# tc08ttl.net
KiCad netlist of a schematic drawn in EAGLE
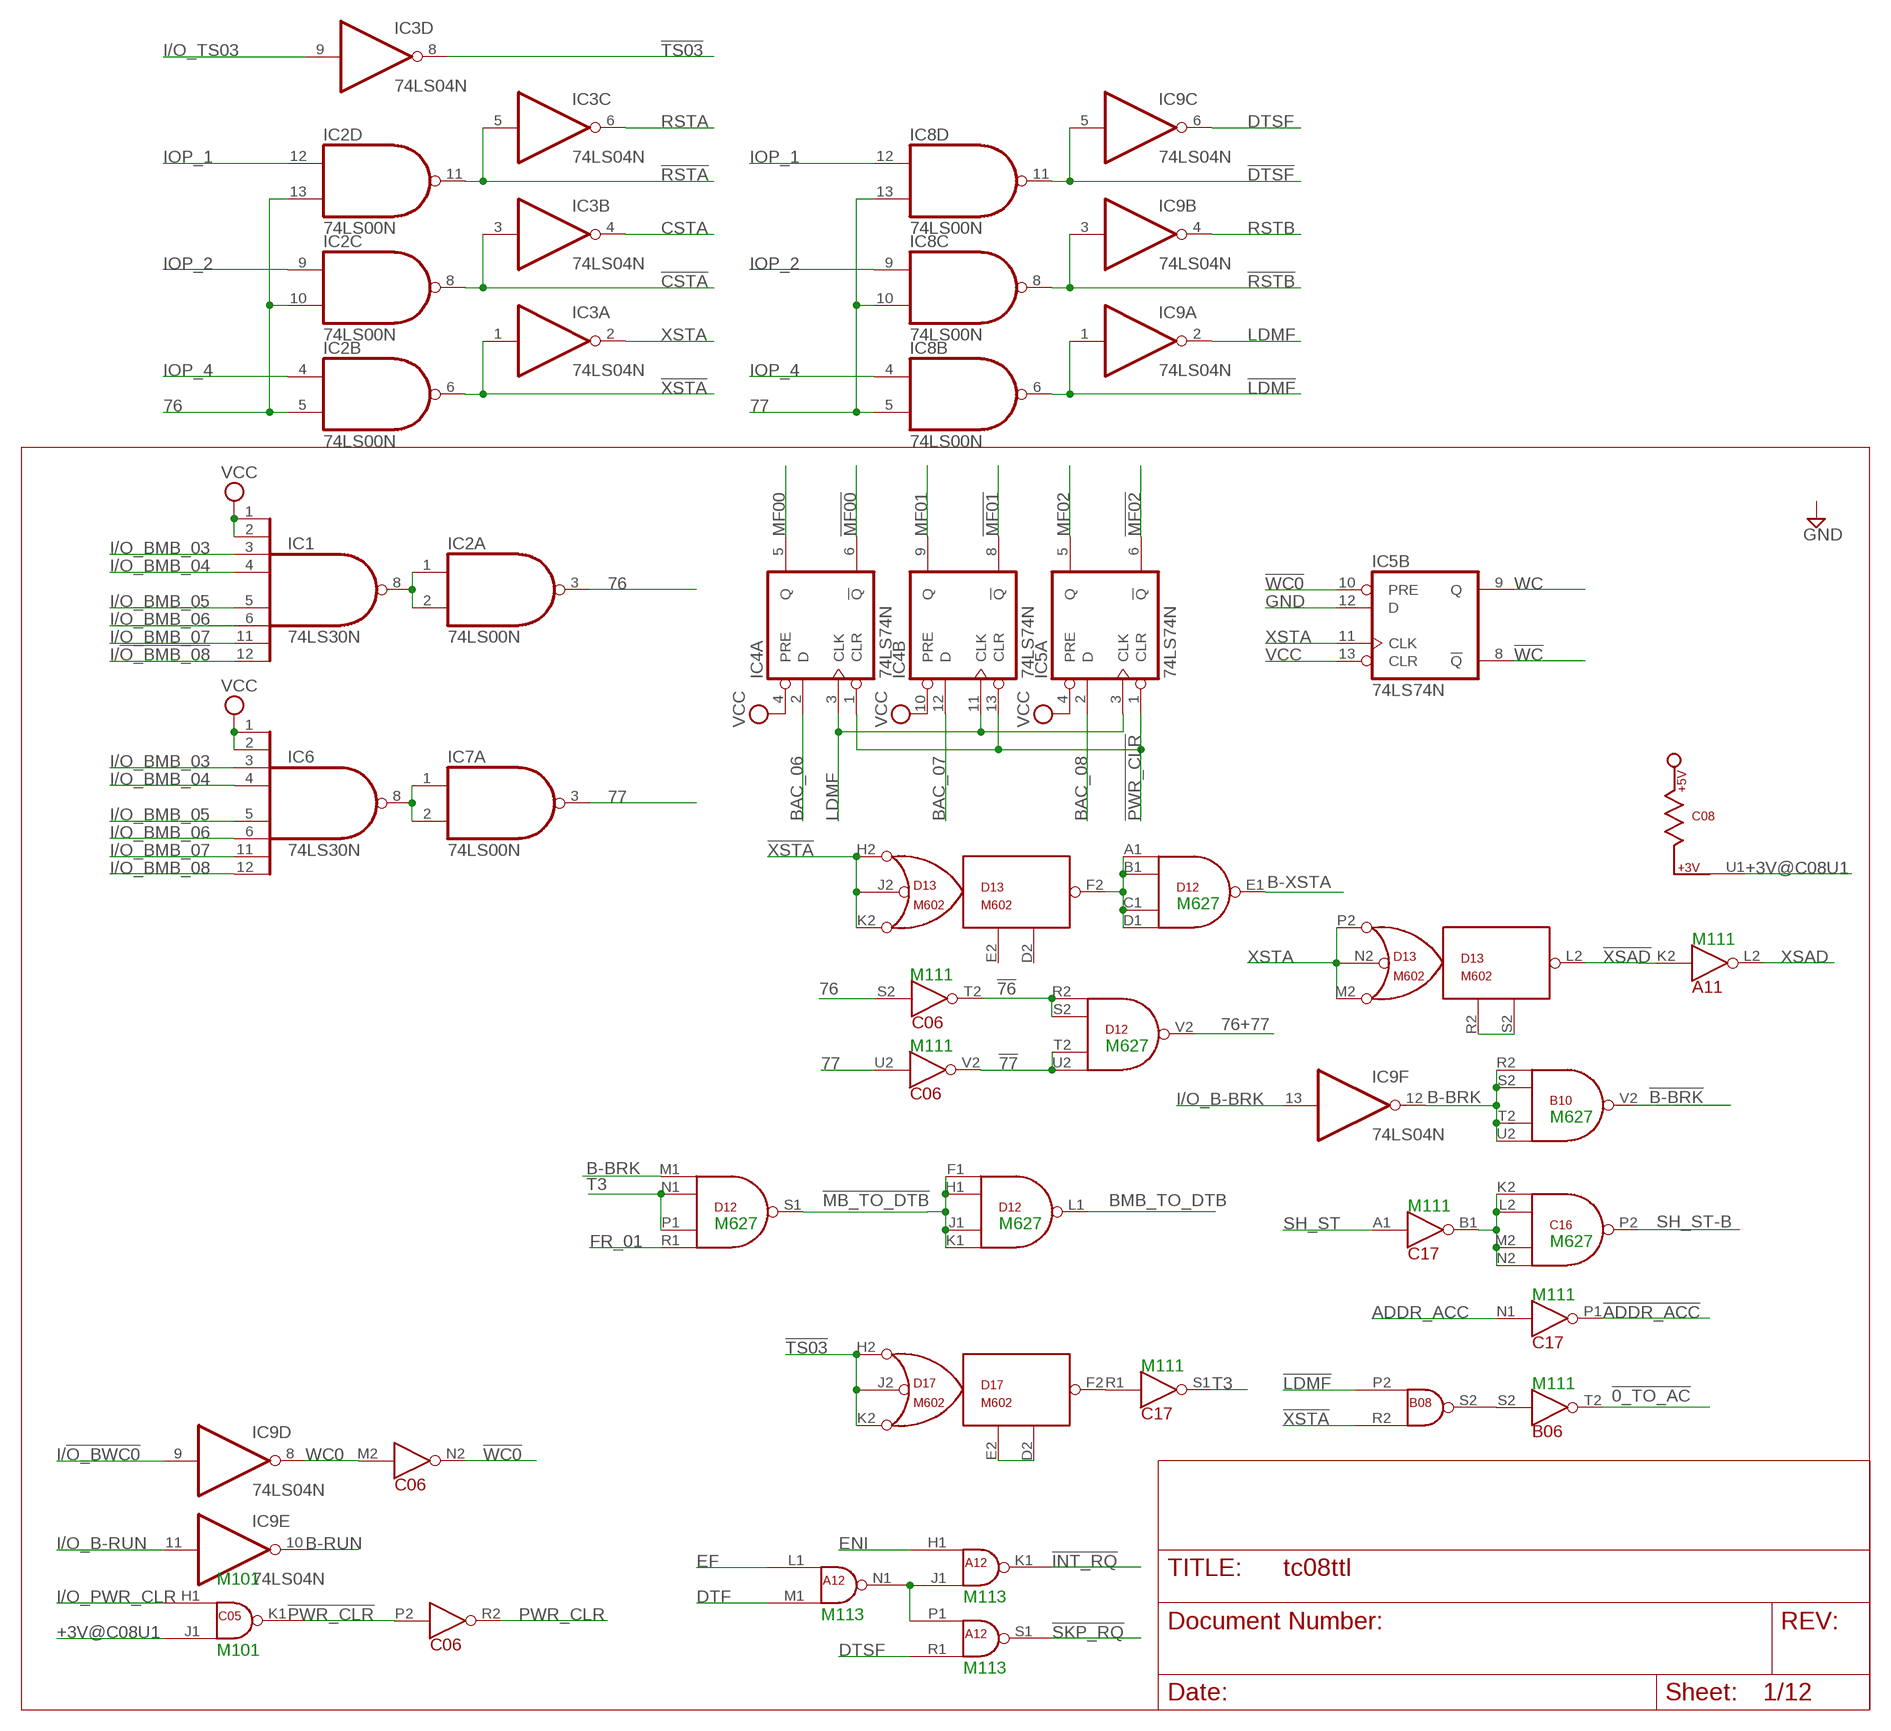
[diagram p0: schematic, sheet 1]
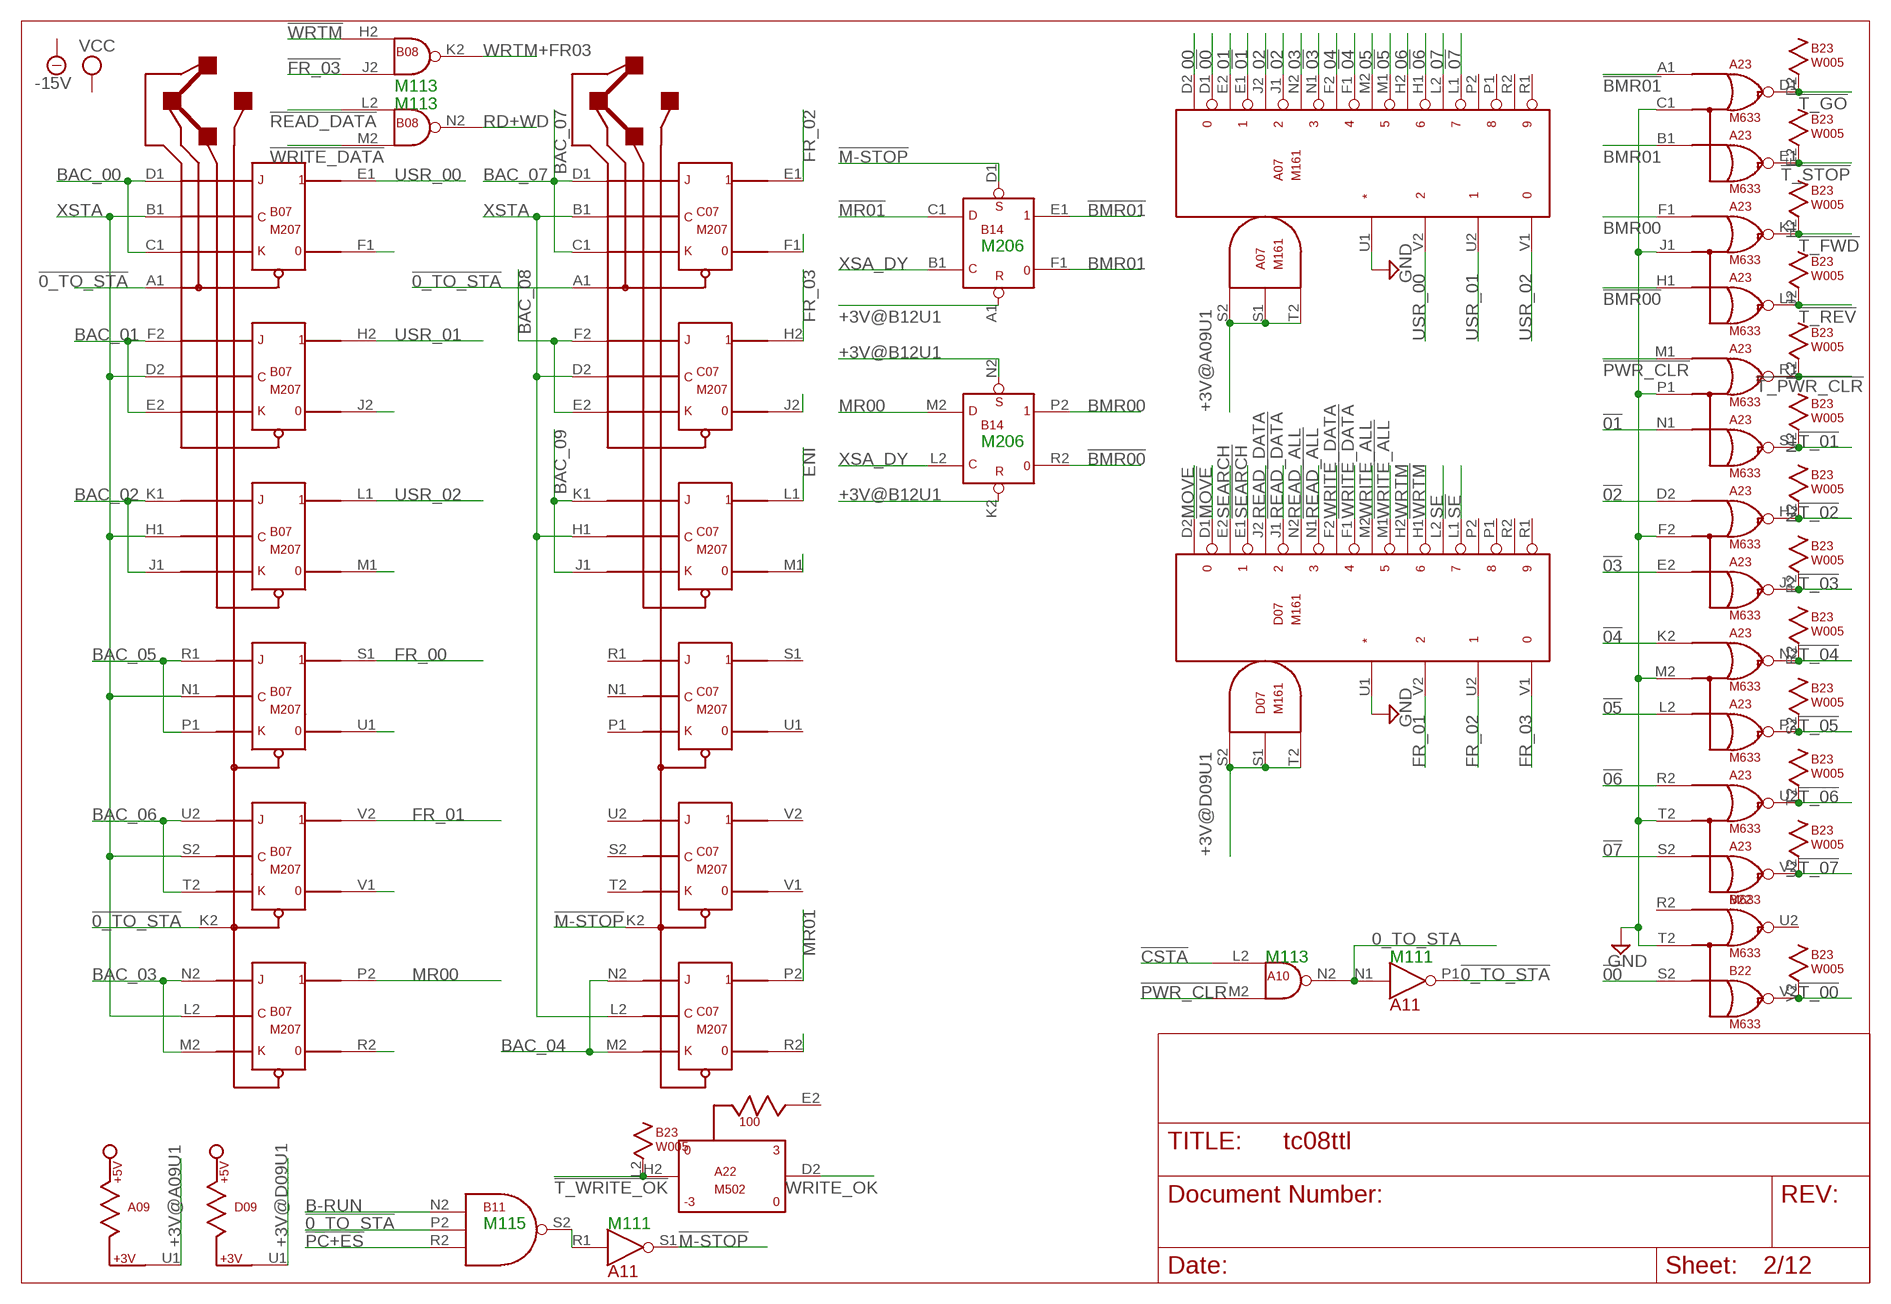
[diagram p1: schematic, sheet 2]
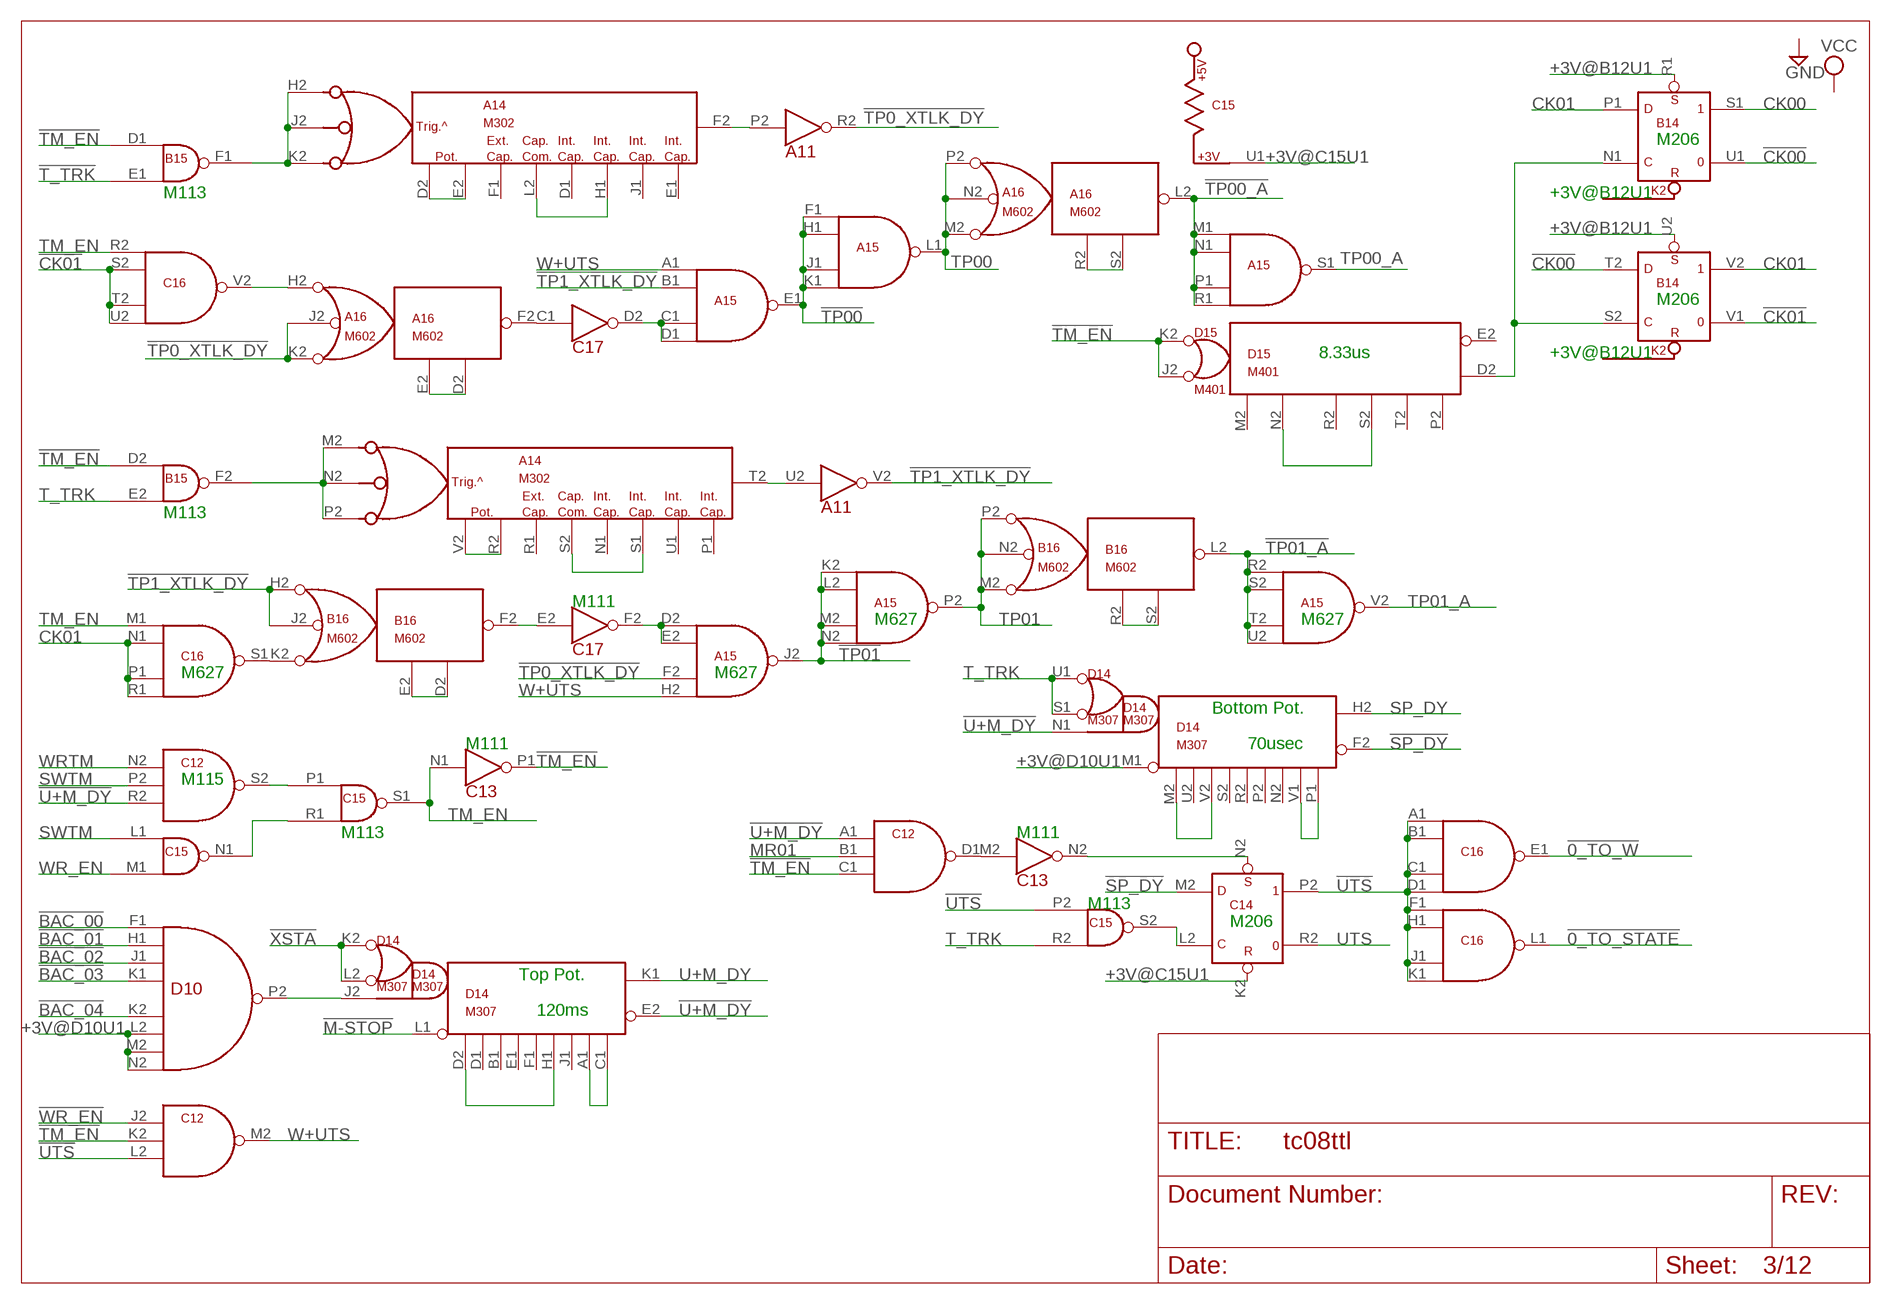
[diagram p2: schematic, sheet 3]
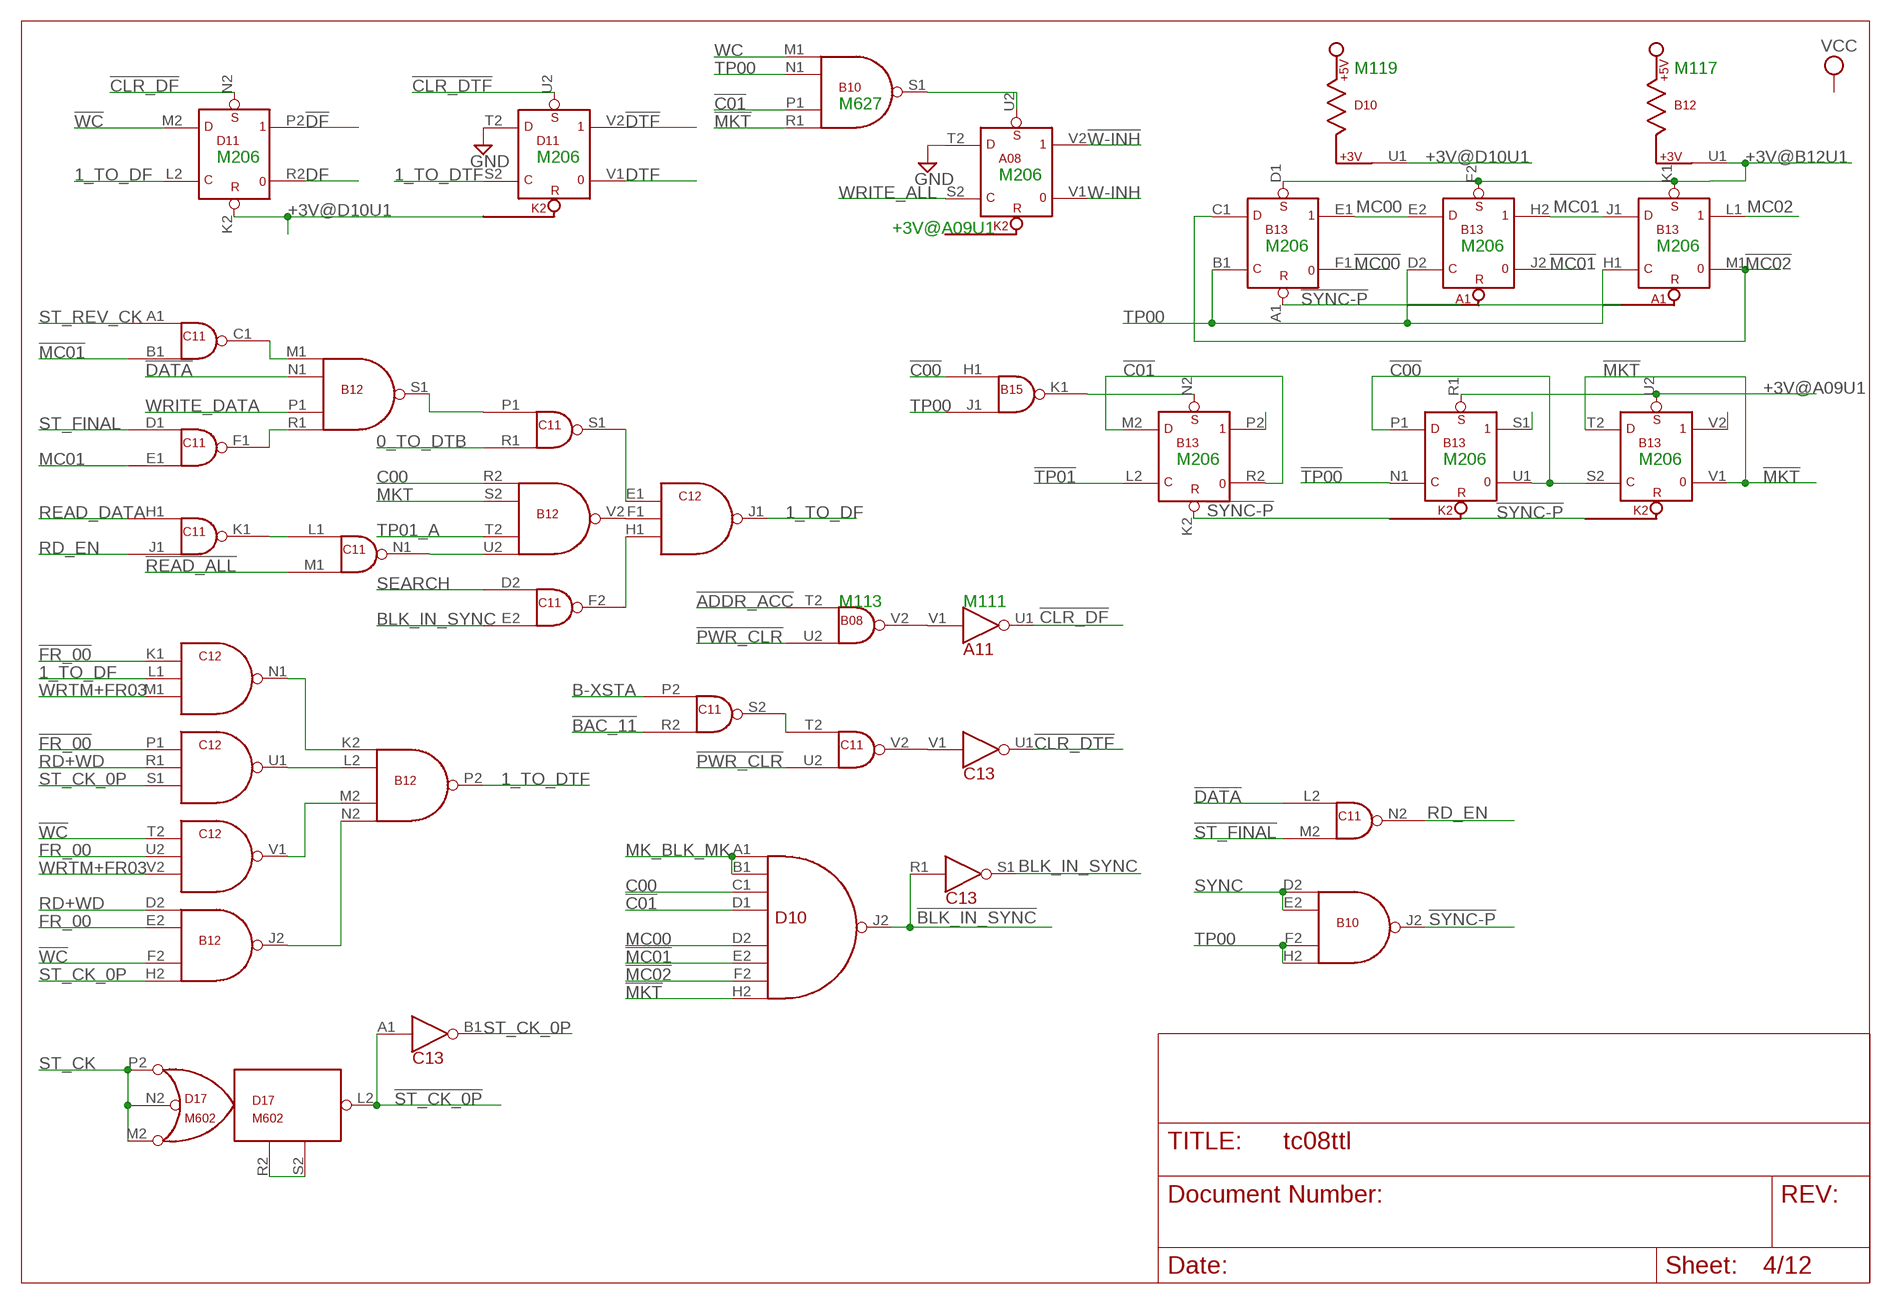
[diagram p3: schematic, sheet 4]
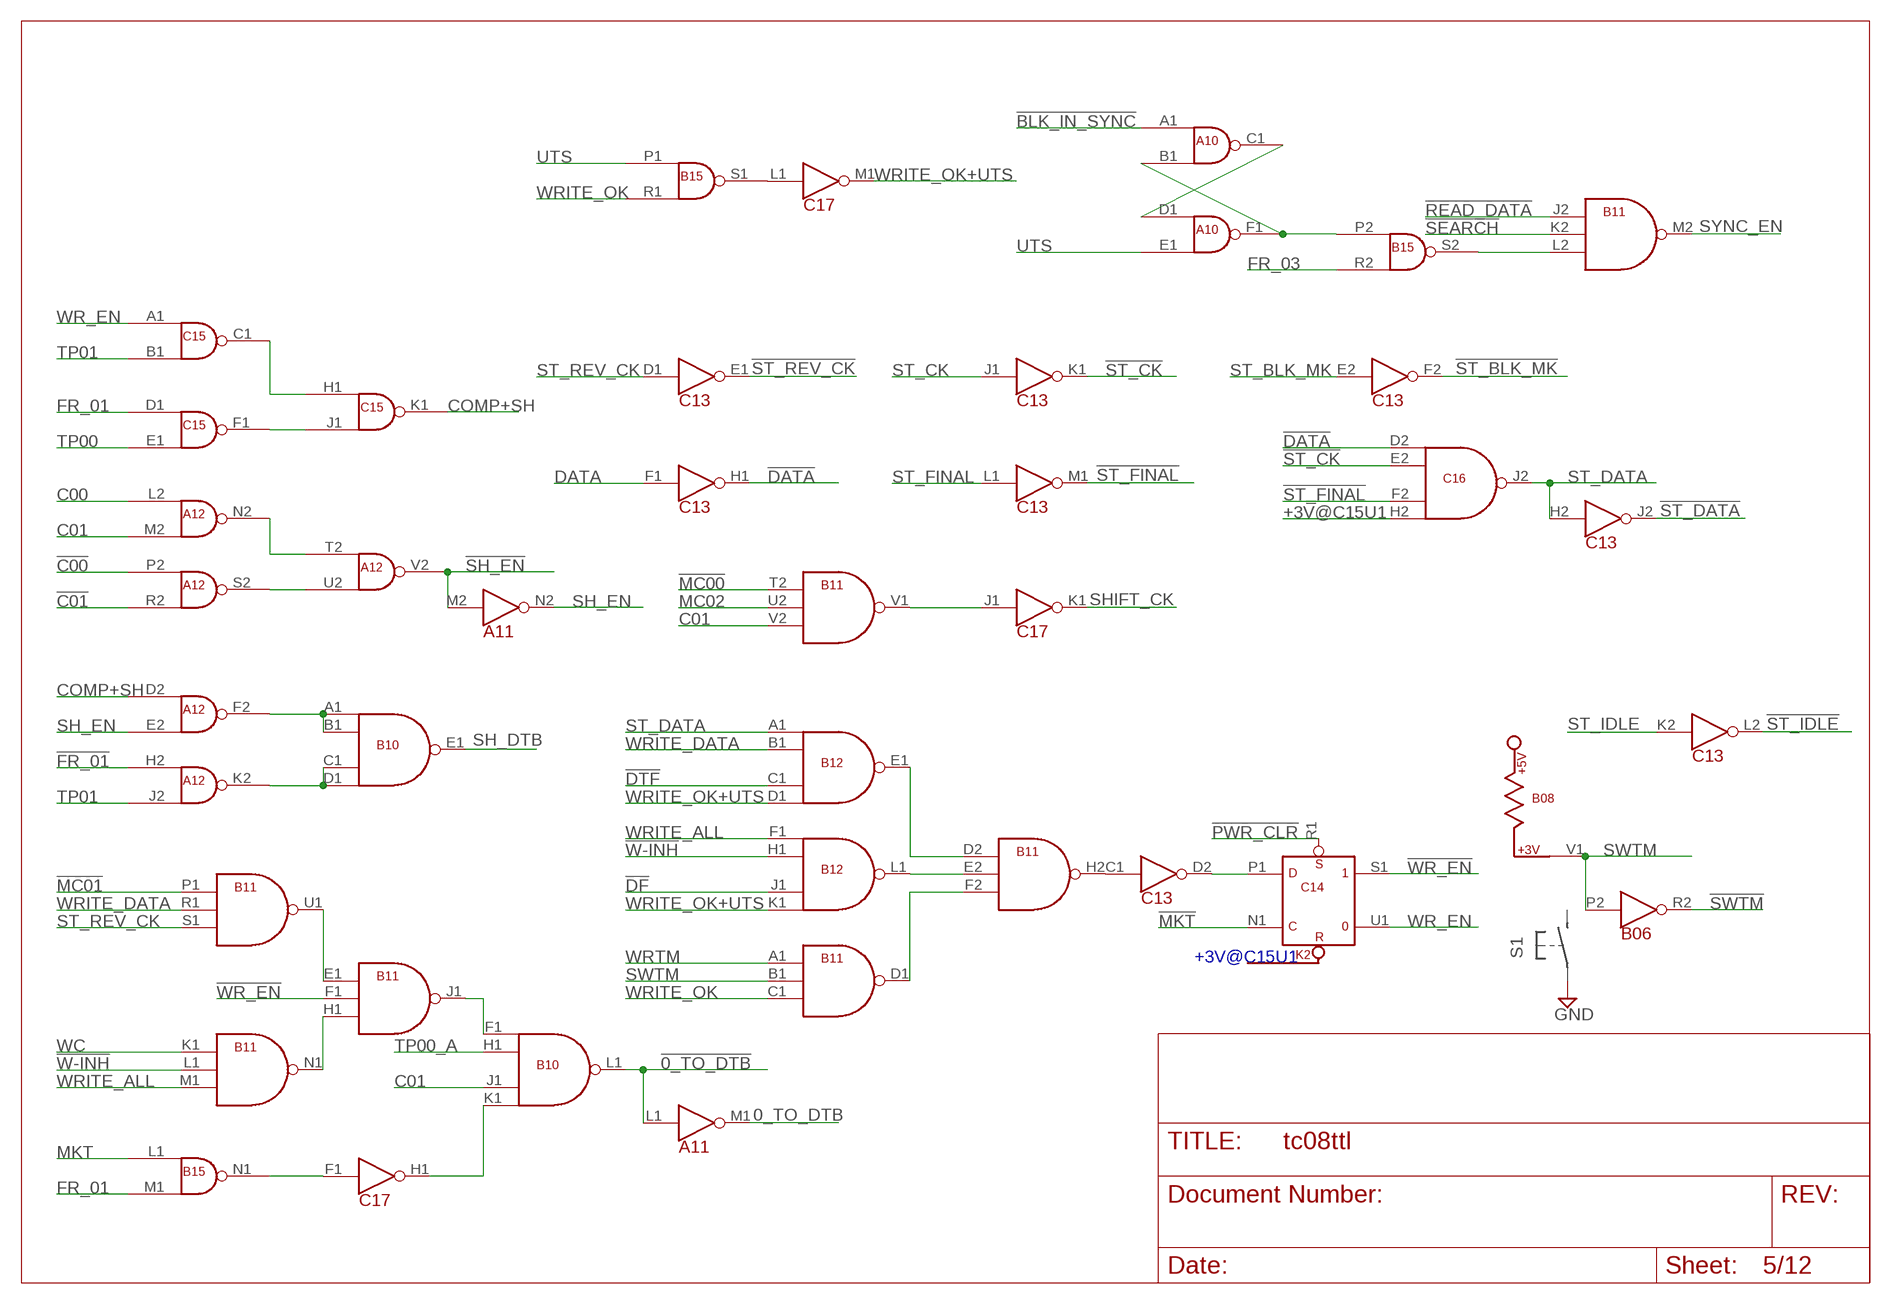
[diagram p4: schematic, sheet 5]
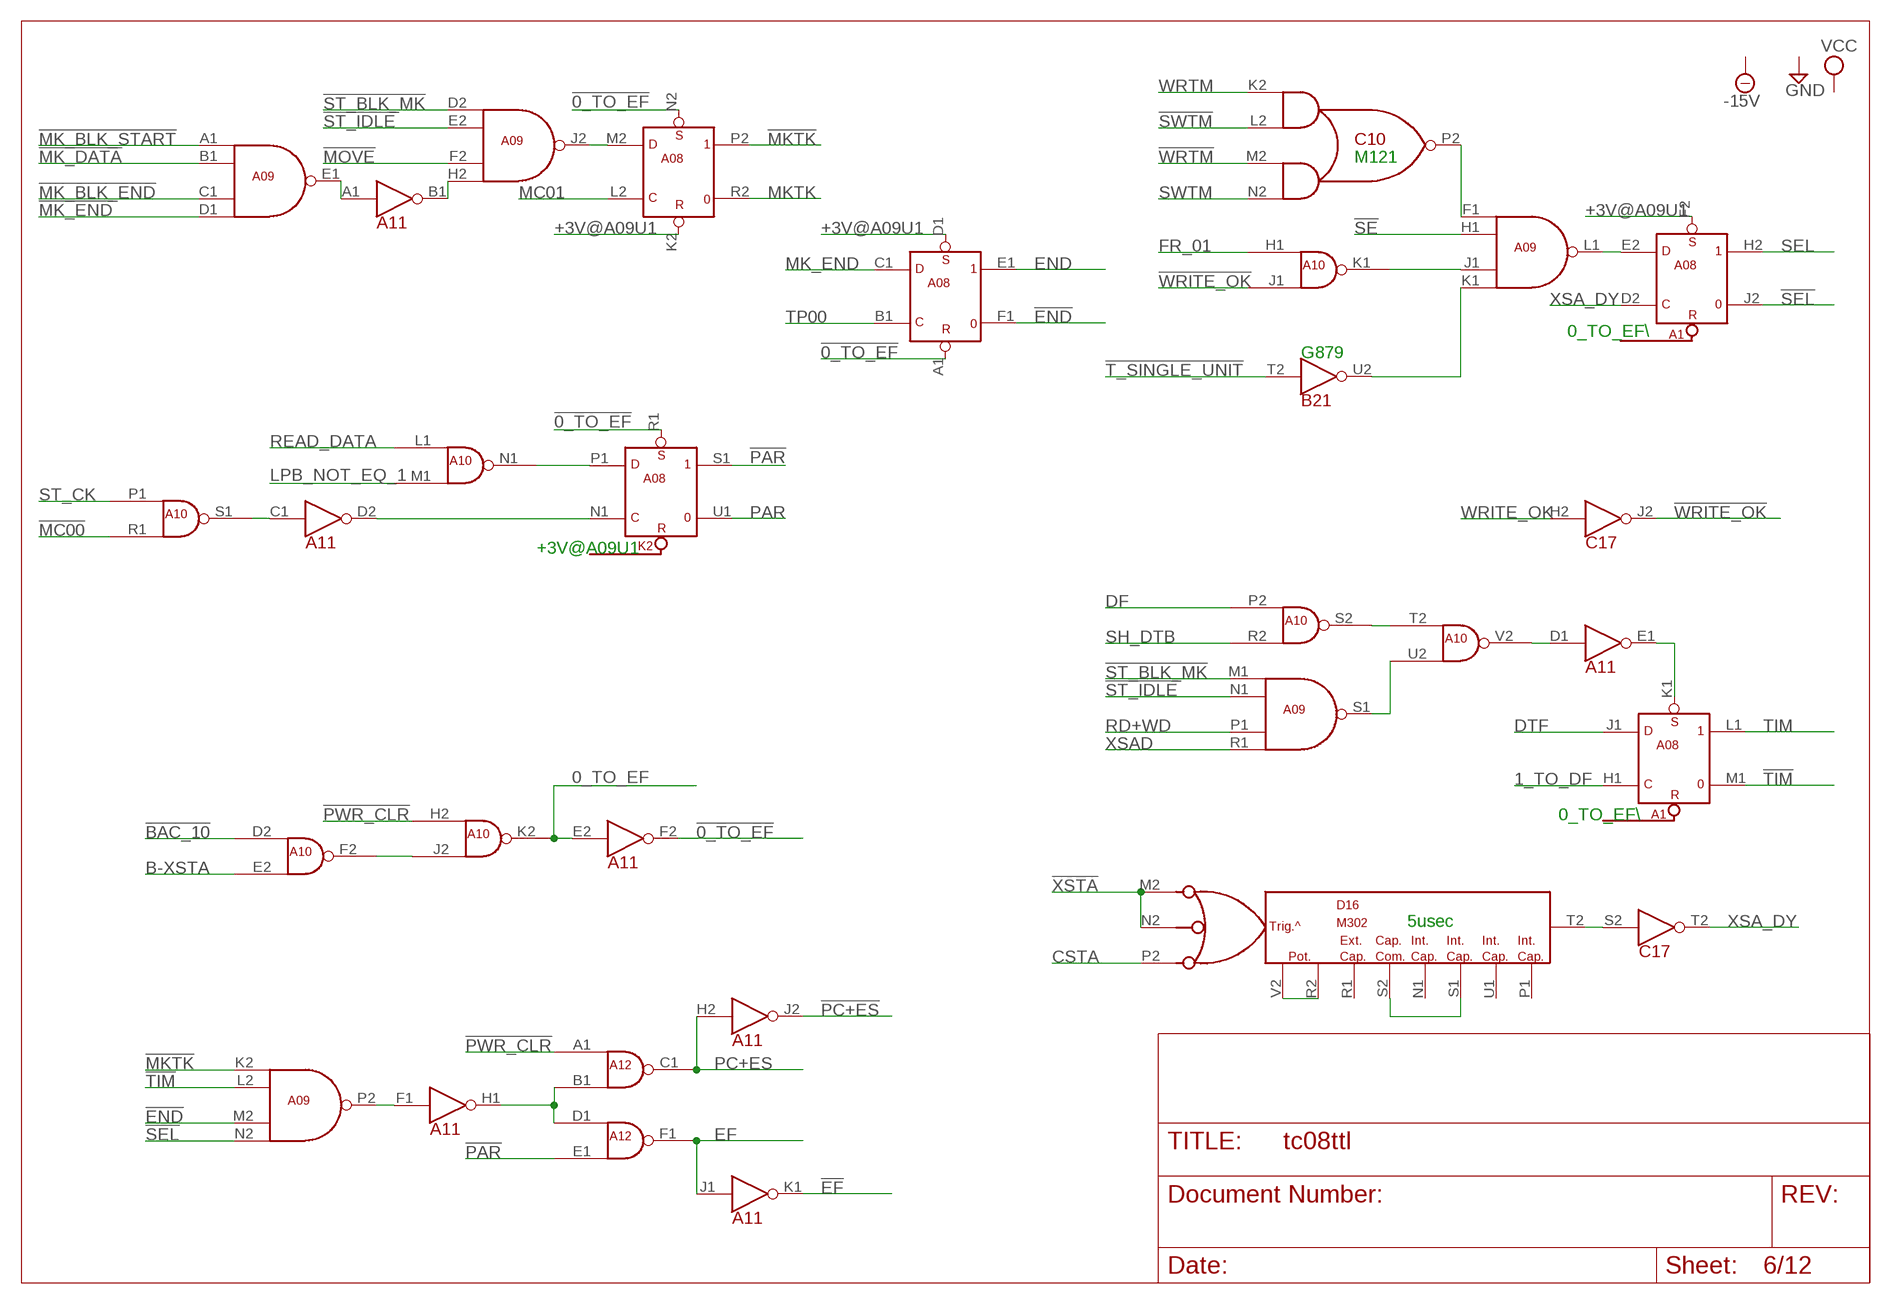
[diagram p5: schematic, sheet 6]
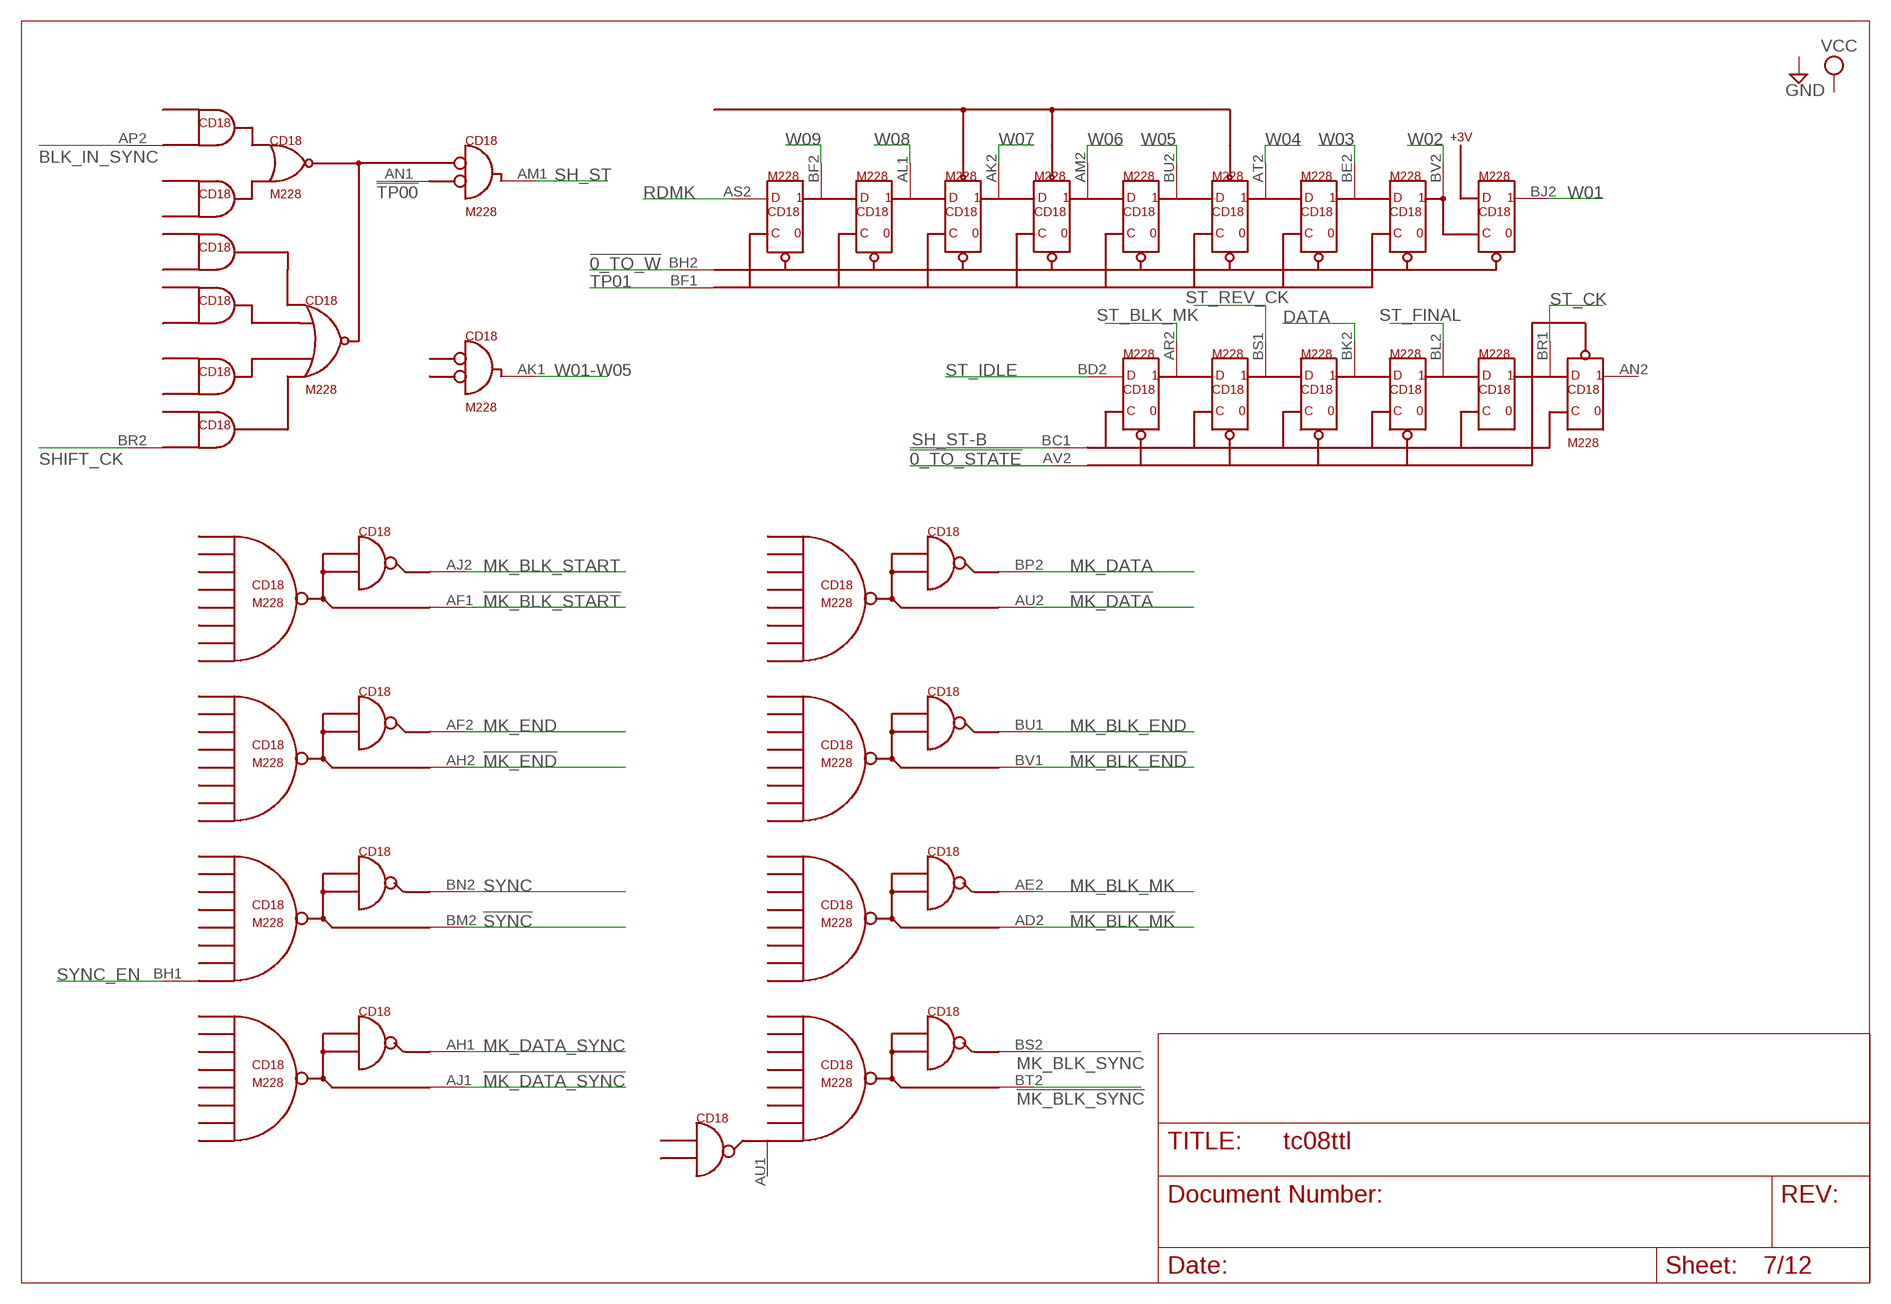
[diagram p6: schematic, sheet 7]
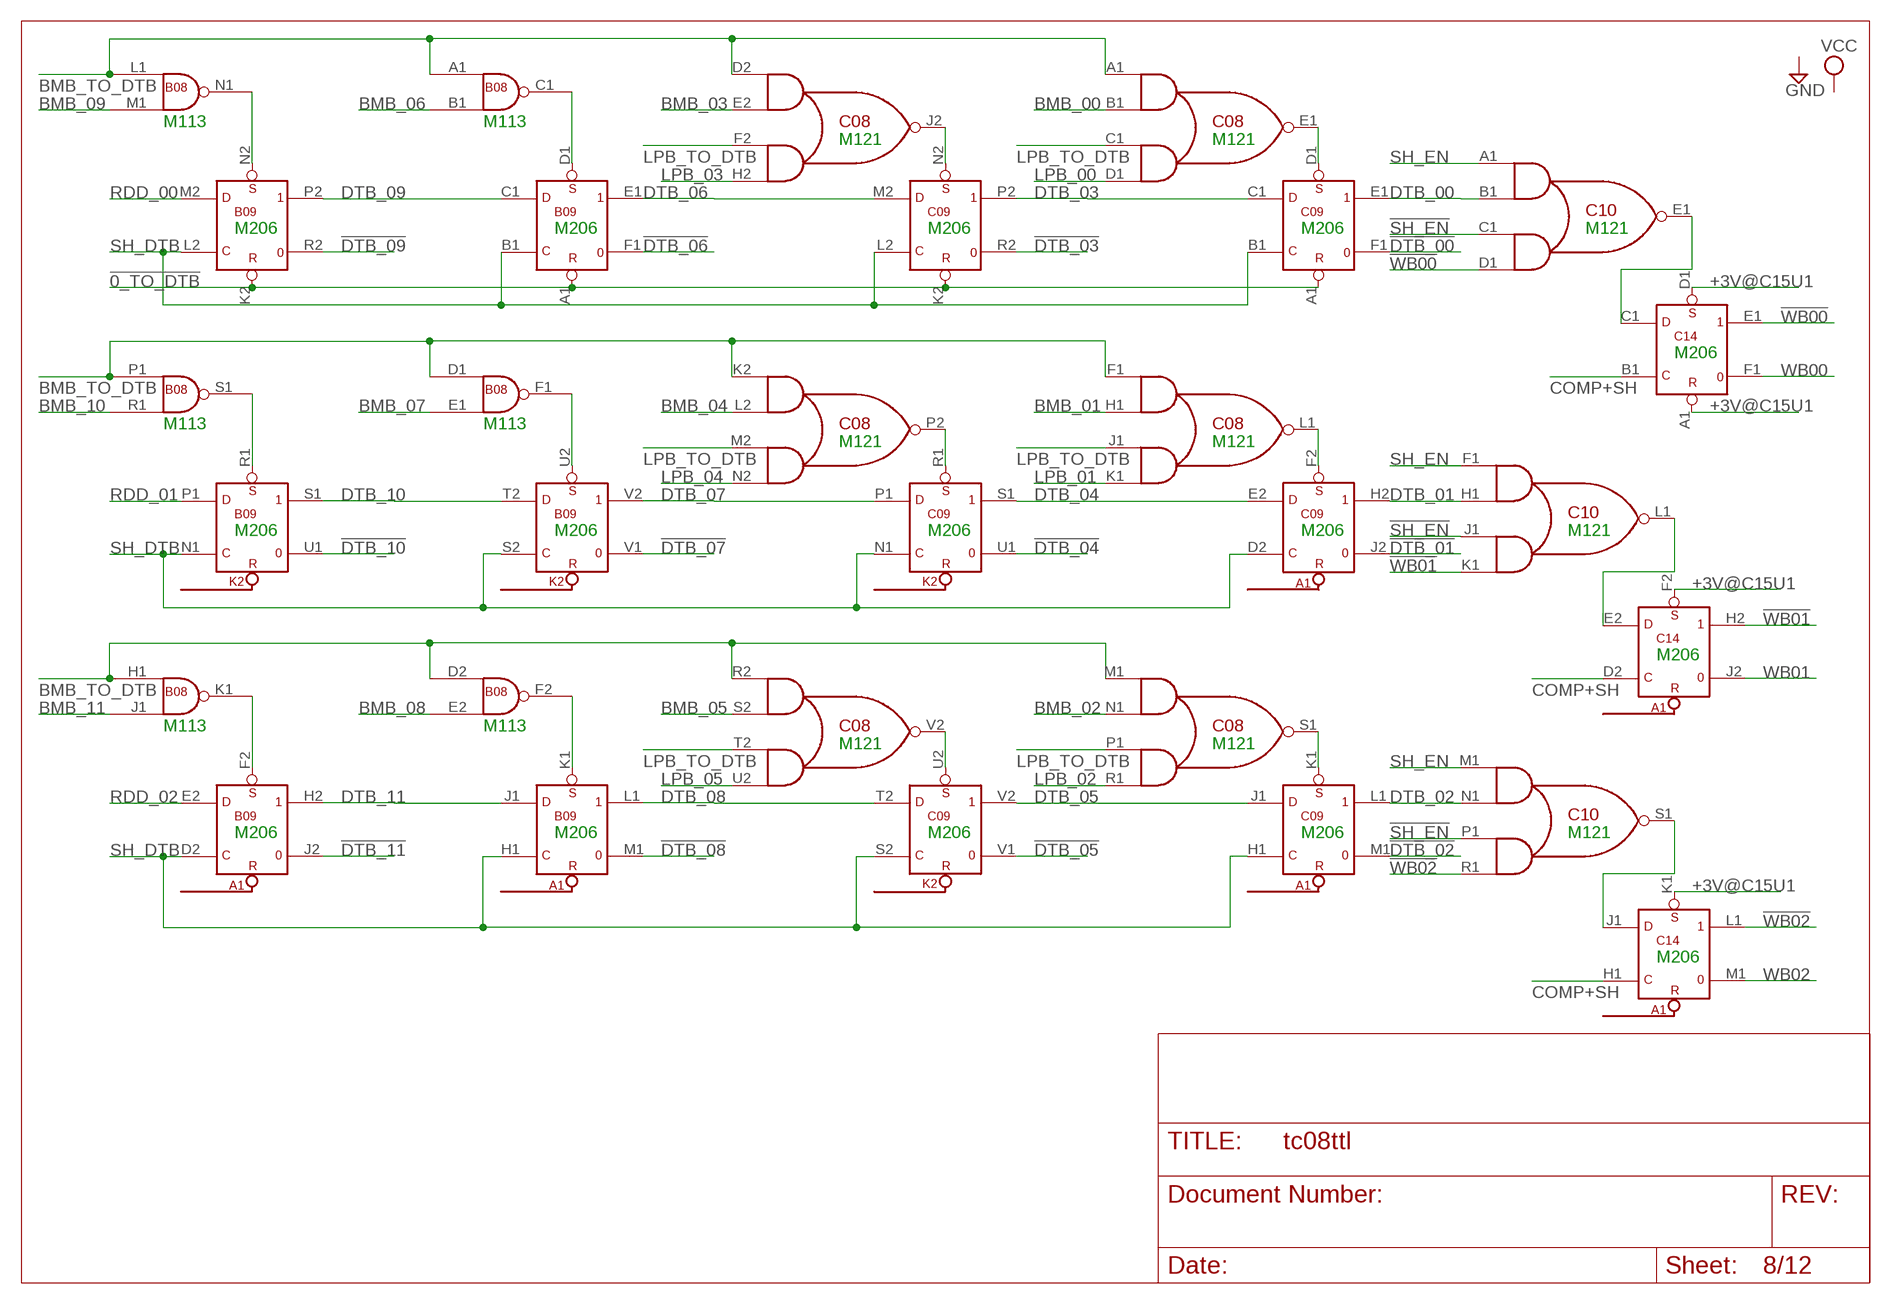
[diagram p7: schematic, sheet 8]
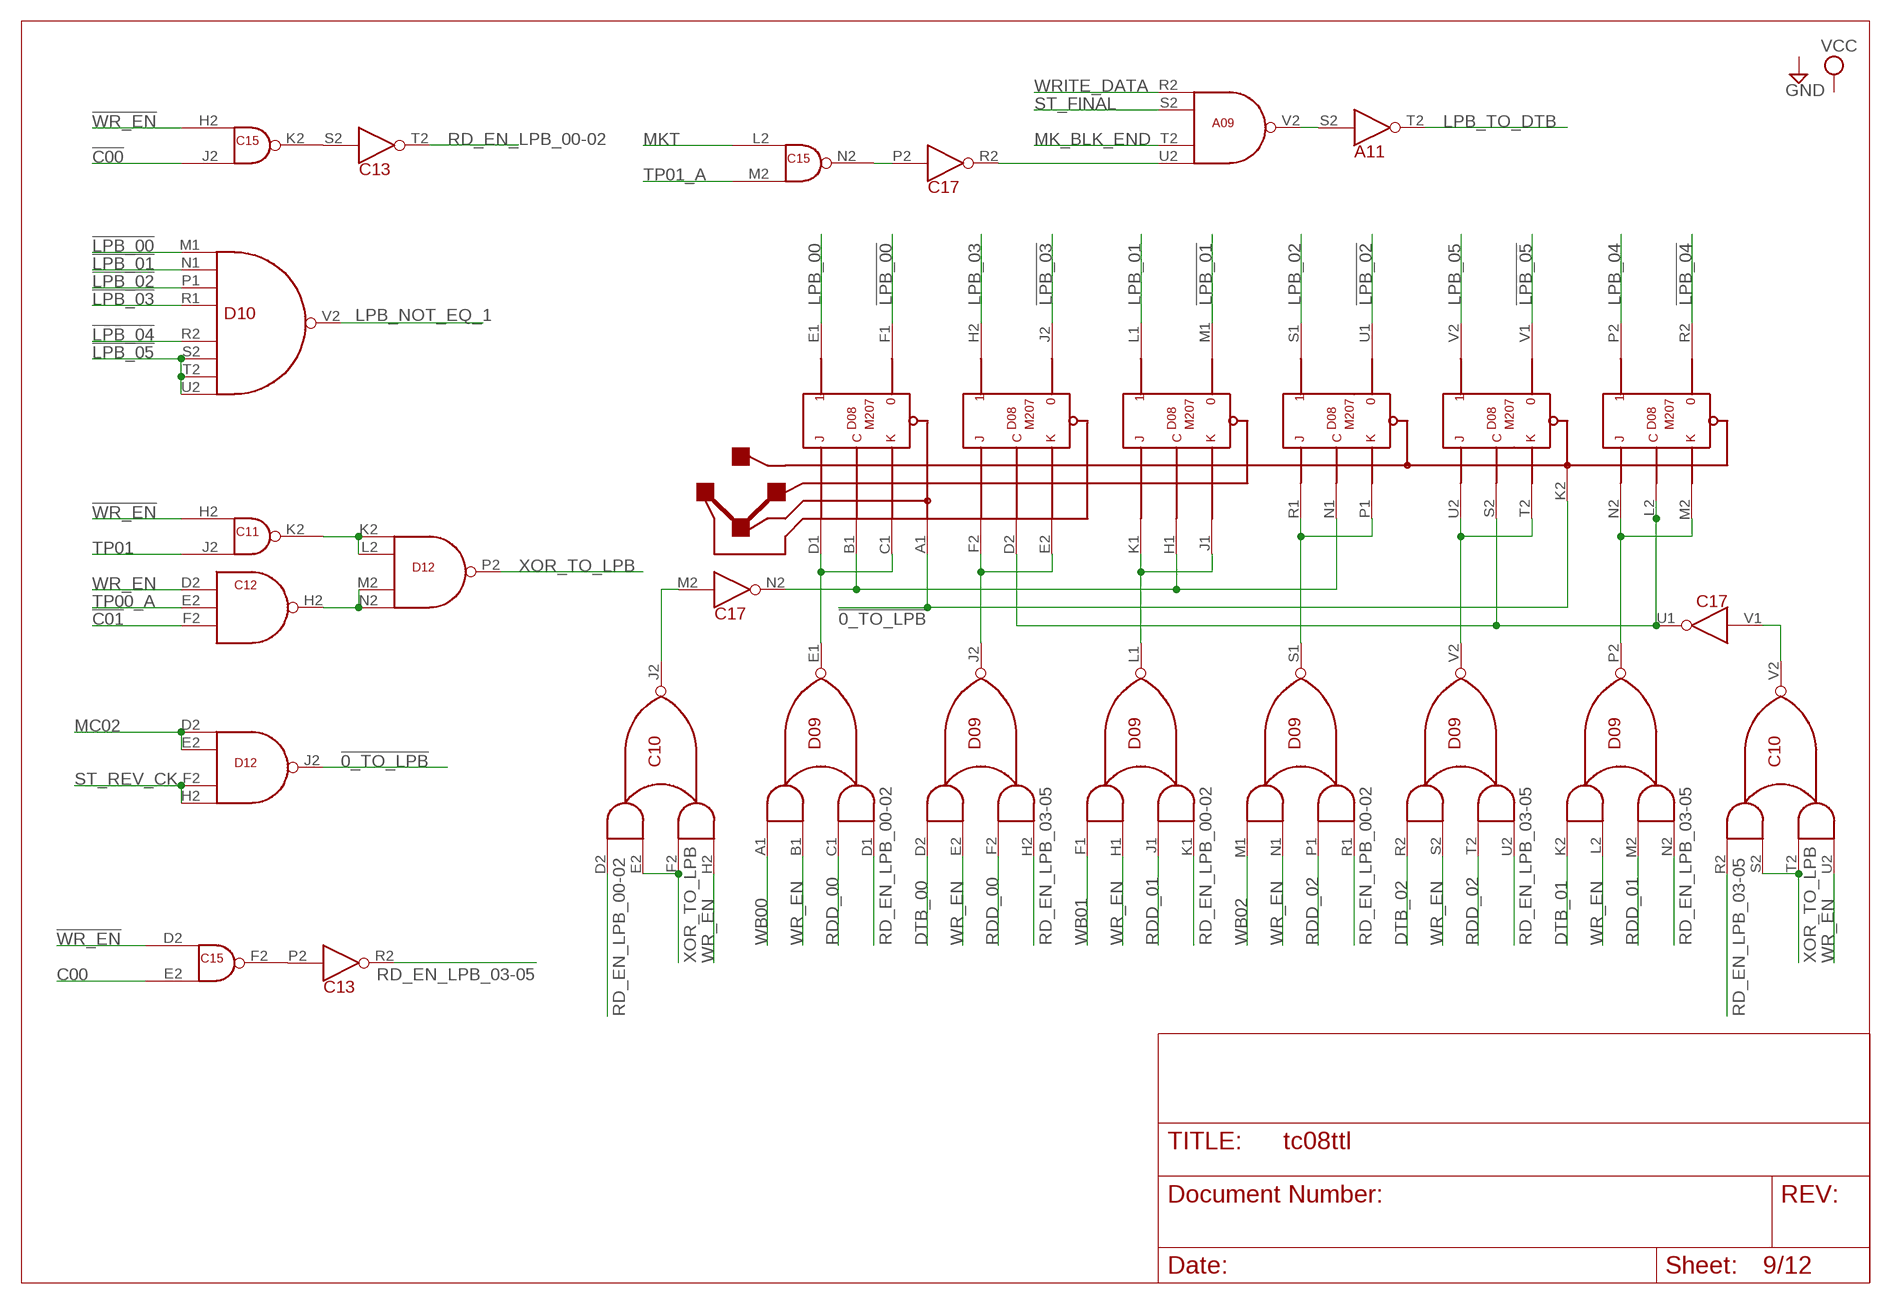
[diagram p8: schematic, sheet 9]
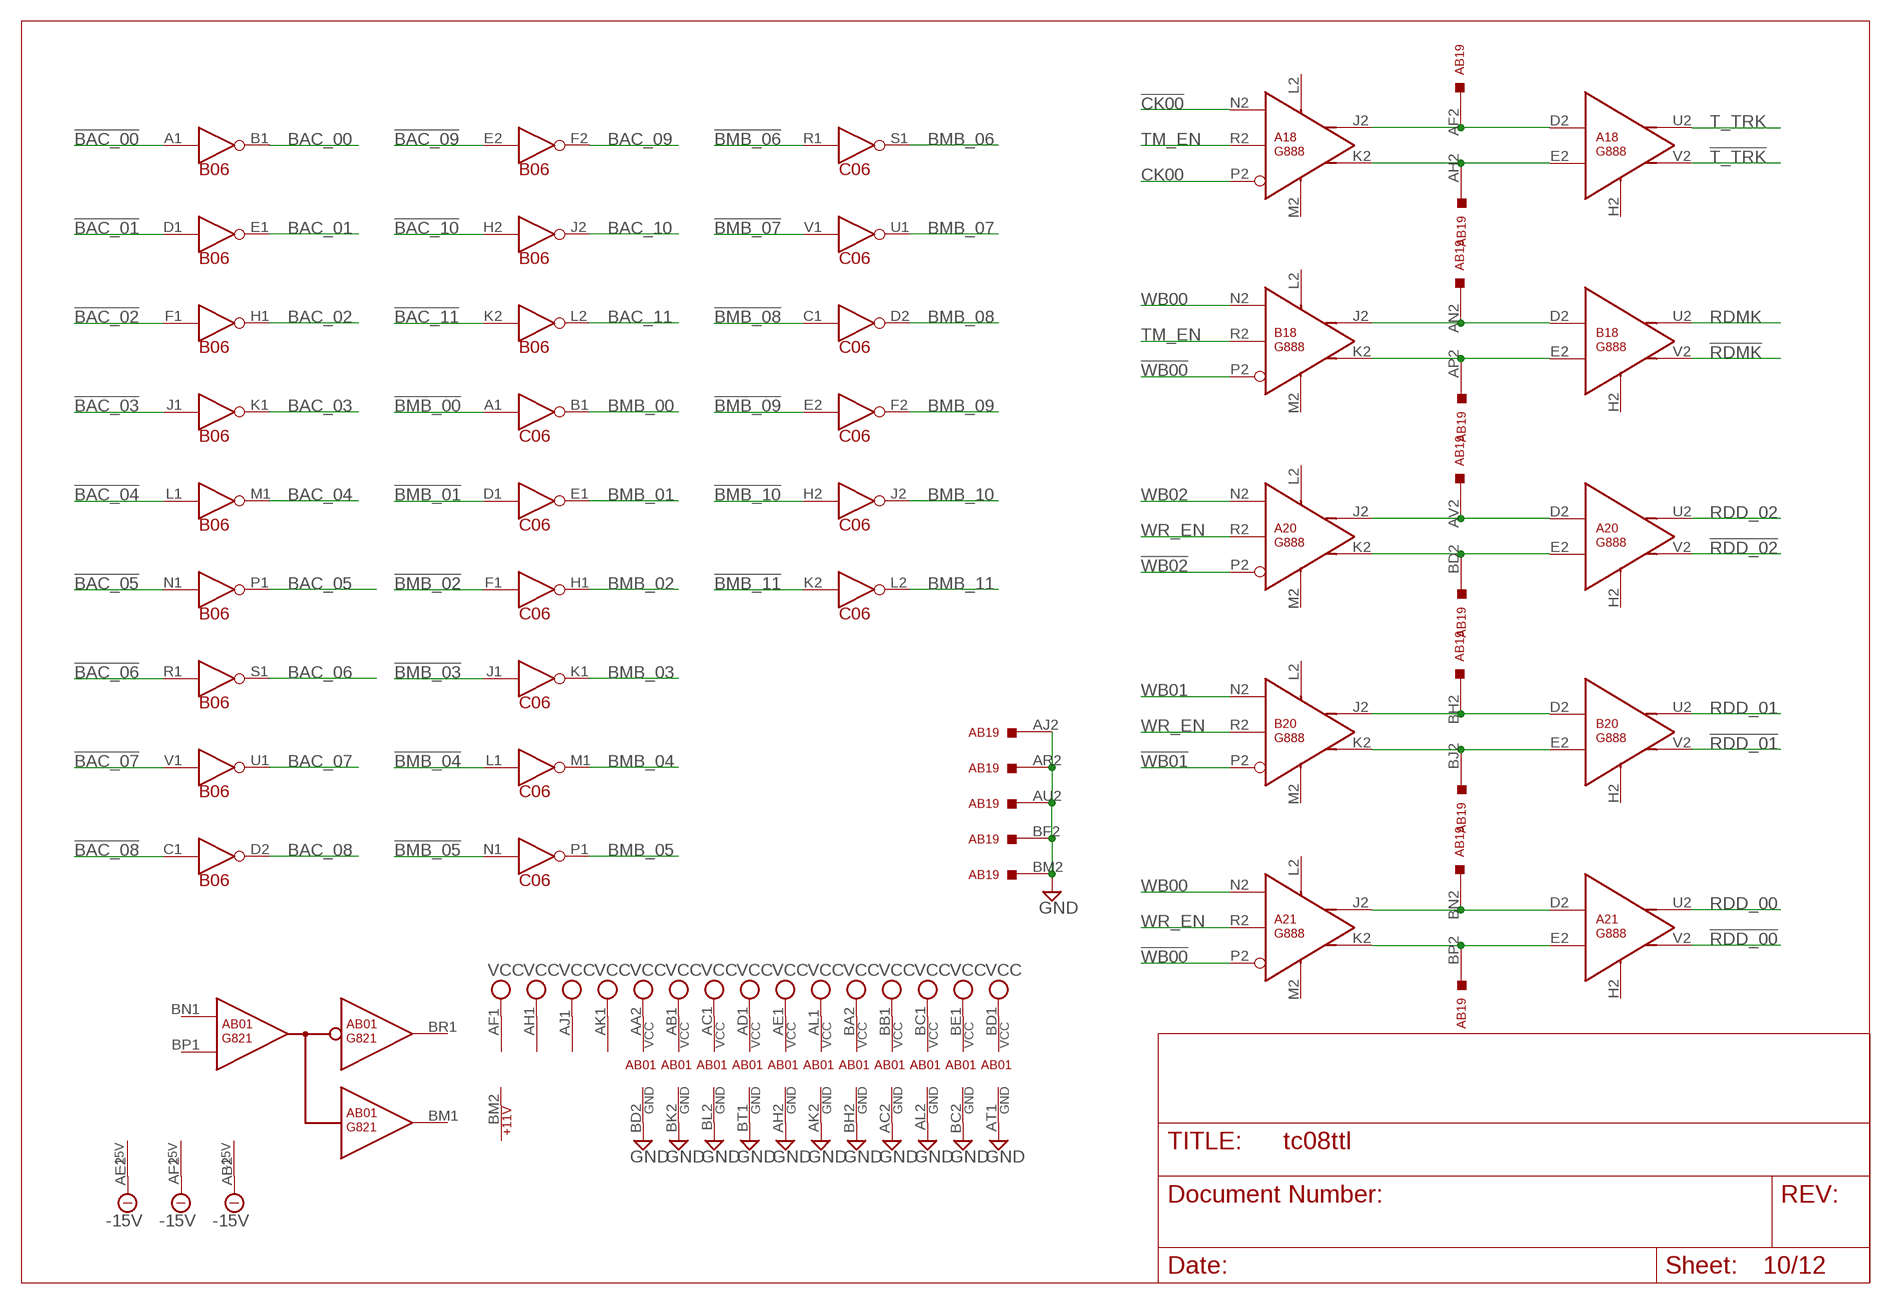
[diagram p9: schematic, sheet 10]
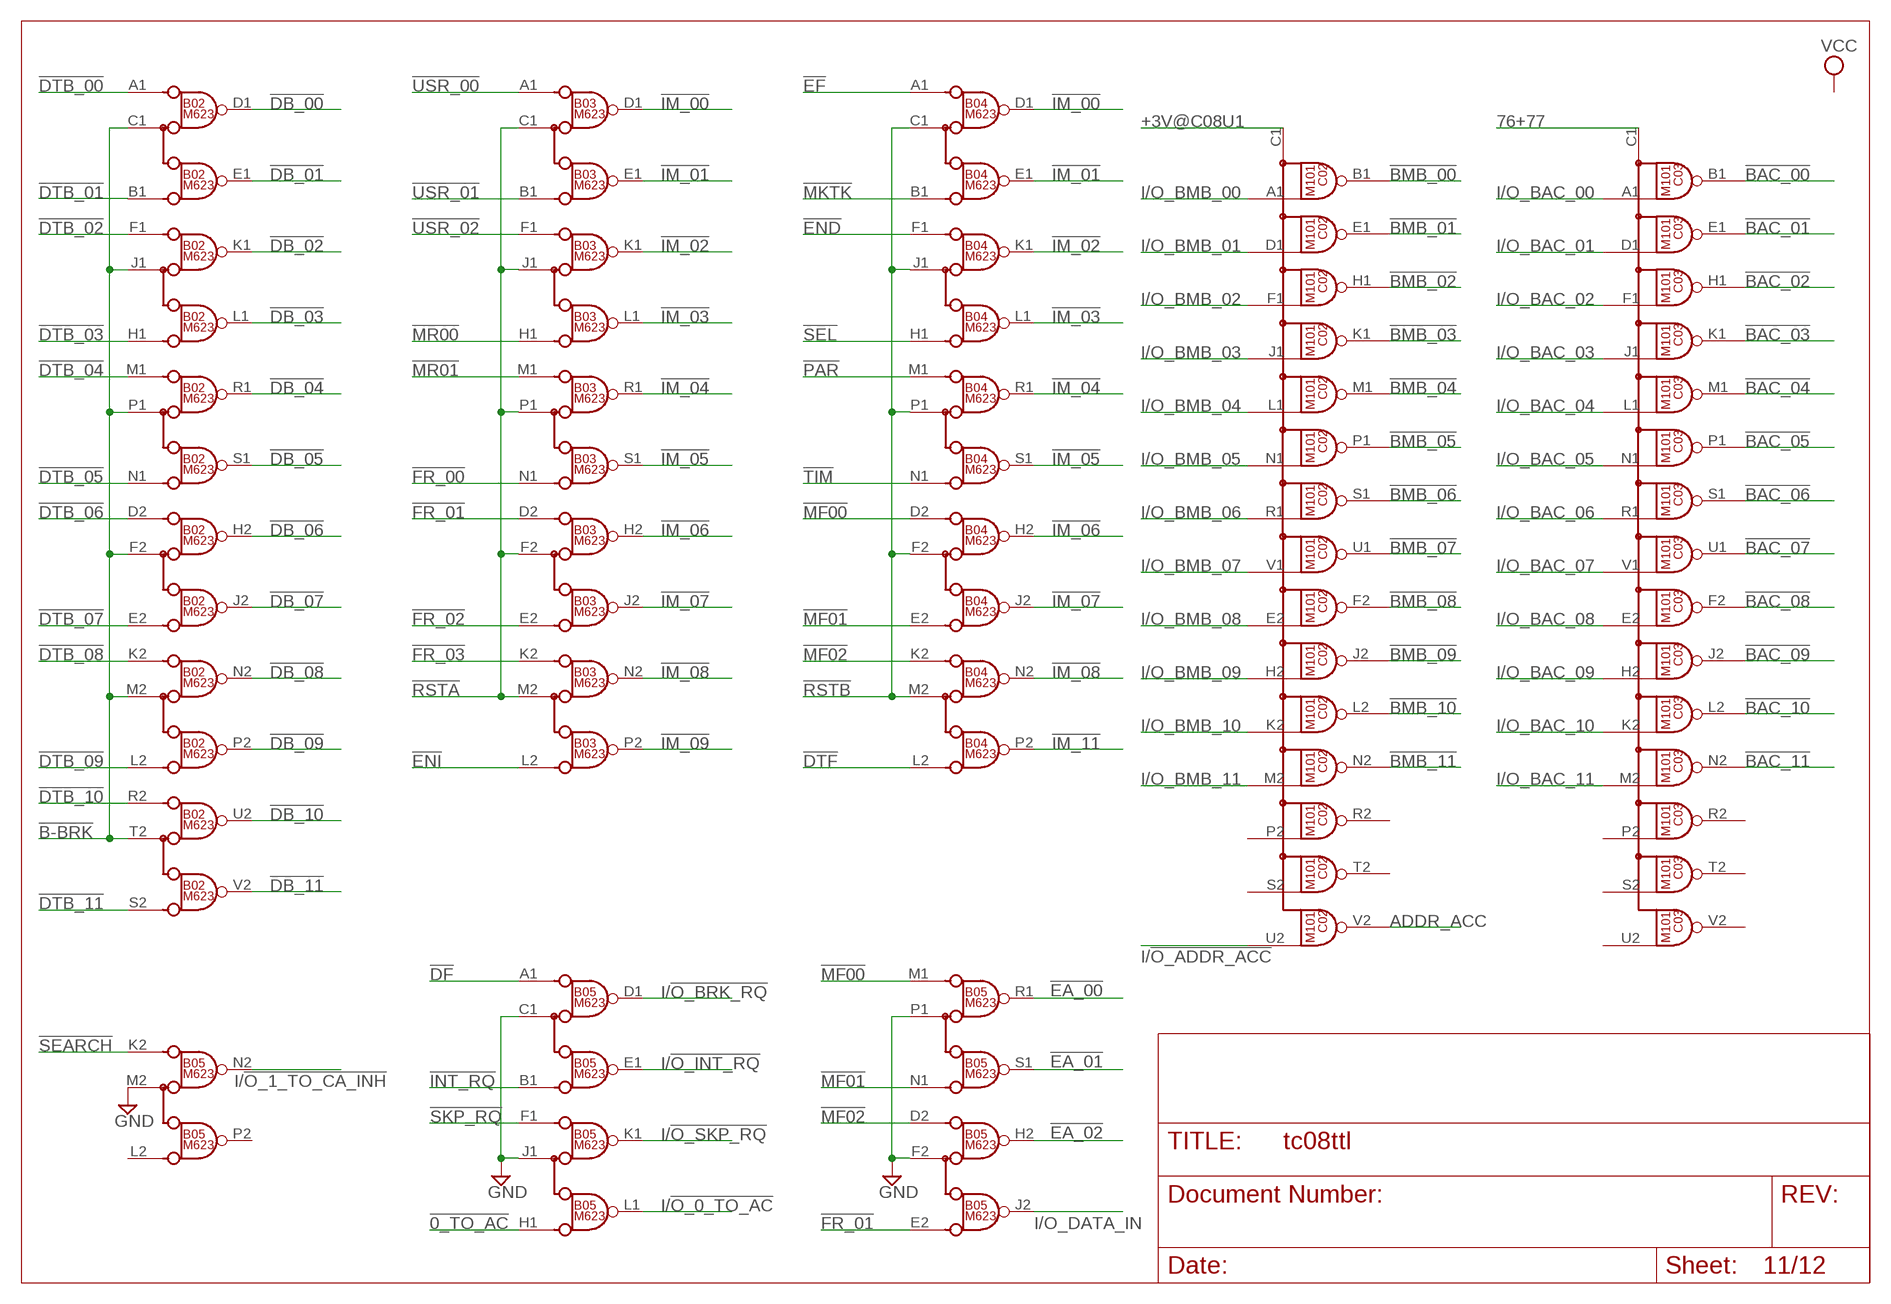
[diagram p10: schematic, sheet 11]
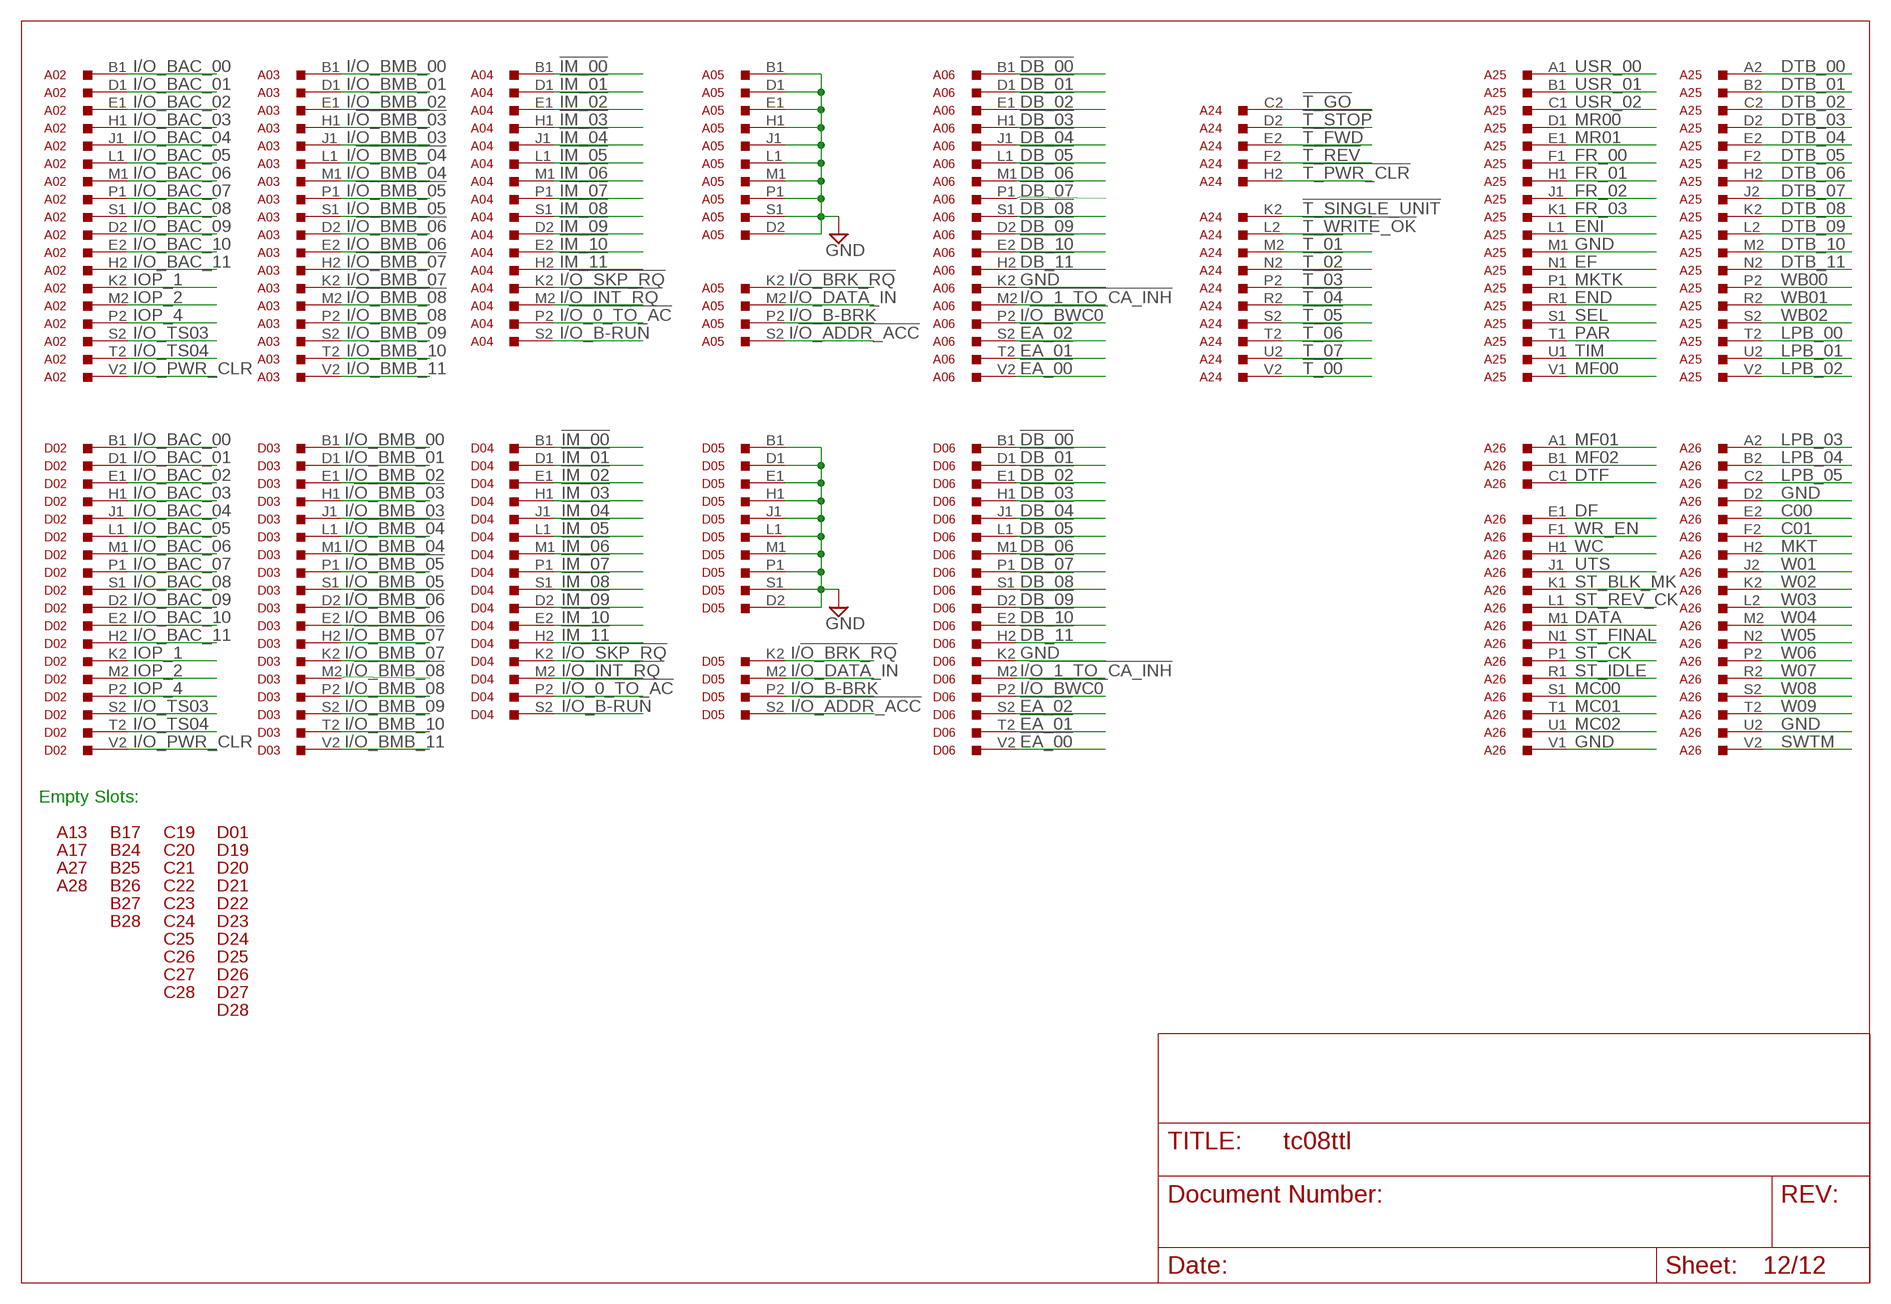
[diagram p11: schematic, sheet 12]

(export (version "E")
  (design (tool "Eeschema 10.0.6"))
  (components
    (comp (ref "A11")
      (value "A11")
      (footprint "eagle-import:H807")
      (libsource (lib "eagle-import") (part "M111"))
    )
    (comp (ref "A12")
      (value "A12")
      (footprint "eagle-import:H807")
      (libsource (lib "eagle-import") (part "M113"))
    )
    (comp (ref "B06")
      (value "B06")
      (footprint "eagle-import:H807")
      (libsource (lib "eagle-import") (part "M111"))
    )
    (comp (ref "B08")
      (value "B08")
      (footprint "eagle-import:H807")
      (libsource (lib "eagle-import") (part "M113"))
    )
    (comp (ref "B10")
      (value "B10")
      (footprint "eagle-import:H807")
      (libsource (lib "eagle-import") (part "M627"))
    )
    (comp (ref "C05")
      (value "C05")
      (footprint "eagle-import:H807")
      (libsource (lib "eagle-import") (part "M103"))
    )
    (comp (ref "C06")
      (value "C06")
      (footprint "eagle-import:H807")
      (libsource (lib "eagle-import") (part "M111"))
    )
    (comp (ref "C08")
      (value "C08")
      (footprint "eagle-import:H807")
      (libsource (lib "eagle-import") (part "M121"))
    )
    (comp (ref "C16")
      (value "C16")
      (footprint "eagle-import:H807")
      (libsource (lib "eagle-import") (part "M627"))
    )
    (comp (ref "C17")
      (value "C17")
      (footprint "eagle-import:H807")
      (libsource (lib "eagle-import") (part "M111"))
    )
    (comp (ref "D12")
      (value "D12")
      (footprint "eagle-import:H807")
      (libsource (lib "eagle-import") (part "M627"))
    )
    (comp (ref "D13")
      (value "D13")
      (footprint "eagle-import:H807")
      (libsource (lib "eagle-import") (part "M602"))
    )
    (comp (ref "D17")
      (value "D17")
      (footprint "eagle-import:H807")
      (libsource (lib "eagle-import") (part "M602"))
    )
    (comp (ref "IC1")
      (value "74LS30N")
      (footprint "eagle-import:DIL14")
      (libsource (lib "eagle-import") (part "7430NLS"))
    )
    (comp (ref "IC2")
      (value "74LS00N")
      (footprint "eagle-import:DIL14")
      (libsource (lib "eagle-import") (part "7400NLS"))
    )
    (comp (ref "IC3")
      (value "74LS04N")
      (footprint "eagle-import:DIL14")
      (libsource (lib "eagle-import") (part "7404NLS"))
    )
    (comp (ref "IC4")
      (value "74LS74N")
      (footprint "eagle-import:DIL14")
      (libsource (lib "eagle-import") (part "7474NLS"))
    )
    (comp (ref "IC5")
      (value "74LS74N")
      (footprint "eagle-import:DIL14")
      (libsource (lib "eagle-import") (part "7474NLS"))
    )
    (comp (ref "IC6")
      (value "74LS30N")
      (footprint "eagle-import:DIL14")
      (libsource (lib "eagle-import") (part "7430NLS"))
    )
    (comp (ref "IC7")
      (value "74LS00N")
      (footprint "eagle-import:DIL14")
      (libsource (lib "eagle-import") (part "7400NLS"))
    )
    (comp (ref "IC8")
      (value "74LS00N")
      (footprint "eagle-import:DIL14")
      (libsource (lib "eagle-import") (part "7400NLS"))
    )
    (comp (ref "IC9")
      (value "74LS04N")
      (footprint "eagle-import:DIL14")
      (libsource (lib "eagle-import") (part "7404NLS"))
    )
    (comp (ref "A08")
      (value "M206X")
      (footprint "eagle-import:H807")
      (libsource (lib "eagle-import") (part "M206X"))
    )
    (comp (ref "B12")
      (value "M117")
      (footprint "eagle-import:H807")
      (libsource (lib "eagle-import") (part "M117"))
    )
    (comp (ref "B13")
      (value "M206X")
      (footprint "eagle-import:H807")
      (libsource (lib "eagle-import") (part "M206X"))
    )
    (comp (ref "B15")
      (value "M113")
      (footprint "eagle-import:H807")
      (libsource (lib "eagle-import") (part "M113"))
    )
    (comp (ref "C11")
      (value "M113")
      (footprint "eagle-import:H807")
      (libsource (lib "eagle-import") (part "M113"))
    )
    (comp (ref "C12")
      (value "M115")
      (footprint "eagle-import:H807")
      (libsource (lib "eagle-import") (part "M115"))
    )
    (comp (ref "C13")
      (value "M111")
      (footprint "eagle-import:H807")
      (libsource (lib "eagle-import") (part "M111"))
    )
    (comp (ref "D10")
      (value "M119")
      (footprint "eagle-import:H807")
      (libsource (lib "eagle-import") (part "M119"))
    )
    (comp (ref "D11")
      (value "M206X")
      (footprint "eagle-import:H807")
      (libsource (lib "eagle-import") (part "M206X"))
    )
    (comp (ref "A09")
      (value "M117")
      (footprint "eagle-import:H807")
      (libsource (lib "eagle-import") (part "M117"))
    )
    (comp (ref "A10")
      (value "M113")
      (footprint "eagle-import:H807")
      (libsource (lib "eagle-import") (part "M113"))
    )
    (comp (ref "B21")
      (value "G879")
      (footprint "eagle-import:H807")
      (libsource (lib "eagle-import") (part "G879"))
    )
    (comp (ref "C10")
      (value "M121")
      (footprint "eagle-import:H807")
      (libsource (lib "eagle-import") (part "M121"))
    )
    (comp (ref "D16")
      (value "M302")
      (footprint "eagle-import:H807")
      (libsource (lib "eagle-import") (part "M302"))
    )
    (comp (ref "C15")
      (value "M113")
      (footprint "eagle-import:H807")
      (libsource (lib "eagle-import") (part "M113"))
    )
    (comp (ref "D08")
      (value "M207")
      (footprint "eagle-import:H807")
      (libsource (lib "eagle-import") (part "M207"))
    )
    (comp (ref "D09")
      (value "M121")
      (footprint "eagle-import:H807")
      (libsource (lib "eagle-import") (part "M121"))
    )
    (comp (ref "A14")
      (value "M302")
      (footprint "eagle-import:H807")
      (libsource (lib "eagle-import") (part "M302"))
    )
    (comp (ref "A15")
      (value "M627")
      (footprint "eagle-import:H807")
      (libsource (lib "eagle-import") (part "M627"))
    )
    (comp (ref "A16")
      (value "M602")
      (footprint "eagle-import:H807")
      (libsource (lib "eagle-import") (part "M602"))
    )
    (comp (ref "B14")
      (value "M206X")
      (footprint "eagle-import:H807")
      (libsource (lib "eagle-import") (part "M206X"))
    )
    (comp (ref "B16")
      (value "M602")
      (footprint "eagle-import:H807")
      (libsource (lib "eagle-import") (part "M602"))
    )
    (comp (ref "C14")
      (value "M206X")
      (footprint "eagle-import:H807")
      (libsource (lib "eagle-import") (part "M206X"))
    )
    (comp (ref "D14")
      (value "M307")
      (footprint "eagle-import:H807")
      (libsource (lib "eagle-import") (part "M307"))
    )
    (comp (ref "D15")
      (value "M401")
      (footprint "eagle-import:H807")
      (libsource (lib "eagle-import") (part "M401"))
    )
    (comp (ref "B09")
      (value "M206X")
      (footprint "eagle-import:H807")
      (libsource (lib "eagle-import") (part "M206X"))
    )
    (comp (ref "C09")
      (value "M206X")
      (footprint "eagle-import:H807")
      (libsource (lib "eagle-import") (part "M206X"))
    )
    (comp (ref "B11")
      (value "M115")
      (footprint "eagle-import:H807")
      (libsource (lib "eagle-import") (part "M115"))
    )
    (comp (ref "A07")
      (value "A07")
      (footprint "eagle-import:H807")
      (libsource (lib "eagle-import") (part "M161"))
    )
    (comp (ref "A22")
      (value "M502")
      (footprint "eagle-import:H807")
      (libsource (lib "eagle-import") (part "M502"))
    )
    (comp (ref "A23")
      (value "M633")
      (footprint "eagle-import:H807")
      (libsource (lib "eagle-import") (part "M633"))
    )
    (comp (ref "B07")
      (value "B07")
      (footprint "eagle-import:H807")
      (libsource (lib "eagle-import") (part "M207"))
    )
    (comp (ref "B22")
      (value "M633")
      (footprint "eagle-import:H807")
      (libsource (lib "eagle-import") (part "M633"))
    )
    (comp (ref "B23")
      (value "W005")
      (footprint "eagle-import:H807")
      (libsource (lib "eagle-import") (part "W005"))
    )
    (comp (ref "C07")
      (value "B07")
      (footprint "eagle-import:H807")
      (libsource (lib "eagle-import") (part "M207"))
    )
    (comp (ref "D07")
      (value "D07")
      (footprint "eagle-import:H807")
      (libsource (lib "eagle-import") (part "M161"))
    )
    (comp (ref "CD18")
      (value "M228")
      (footprint "eagle-import:H807-2")
      (libsource (lib "eagle-import") (part "M228"))
    )
    (comp (ref "A02")
      (value "M903")
      (footprint "eagle-import:H807")
      (libsource (lib "eagle-import") (part "M903"))
    )
    (comp (ref "A03")
      (value "M903")
      (footprint "eagle-import:H807")
      (libsource (lib "eagle-import") (part "M903"))
    )
    (comp (ref "A04")
      (value "M903")
      (footprint "eagle-import:H807")
      (libsource (lib "eagle-import") (part "M903"))
    )
    (comp (ref "A05")
      (value "M903")
      (footprint "eagle-import:H807")
      (libsource (lib "eagle-import") (part "M903"))
    )
    (comp (ref "A06")
      (value "M903")
      (footprint "eagle-import:H807")
      (libsource (lib "eagle-import") (part "M903"))
    )
    (comp (ref "A13")
      (value "H807")
      (footprint "eagle-import:H807")
      (libsource (lib "eagle-import") (part "H807"))
    )
    (comp (ref "A17")
      (value "H807")
      (footprint "eagle-import:H807")
      (libsource (lib "eagle-import") (part "H807"))
    )
    (comp (ref "A24")
      (value "W023")
      (footprint "eagle-import:H807")
      (libsource (lib "eagle-import") (part "W023"))
    )
    (comp (ref "A25")
      (value "M916")
      (footprint "eagle-import:H807")
      (libsource (lib "eagle-import") (part "M916"))
    )
    (comp (ref "A26")
      (value "M916")
      (footprint "eagle-import:H807")
      (libsource (lib "eagle-import") (part "M916"))
    )
    (comp (ref "A27")
      (value "H807")
      (footprint "eagle-import:H807")
      (libsource (lib "eagle-import") (part "H807"))
    )
    (comp (ref "A28")
      (value "H807")
      (footprint "eagle-import:H807")
      (libsource (lib "eagle-import") (part "H807"))
    )
    (comp (ref "B17")
      (value "H807")
      (footprint "eagle-import:H807")
      (libsource (lib "eagle-import") (part "H807"))
    )
    (comp (ref "B24")
      (value "H807")
      (footprint "eagle-import:H807")
      (libsource (lib "eagle-import") (part "H807"))
    )
    (comp (ref "B25")
      (value "H807")
      (footprint "eagle-import:H807")
      (libsource (lib "eagle-import") (part "H807"))
    )
    (comp (ref "B26")
      (value "H807")
      (footprint "eagle-import:H807")
      (libsource (lib "eagle-import") (part "H807"))
    )
    (comp (ref "B27")
      (value "H807")
      (footprint "eagle-import:H807")
      (libsource (lib "eagle-import") (part "H807"))
    )
    (comp (ref "B28")
      (value "H807")
      (footprint "eagle-import:H807")
      (libsource (lib "eagle-import") (part "H807"))
    )
    (comp (ref "C19")
      (value "H807")
      (footprint "eagle-import:H807")
      (libsource (lib "eagle-import") (part "H807"))
    )
    (comp (ref "C20")
      (value "H807")
      (footprint "eagle-import:H807")
      (libsource (lib "eagle-import") (part "H807"))
    )
    (comp (ref "C21")
      (value "H807")
      (footprint "eagle-import:H807")
      (libsource (lib "eagle-import") (part "H807"))
    )
    (comp (ref "C22")
      (value "H807")
      (footprint "eagle-import:H807")
      (libsource (lib "eagle-import") (part "H807"))
    )
    (comp (ref "C23")
      (value "H807")
      (footprint "eagle-import:H807")
      (libsource (lib "eagle-import") (part "H807"))
    )
    (comp (ref "C24")
      (value "H807")
      (footprint "eagle-import:H807")
      (libsource (lib "eagle-import") (part "H807"))
    )
    (comp (ref "C25")
      (value "H807")
      (footprint "eagle-import:H807")
      (libsource (lib "eagle-import") (part "H807"))
    )
    (comp (ref "C26")
      (value "H807")
      (footprint "eagle-import:H807")
      (libsource (lib "eagle-import") (part "H807"))
    )
    (comp (ref "C27")
      (value "H807")
      (footprint "eagle-import:H807")
      (libsource (lib "eagle-import") (part "H807"))
    )
    (comp (ref "C28")
      (value "H807")
      (footprint "eagle-import:H807")
      (libsource (lib "eagle-import") (part "H807"))
    )
    (comp (ref "D01")
      (value "H807")
      (footprint "eagle-import:H807")
      (libsource (lib "eagle-import") (part "H807"))
    )
    (comp (ref "D02")
      (value "M903")
      (footprint "eagle-import:H807")
      (libsource (lib "eagle-import") (part "M903"))
    )
    (comp (ref "D03")
      (value "M903")
      (footprint "eagle-import:H807")
      (libsource (lib "eagle-import") (part "M903"))
    )
    (comp (ref "D04")
      (value "M903")
      (footprint "eagle-import:H807")
      (libsource (lib "eagle-import") (part "M903"))
    )
    (comp (ref "D05")
      (value "M903")
      (footprint "eagle-import:H807")
      (libsource (lib "eagle-import") (part "M903"))
    )
    (comp (ref "D06")
      (value "M903")
      (footprint "eagle-import:H807")
      (libsource (lib "eagle-import") (part "M903"))
    )
    (comp (ref "D19")
      (value "H807")
      (footprint "eagle-import:H807")
      (libsource (lib "eagle-import") (part "H807"))
    )
    (comp (ref "D20")
      (value "H807")
      (footprint "eagle-import:H807")
      (libsource (lib "eagle-import") (part "H807"))
    )
    (comp (ref "D21")
      (value "H807")
      (footprint "eagle-import:H807")
      (libsource (lib "eagle-import") (part "H807"))
    )
    (comp (ref "D22")
      (value "H807")
      (footprint "eagle-import:H807")
      (libsource (lib "eagle-import") (part "H807"))
    )
    (comp (ref "D23")
      (value "H807")
      (footprint "eagle-import:H807")
      (libsource (lib "eagle-import") (part "H807"))
    )
    (comp (ref "D24")
      (value "H807")
      (footprint "eagle-import:H807")
      (libsource (lib "eagle-import") (part "H807"))
    )
    (comp (ref "D25")
      (value "H807")
      (footprint "eagle-import:H807")
      (libsource (lib "eagle-import") (part "H807"))
    )
    (comp (ref "D26")
      (value "H807")
      (footprint "eagle-import:H807")
      (libsource (lib "eagle-import") (part "H807"))
    )
    (comp (ref "D27")
      (value "H807")
      (footprint "eagle-import:H807")
      (libsource (lib "eagle-import") (part "H807"))
    )
    (comp (ref "D28")
      (value "H807")
      (footprint "eagle-import:H807")
      (libsource (lib "eagle-import") (part "H807"))
    )
    (comp (ref "A18")
      (value "G888")
      (footprint "eagle-import:H807")
      (libsource (lib "eagle-import") (part "G888"))
    )
    (comp (ref "A20")
      (value "G888")
      (footprint "eagle-import:H807")
      (libsource (lib "eagle-import") (part "G888"))
    )
    (comp (ref "A21")
      (value "G888")
      (footprint "eagle-import:H807")
      (libsource (lib "eagle-import") (part "G888"))
    )
    (comp (ref "AB01")
      (value "G821")
      (footprint "eagle-import:H807-2")
      (libsource (lib "eagle-import") (part "G821"))
    )
    (comp (ref "AB19")
      (value "W032")
      (footprint "eagle-import:H807-2")
      (libsource (lib "eagle-import") (part "W032"))
    )
    (comp (ref "B18")
      (value "G888")
      (footprint "eagle-import:H807")
      (libsource (lib "eagle-import") (part "G888"))
    )
    (comp (ref "B20")
      (value "G888")
      (footprint "eagle-import:H807")
      (libsource (lib "eagle-import") (part "G888"))
    )
    (comp (ref "B02")
      (value "M623")
      (footprint "eagle-import:H807")
      (libsource (lib "eagle-import") (part "M623"))
    )
    (comp (ref "B03")
      (value "M623")
      (footprint "eagle-import:H807")
      (libsource (lib "eagle-import") (part "M623"))
    )
    (comp (ref "B04")
      (value "M623")
      (footprint "eagle-import:H807")
      (libsource (lib "eagle-import") (part "M623"))
    )
    (comp (ref "B05")
      (value "M623")
      (footprint "eagle-import:H807")
      (libsource (lib "eagle-import") (part "M623"))
    )
    (comp (ref "C02")
      (value "M101-ARRAY")
      (footprint "eagle-import:H807")
      (libsource (lib "eagle-import") (part "M101-ARRAY"))
    )
    (comp (ref "C03")
      (value "M101-ARRAY")
      (footprint "eagle-import:H807")
      (libsource (lib "eagle-import") (part "M101-ARRAY"))
    )
  )
  (nets
    (net (code "1") (name "+3V@A09U1") (class "Default")
      (node (ref "A07") (pin "S1") (pinfunction "EN2_S1") (pintype "input"))
      (node (ref "A07") (pin "S2") (pinfunction "EN1_S2") (pintype "input"))
      (node (ref "A07") (pin "T2") (pinfunction "EN3_T2") (pintype "input"))
      (node (ref "A08") (pin "D1") (pinfunction "S_D1") (pintype "input"))
      (node (ref "A08") (pin "F2") (pinfunction "S_F2") (pintype "input"))
      (node (ref "A08") (pin "K2") (pinfunction "R_K2") (pintype "input"))
      (node (ref "A09") (pin "U1") (pinfunction "P$1_U1") (pintype "output"))
      (node (ref "B13") (pin "R1") (pinfunction "S_R1") (pintype "input"))
      (node (ref "B13") (pin "U2") (pinfunction "S_U2") (pintype "input"))
    )
    (net (code "2") (name "+3V@B12U1") (class "Default")
      (node (ref "B12") (pin "U1") (pinfunction "P$1_U1") (pintype "output"))
      (node (ref "B13") (pin "D1") (pinfunction "S_D1") (pintype "input"))
      (node (ref "B13") (pin "F2") (pinfunction "S_F2") (pintype "input"))
      (node (ref "B13") (pin "K1") (pinfunction "S_K1") (pintype "input"))
      (node (ref "B14") (pin "A1") (pinfunction "R_A1") (pintype "input"))
      (node (ref "B14") (pin "K2") (pinfunction "R_K2") (pintype "input"))
      (node (ref "B14") (pin "N2") (pinfunction "S_N2") (pintype "input"))
      (node (ref "B14") (pin "R1") (pinfunction "S_R1") (pintype "input"))
      (node (ref "B14") (pin "U2") (pinfunction "S_U2") (pintype "input"))
    )
    (net (code "3") (name "+3V@C08U1") (class "Default")
      (node (ref "C02") (pin "C1") (pinfunction "ENABLE_C1") (pintype "input"))
      (node (ref "C05") (pin "J1") (pinfunction "IN2_J1") (pintype "input"))
      (node (ref "C08") (pin "U1") (pinfunction "P$1_U1") (pintype "output"))
    )
    (net (code "4") (name "+3V@C15U1") (class "Default")
      (node (ref "C14") (pin "A1") (pinfunction "R_A1") (pintype "input"))
      (node (ref "C14") (pin "D1") (pinfunction "S_D1") (pintype "input"))
      (node (ref "C14") (pin "F2") (pinfunction "S_F2") (pintype "input"))
      (node (ref "C14") (pin "K1") (pinfunction "S_K1") (pintype "input"))
      (node (ref "C14") (pin "K2") (pinfunction "R_K2") (pintype "input"))
      (node (ref "C15") (pin "U1") (pinfunction "P$1_U1") (pintype "output"))
      (node (ref "C16") (pin "H2") (pinfunction "IN4_H2") (pintype "input"))
    )
    (net (code "5") (name "+3V@D09U1") (class "Default")
      (node (ref "D07") (pin "S1") (pinfunction "EN2_S1") (pintype "input"))
      (node (ref "D07") (pin "S2") (pinfunction "EN1_S2") (pintype "input"))
      (node (ref "D07") (pin "T2") (pinfunction "EN3_T2") (pintype "input"))
      (node (ref "D09") (pin "U1") (pinfunction "P$1_U1") (pintype "output"))
    )
    (net (code "6") (name "+3V@D10U1") (class "Default")
      (node (ref "D10") (pin "L2") (pinfunction "IN6_L2") (pintype "input"))
      (node (ref "D10") (pin "M2") (pinfunction "IN7_M2") (pintype "input"))
      (node (ref "D10") (pin "N2") (pinfunction "IN8_N2") (pintype "input"))
      (node (ref "D10") (pin "U1") (pinfunction "P$1_U1") (pintype "output"))
      (node (ref "D11") (pin "K2") (pinfunction "R_K2") (pintype "input"))
      (node (ref "D14") (pin "M1") (pinfunction "M1_M1") (pintype "input"))
    )
    (net (code "7") (name "+11V") (class "Default")
      (node (ref "AB01") (pin "BM2") (pinfunction "+11V_BM2") (pintype "power_in"))
    )
    (net (code "8") (name "-15V") (class "Default")
      (node (ref "AB01") (pin "AB2") (pinfunction "-15V_AB2") (pintype "power_in"))
      (node (ref "AB01") (pin "AE2") (pinfunction "-15V_AE2") (pintype "power_in"))
      (node (ref "AB01") (pin "AF2") (pinfunction "-15V_AF2") (pintype "power_in"))
    )
    (net (code "9") (name "00") (class "Default")
      (node (ref "A07") (pin "D2") (pinfunction "O0_D2") (pintype "output"))
    )
    (net (code "10") (name "0_TO_DTB") (class "Default")
      (node (ref "A11") (pin "M1") (pinfunction "OUT_M1") (pintype "output"))
      (node (ref "C11") (pin "R1") (pinfunction "IN2_R1") (pintype "input"))
    )
    (net (code "11") (name "0_TO_EF") (class "Default")
      (node (ref "A10") (pin "K2") (pinfunction "OUT_K2") (pintype "output"))
      (node (ref "A11") (pin "E2") (pinfunction "IN_E2") (pintype "input"))
    )
    (net (code "12") (name "0_TO_STA") (class "Default")
      (node (ref "A10") (pin "N2") (pinfunction "OUT_N2") (pintype "output"))
      (node (ref "A11") (pin "N1") (pinfunction "IN_N1") (pintype "input"))
    )
    (net (code "13") (name "01") (class "Default")
      (node (ref "A07") (pin "E2") (pinfunction "O1_E2") (pintype "output"))
    )
    (net (code "14") (name "1_TO_DF") (class "Default")
      (node (ref "A08") (pin "H1") (pinfunction "C_H1") (pintype "input"))
      (node (ref "C12") (pin "J1") (pinfunction "OUT_J1") (pintype "output"))
      (node (ref "C12") (pin "L1") (pinfunction "IN2_L1") (pintype "input"))
      (node (ref "D11") (pin "L2") (pinfunction "C_L2") (pintype "input"))
    )
    (net (code "15") (name "1_TO_DTF") (class "Default")
      (node (ref "B12") (pin "P2") (pinfunction "OUT_P2") (pintype "output"))
      (node (ref "D11") (pin "S2") (pinfunction "C_S2") (pintype "input"))
    )
    (net (code "16") (name "02") (class "Default")
      (node (ref "A07") (pin "J2") (pinfunction "O2_J2") (pintype "output"))
    )
    (net (code "17") (name "03") (class "Default")
      (node (ref "A07") (pin "N2") (pinfunction "O3_N2") (pintype "output"))
    )
    (net (code "18") (name "04") (class "Default")
      (node (ref "A07") (pin "F2") (pinfunction "O4_F2") (pintype "output"))
    )
    (net (code "19") (name "05") (class "Default")
      (node (ref "A07") (pin "M2") (pinfunction "O5_M2") (pintype "output"))
    )
    (net (code "20") (name "06") (class "Default")
      (node (ref "A07") (pin "H2") (pinfunction "O6_H2") (pintype "output"))
    )
    (net (code "21") (name "07") (class "Default")
      (node (ref "A07") (pin "L2") (pinfunction "O7_L2") (pintype "output"))
    )
    (net (code "22") (name "76") (class "Default")
      (node (ref "C06") (pin "S2") (pinfunction "IN_S2") (pintype "input"))
      (node (ref "IC2") (pin "10") (pinfunction "I1_10") (pintype "input"))
      (node (ref "IC2") (pin "13") (pinfunction "I1_13") (pintype "input"))
      (node (ref "IC2") (pin "3") (pinfunction "O_3") (pintype "output"))
      (node (ref "IC2") (pin "5") (pinfunction "I1_5") (pintype "input"))
    )
    (net (code "23") (name "76+77") (class "Default")
      (node (ref "C03") (pin "C1") (pinfunction "ENABLE_C1") (pintype "input"))
      (node (ref "D12") (pin "V2") (pinfunction "OUT_V2") (pintype "output"))
    )
    (net (code "24") (name "77") (class "Default")
      (node (ref "C06") (pin "U2") (pinfunction "IN_U2") (pintype "input"))
      (node (ref "IC7") (pin "3") (pinfunction "O_3") (pintype "output"))
      (node (ref "IC8") (pin "10") (pinfunction "I1_10") (pintype "input"))
      (node (ref "IC8") (pin "13") (pinfunction "I1_13") (pintype "input"))
      (node (ref "IC8") (pin "5") (pinfunction "I1_5") (pintype "input"))
    )
    (net (code "25") (name "ADDR_ACC") (class "Default")
      (node (ref "C02") (pin "V2") (pinfunction "O15_V2") (pintype "output"))
      (node (ref "C17") (pin "N1") (pinfunction "IN_N1") (pintype "input"))
    )
    (net (code "26") (name "B-BRK") (class "Default")
      (node (ref "B10") (pin "R2") (pinfunction "IN1_R2") (pintype "input"))
      (node (ref "B10") (pin "S2") (pinfunction "IN2_S2") (pintype "input"))
      (node (ref "B10") (pin "T2") (pinfunction "IN3_T2") (pintype "input"))
      (node (ref "B10") (pin "U2") (pinfunction "IN4_U2") (pintype "input"))
      (node (ref "D12") (pin "M1") (pinfunction "IN1_M1") (pintype "input"))
      (node (ref "IC9") (pin "12") (pinfunction "O_12") (pintype "output"))
    )
    (net (code "27") (name "B-RUN") (class "Default")
      (node (ref "B11") (pin "N2") (pinfunction "IN1_N2") (pintype "input"))
      (node (ref "IC9") (pin "10") (pinfunction "O_10") (pintype "output"))
    )
    (net (code "28") (name "B-XSTA") (class "Default")
      (node (ref "A10") (pin "E2") (pinfunction "IN2_E2") (pintype "input"))
      (node (ref "C11") (pin "P2") (pinfunction "IN1_P2") (pintype "input"))
      (node (ref "D12") (pin "E1") (pinfunction "OUT_E1") (pintype "output"))
    )
    (net (code "29") (name "BAC_00") (class "Default")
      (node (ref "B06") (pin "B1") (pinfunction "OUT_B1") (pintype "output"))
      (node (ref "B07") (pin "C1") (pinfunction "C1_C1") (pintype "input"))
      (node (ref "B07") (pin "D1") (pinfunction "D1_D1") (pintype "input"))
    )
    (net (code "30") (name "BAC_01") (class "Default")
      (node (ref "B06") (pin "E1") (pinfunction "OUT_E1") (pintype "output"))
      (node (ref "B07") (pin "E2") (pinfunction "E2_E2") (pintype "input"))
      (node (ref "B07") (pin "F2") (pinfunction "F2_F2") (pintype "input"))
    )
    (net (code "31") (name "BAC_02") (class "Default")
      (node (ref "B06") (pin "H1") (pinfunction "OUT_H1") (pintype "output"))
      (node (ref "B07") (pin "J1") (pinfunction "J1_J1") (pintype "input"))
      (node (ref "B07") (pin "K1") (pinfunction "K1_K1") (pintype "input"))
    )
    (net (code "32") (name "BAC_03") (class "Default")
      (node (ref "B06") (pin "K1") (pinfunction "OUT_K1") (pintype "output"))
      (node (ref "B07") (pin "M2") (pinfunction "M2_M2") (pintype "input"))
      (node (ref "B07") (pin "N2") (pinfunction "N2_N2") (pintype "input"))
    )
    (net (code "33") (name "BAC_04") (class "Default")
      (node (ref "B06") (pin "M1") (pinfunction "OUT_M1") (pintype "output"))
      (node (ref "C07") (pin "M2") (pinfunction "M2_M2") (pintype "input"))
      (node (ref "C07") (pin "N2") (pinfunction "N2_N2") (pintype "input"))
    )
    (net (code "34") (name "BAC_05") (class "Default")
      (node (ref "B06") (pin "P1") (pinfunction "OUT_P1") (pintype "output"))
      (node (ref "B07") (pin "P1") (pinfunction "P1_P1") (pintype "input"))
      (node (ref "B07") (pin "R1") (pinfunction "R1_R1") (pintype "input"))
    )
    (net (code "35") (name "BAC_06") (class "Default")
      (node (ref "B06") (pin "S1") (pinfunction "OUT_S1") (pintype "output"))
      (node (ref "B07") (pin "T2") (pinfunction "T2_T2") (pintype "input"))
      (node (ref "B07") (pin "U2") (pinfunction "U2_U2") (pintype "input"))
      (node (ref "IC4") (pin "2") (pinfunction "D_2") (pintype "input"))
    )
    (net (code "36") (name "BAC_07") (class "Default")
      (node (ref "B06") (pin "U1") (pinfunction "OUT_U1") (pintype "output"))
      (node (ref "C07") (pin "C1") (pinfunction "C1_C1") (pintype "input"))
      (node (ref "C07") (pin "D1") (pinfunction "D1_D1") (pintype "input"))
      (node (ref "IC4") (pin "12") (pinfunction "D_12") (pintype "input"))
    )
    (net (code "37") (name "BAC_08") (class "Default")
      (node (ref "B06") (pin "D2") (pinfunction "OUT_D2") (pintype "output"))
      (node (ref "C07") (pin "E2") (pinfunction "E2_E2") (pintype "input"))
      (node (ref "C07") (pin "F2") (pinfunction "F2_F2") (pintype "input"))
      (node (ref "IC5") (pin "2") (pinfunction "D_2") (pintype "input"))
    )
    (net (code "38") (name "BAC_09") (class "Default")
      (node (ref "B06") (pin "F2") (pinfunction "OUT_F2") (pintype "output"))
      (node (ref "C07") (pin "J1") (pinfunction "J1_J1") (pintype "input"))
      (node (ref "C07") (pin "K1") (pinfunction "K1_K1") (pintype "input"))
    )
    (net (code "39") (name "BAC_10") (class "Default")
      (node (ref "B06") (pin "J2") (pinfunction "OUT_J2") (pintype "output"))
    )
    (net (code "40") (name "BAC_11") (class "Default")
      (node (ref "B06") (pin "L2") (pinfunction "OUT_L2") (pintype "output"))
    )
    (net (code "41") (name "BLK_IN_SYNC") (class "Default")
      (node (ref "C11") (pin "E2") (pinfunction "IN2_E2") (pintype "input"))
      (node (ref "C13") (pin "S1") (pinfunction "OUT_S1") (pintype "output"))
      (node (ref "CD18") (pin "AP2") (pinfunction "AP2_AP2") (pintype "input"))
    )
    (net (code "42") (name "BMB_00") (class "Default")
      (node (ref "C06") (pin "B1") (pinfunction "OUT_B1") (pintype "output"))
      (node (ref "C08") (pin "B1") (pinfunction "IN1B_B1") (pintype "input"))
    )
    (net (code "43") (name "BMB_01") (class "Default")
      (node (ref "C06") (pin "E1") (pinfunction "OUT_E1") (pintype "output"))
      (node (ref "C08") (pin "H1") (pinfunction "IN1B_H1") (pintype "input"))
    )
    (net (code "44") (name "BMB_02") (class "Default")
      (node (ref "C06") (pin "H1") (pinfunction "OUT_H1") (pintype "output"))
      (node (ref "C08") (pin "N1") (pinfunction "IN1B_N1") (pintype "input"))
    )
    (net (code "45") (name "BMB_03") (class "Default")
      (node (ref "C06") (pin "K1") (pinfunction "OUT_K1") (pintype "output"))
      (node (ref "C08") (pin "E2") (pinfunction "IN1B_E2") (pintype "input"))
    )
    (net (code "46") (name "BMB_04") (class "Default")
      (node (ref "C06") (pin "M1") (pinfunction "OUT_M1") (pintype "output"))
      (node (ref "C08") (pin "L2") (pinfunction "IN1B_L2") (pintype "input"))
    )
    (net (code "47") (name "BMB_05") (class "Default")
      (node (ref "C06") (pin "P1") (pinfunction "OUT_P1") (pintype "output"))
      (node (ref "C08") (pin "S2") (pinfunction "IN1B_S2") (pintype "input"))
    )
    (net (code "48") (name "BMB_06") (class "Default")
      (node (ref "B08") (pin "B1") (pinfunction "IN2_B1") (pintype "input"))
      (node (ref "C06") (pin "S1") (pinfunction "OUT_S1") (pintype "output"))
    )
    (net (code "49") (name "BMB_07") (class "Default")
      (node (ref "B08") (pin "E1") (pinfunction "IN2_E1") (pintype "input"))
      (node (ref "C06") (pin "U1") (pinfunction "OUT_U1") (pintype "output"))
    )
    (net (code "50") (name "BMB_08") (class "Default")
      (node (ref "B08") (pin "E2") (pinfunction "IN2_E2") (pintype "input"))
      (node (ref "C06") (pin "D2") (pinfunction "OUT_D2") (pintype "output"))
    )
    (net (code "51") (name "BMB_09") (class "Default")
      (node (ref "B08") (pin "M1") (pinfunction "IN2_M1") (pintype "input"))
      (node (ref "C06") (pin "F2") (pinfunction "OUT_F2") (pintype "output"))
    )
    (net (code "52") (name "BMB_10") (class "Default")
      (node (ref "B08") (pin "R1") (pinfunction "IN2_R1") (pintype "input"))
      (node (ref "C06") (pin "J2") (pinfunction "OUT_J2") (pintype "output"))
    )
    (net (code "53") (name "BMB_11") (class "Default")
      (node (ref "B08") (pin "J1") (pinfunction "IN2_J1") (pintype "input"))
      (node (ref "C06") (pin "L2") (pinfunction "OUT_L2") (pintype "output"))
    )
    (net (code "54") (name "BMB_TO_DTB") (class "Default")
      (node (ref "B08") (pin "A1") (pinfunction "IN1_A1") (pintype "input"))
      (node (ref "B08") (pin "D1") (pinfunction "IN1_D1") (pintype "input"))
      (node (ref "B08") (pin "D2") (pinfunction "IN1_D2") (pintype "input"))
      (node (ref "B08") (pin "H1") (pinfunction "IN1_H1") (pintype "input"))
      (node (ref "B08") (pin "L1") (pinfunction "IN1_L1") (pintype "input"))
      (node (ref "B08") (pin "P1") (pinfunction "IN1_P1") (pintype "input"))
      (node (ref "C08") (pin "A1") (pinfunction "IN1A_A1") (pintype "input"))
      (node (ref "C08") (pin "D2") (pinfunction "IN1A_D2") (pintype "input"))
      (node (ref "C08") (pin "F1") (pinfunction "IN1A_F1") (pintype "input"))
      (node (ref "C08") (pin "K2") (pinfunction "IN1A_K2") (pintype "input"))
      (node (ref "C08") (pin "M1") (pinfunction "IN1A_M1") (pintype "input"))
      (node (ref "C08") (pin "R2") (pinfunction "IN1A_R2") (pintype "input"))
      (node (ref "D12") (pin "L1") (pinfunction "OUT_L1") (pintype "output"))
    )
    (net (code "55") (name "BMR00") (class "Default")
      (node (ref "A23") (pin "F1") (pinfunction "A_F1") (pintype "input"))
      (node (ref "B14") (pin "P2") (pinfunction "1_P2") (pintype "output"))
    )
    (net (code "56") (name "BMR01") (class "Default")
      (node (ref "A23") (pin "B1") (pinfunction "B_B1") (pintype "input"))
      (node (ref "B14") (pin "F1") (pinfunction "0_F1") (pintype "output"))
    )
    (net (code "57") (name "C00") (class "Default")
      (node (ref "A12") (pin "L2") (pinfunction "IN1_L2") (pintype "input"))
      (node (ref "A26") (pin "E2") (pinfunction "P$2_E2") (pintype "bidirectional"))
      (node (ref "B12") (pin "R2") (pinfunction "IN1_R2") (pintype "input"))
      (node (ref "B13") (pin "S1") (pinfunction "1_S1") (pintype "output"))
      (node (ref "C15") (pin "E2") (pinfunction "IN2_E2") (pintype "input"))
      (node (ref "D10") (pin "C1") (pinfunction "IN3_C1") (pintype "input"))
    )
    (net (code "58") (name "C01") (class "Default")
      (node (ref "A12") (pin "M2") (pinfunction "IN2_M2") (pintype "input"))
      (node (ref "A26") (pin "F2") (pinfunction "P$2_F2") (pintype "bidirectional"))
      (node (ref "B10") (pin "J1") (pinfunction "IN3_J1") (pintype "input"))
      (node (ref "B11") (pin "V2") (pinfunction "IN3_V2") (pintype "input"))
      (node (ref "B13") (pin "P2") (pinfunction "1_P2") (pintype "output"))
    )
    (net (code "59") (name "CK00") (class "Default")
      (node (ref "A18") (pin "P2") (pinfunction "P2_P2") (pintype "input"))
      (node (ref "B14") (pin "S1") (pinfunction "1_S1") (pintype "output"))
    )
    (net (code "60") (name "CK01") (class "Default")
      (node (ref "B14") (pin "P1") (pinfunction "D_P1") (pintype "input"))
      (node (ref "B14") (pin "V2") (pinfunction "1_V2") (pintype "output"))
      (node (ref "C16") (pin "N1") (pinfunction "IN2_N1") (pintype "input"))
      (node (ref "C16") (pin "P1") (pinfunction "IN3_P1") (pintype "input"))
      (node (ref "C16") (pin "R1") (pinfunction "IN4_R1") (pintype "input"))
    )
    (net (code "61") (name "COMP+SH") (class "Default")
      (node (ref "A12") (pin "D2") (pinfunction "IN1_D2") (pintype "input"))
      (node (ref "C14") (pin "B1") (pinfunction "C_B1") (pintype "input"))
      (node (ref "C14") (pin "D2") (pinfunction "C_D2") (pintype "input"))
      (node (ref "C14") (pin "H1") (pinfunction "C_H1") (pintype "input"))
      (node (ref "C15") (pin "K1") (pinfunction "OUT_K1") (pintype "output"))
    )
    (net (code "62") (name "CSTA") (class "Default")
      (node (ref "D16") (pin "P2") (pinfunction "K2_P2") (pintype "input"))
      (node (ref "IC3") (pin "4") (pinfunction "O_4") (pintype "output"))
    )
    (net (code "63") (name "DATA") (class "Default")
      (node (ref "A26") (pin "M1") (pinfunction "P$2_M1") (pintype "bidirectional"))
      (node (ref "C13") (pin "F1") (pinfunction "IN_F1") (pintype "input"))
      (node (ref "CD18") (pin "BK2") (pinfunction "BK2_BK2") (pintype "output"))
    )
    (net (code "64") (name "DF") (class "Default")
      (node (ref "A10") (pin "P2") (pinfunction "IN1_P2") (pintype "input"))
      (node (ref "A26") (pin "E1") (pinfunction "P$2_E1") (pintype "bidirectional"))
      (node (ref "D11") (pin "R2") (pinfunction "0_R2") (pintype "output"))
    )
    (net (code "65") (name "DTB_00") (class "Default")
      (node (ref "A25") (pin "A2") (pinfunction "P$2_A2") (pintype "bidirectional"))
      (node (ref "C09") (pin "E1") (pinfunction "1_E1") (pintype "output"))
      (node (ref "C10") (pin "B1") (pinfunction "IN1B_B1") (pintype "input"))
      (node (ref "D09") (pin "D2") (pinfunction "IN1A_D2") (pintype "input"))
    )
    (net (code "66") (name "DTB_01") (class "Default")
      (node (ref "A25") (pin "B2") (pinfunction "P$2_B2") (pintype "bidirectional"))
      (node (ref "C09") (pin "H2") (pinfunction "1_H2") (pintype "output"))
      (node (ref "C10") (pin "H1") (pinfunction "IN1B_H1") (pintype "input"))
      (node (ref "D09") (pin "K2") (pinfunction "IN1A_K2") (pintype "input"))
    )
    (net (code "67") (name "DTB_02") (class "Default")
      (node (ref "A25") (pin "C2") (pinfunction "P$2_C2") (pintype "bidirectional"))
      (node (ref "C09") (pin "L1") (pinfunction "1_L1") (pintype "output"))
      (node (ref "C10") (pin "N1") (pinfunction "IN1B_N1") (pintype "input"))
      (node (ref "D09") (pin "R2") (pinfunction "IN1A_R2") (pintype "input"))
    )
    (net (code "68") (name "DTB_03") (class "Default")
      (node (ref "A25") (pin "D2") (pinfunction "P$2_D2") (pintype "bidirectional"))
      (node (ref "C09") (pin "C1") (pinfunction "D_C1") (pintype "input"))
      (node (ref "C09") (pin "P2") (pinfunction "1_P2") (pintype "output"))
    )
    (net (code "69") (name "DTB_04") (class "Default")
      (node (ref "A25") (pin "E2") (pinfunction "P$2_E2") (pintype "bidirectional"))
      (node (ref "C09") (pin "E2") (pinfunction "D_E2") (pintype "input"))
      (node (ref "C09") (pin "S1") (pinfunction "1_S1") (pintype "output"))
    )
    (net (code "70") (name "DTB_05") (class "Default")
      (node (ref "A25") (pin "F2") (pinfunction "P$2_F2") (pintype "bidirectional"))
      (node (ref "C09") (pin "J1") (pinfunction "D_J1") (pintype "input"))
      (node (ref "C09") (pin "V2") (pinfunction "1_V2") (pintype "output"))
    )
    (net (code "71") (name "DTB_06") (class "Default")
      (node (ref "A25") (pin "H2") (pinfunction "P$2_H2") (pintype "bidirectional"))
      (node (ref "B09") (pin "E1") (pinfunction "1_E1") (pintype "output"))
      (node (ref "C09") (pin "M2") (pinfunction "D_M2") (pintype "input"))
    )
    (net (code "72") (name "DTB_07") (class "Default")
      (node (ref "A25") (pin "J2") (pinfunction "P$2_J2") (pintype "bidirectional"))
      (node (ref "B09") (pin "V2") (pinfunction "1_V2") (pintype "output"))
      (node (ref "C09") (pin "P1") (pinfunction "D_P1") (pintype "input"))
    )
    (net (code "73") (name "DTB_08") (class "Default")
      (node (ref "A25") (pin "K2") (pinfunction "P$2_K2") (pintype "bidirectional"))
      (node (ref "B09") (pin "L1") (pinfunction "1_L1") (pintype "output"))
      (node (ref "C09") (pin "T2") (pinfunction "D_T2") (pintype "input"))
    )
    (net (code "74") (name "DTB_09") (class "Default")
      (node (ref "A25") (pin "L2") (pinfunction "P$2_L2") (pintype "bidirectional"))
      (node (ref "B09") (pin "C1") (pinfunction "D_C1") (pintype "input"))
      (node (ref "B09") (pin "P2") (pinfunction "1_P2") (pintype "output"))
    )
    (net (code "75") (name "DTB_10") (class "Default")
      (node (ref "A25") (pin "M2") (pinfunction "P$2_M2") (pintype "bidirectional"))
      (node (ref "B09") (pin "S1") (pinfunction "1_S1") (pintype "output"))
      (node (ref "B09") (pin "T2") (pinfunction "D_T2") (pintype "input"))
    )
    (net (code "76") (name "DTB_11") (class "Default")
      (node (ref "A25") (pin "N2") (pinfunction "P$2_N2") (pintype "bidirectional"))
      (node (ref "B09") (pin "H2") (pinfunction "1_H2") (pintype "output"))
      (node (ref "B09") (pin "J1") (pinfunction "D_J1") (pintype "input"))
    )
    (net (code "77") (name "DTF") (class "Default")
      (node (ref "A08") (pin "J1") (pinfunction "D_J1") (pintype "input"))
      (node (ref "A12") (pin "M1") (pinfunction "IN2_M1") (pintype "input"))
      (node (ref "A26") (pin "C1") (pinfunction "P$2_C1") (pintype "bidirectional"))
      (node (ref "D11") (pin "V1") (pinfunction "0_V1") (pintype "output"))
    )
    (net (code "78") (name "DTSF") (class "Default")
      (node (ref "A12") (pin "R1") (pinfunction "IN2_R1") (pintype "input"))
      (node (ref "IC9") (pin "6") (pinfunction "O_6") (pintype "output"))
    )
    (net (code "79") (name "EF") (class "Default")
      (node (ref "A11") (pin "J1") (pinfunction "IN_J1") (pintype "input"))
      (node (ref "A12") (pin "F1") (pinfunction "OUT_F1") (pintype "output"))
      (node (ref "A12") (pin "L1") (pinfunction "IN1_L1") (pintype "input"))
      (node (ref "A25") (pin "N1") (pinfunction "P$2_N1") (pintype "bidirectional"))
    )
    (net (code "80") (name "END") (class "Default")
      (node (ref "A08") (pin "E1") (pinfunction "1_E1") (pintype "output"))
      (node (ref "A25") (pin "R1") (pinfunction "P$2_R1") (pintype "bidirectional"))
    )
    (net (code "81") (name "ENI") (class "Default")
      (node (ref "A12") (pin "H1") (pinfunction "IN1_H1") (pintype "input"))
      (node (ref "A25") (pin "L1") (pinfunction "P$2_L1") (pintype "bidirectional"))
      (node (ref "C07") (pin "L1") (pinfunction "L1_L1") (pintype "output"))
    )
    (net (code "82") (name "FR_00") (class "Default")
      (node (ref "A25") (pin "F1") (pinfunction "P$2_F1") (pintype "bidirectional"))
      (node (ref "B07") (pin "S1") (pinfunction "S1_S1") (pintype "output"))
      (node (ref "B12") (pin "E2") (pinfunction "IN2_E2") (pintype "input"))
      (node (ref "C12") (pin "U2") (pinfunction "IN2_U2") (pintype "input"))
    )
    (net (code "83") (name "FR_01") (class "Default")
      (node (ref "A10") (pin "H1") (pinfunction "IN1_H1") (pintype "input"))
      (node (ref "A25") (pin "H1") (pinfunction "P$2_H1") (pintype "bidirectional"))
      (node (ref "B07") (pin "V2") (pinfunction "V2_V2") (pintype "output"))
      (node (ref "B15") (pin "M1") (pinfunction "IN2_M1") (pintype "input"))
      (node (ref "C15") (pin "D1") (pinfunction "IN1_D1") (pintype "input"))
      (node (ref "D07") (pin "V2") (pinfunction "IN2_V2") (pintype "input"))
      (node (ref "D12") (pin "R1") (pinfunction "IN4_R1") (pintype "input"))
    )
    (net (code "84") (name "FR_02") (class "Default")
      (node (ref "A25") (pin "J1") (pinfunction "P$2_J1") (pintype "bidirectional"))
      (node (ref "C07") (pin "E1") (pinfunction "E1_E1") (pintype "output"))
      (node (ref "D07") (pin "U2") (pinfunction "IN1_U2") (pintype "input"))
    )
    (net (code "85") (name "FR_03") (class "Default")
      (node (ref "A25") (pin "K1") (pinfunction "P$2_K1") (pintype "bidirectional"))
      (node (ref "B15") (pin "R2") (pinfunction "IN2_R2") (pintype "input"))
      (node (ref "C07") (pin "H2") (pinfunction "H2_H2") (pintype "output"))
      (node (ref "D07") (pin "V1") (pinfunction "IN0_V1") (pintype "input"))
    )
    (net (code "86") (name "GND") (class "Default")
      (node (ref "A05") (pin "B1") (pinfunction "P$2_B1") (pintype "bidirectional"))
      (node (ref "A05") (pin "D1") (pinfunction "P$2_D1") (pintype "bidirectional"))
      (node (ref "A05") (pin "D2") (pinfunction "P$2_D2") (pintype "bidirectional"))
      (node (ref "A05") (pin "E1") (pinfunction "P$2_E1") (pintype "bidirectional"))
      (node (ref "A05") (pin "H1") (pinfunction "P$2_H1") (pintype "bidirectional"))
      (node (ref "A05") (pin "J1") (pinfunction "P$2_J1") (pintype "bidirectional"))
      (node (ref "A05") (pin "L1") (pinfunction "P$2_L1") (pintype "bidirectional"))
      (node (ref "A05") (pin "M1") (pinfunction "P$2_M1") (pintype "bidirectional"))
      (node (ref "A05") (pin "P1") (pinfunction "P$2_P1") (pintype "bidirectional"))
      (node (ref "A05") (pin "S1") (pinfunction "P$2_S1") (pintype "bidirectional"))
      (node (ref "A06") (pin "K2") (pinfunction "P$2_K2") (pintype "bidirectional"))
      (node (ref "A07") (pin "U1") (pinfunction "IN*_U1") (pintype "input"))
      (node (ref "A08") (pin "T2") (pinfunction "D_T2") (pintype "input"))
      (node (ref "A23") (pin "C1") (pinfunction "C_C1") (pintype "input"))
      (node (ref "A23") (pin "F2") (pinfunction "C_F2") (pintype "input"))
      (node (ref "A23") (pin "J1") (pinfunction "C_J1") (pintype "input"))
      (node (ref "A23") (pin "M2") (pinfunction "C_M2") (pintype "input"))
      (node (ref "A23") (pin "P1") (pinfunction "C_P1") (pintype "input"))
      (node (ref "A23") (pin "T2") (pinfunction "C_T2") (pintype "input"))
      (node (ref "A25") (pin "M1") (pinfunction "P$2_M1") (pintype "bidirectional"))
      (node (ref "A26") (pin "D2") (pinfunction "P$2_D2") (pintype "bidirectional"))
      (node (ref "A26") (pin "U2") (pinfunction "P$2_U2") (pintype "bidirectional"))
      (node (ref "A26") (pin "V1") (pinfunction "P$2_V1") (pintype "bidirectional"))
      (node (ref "AB01") (pin "AC2") (pinfunction "GND_AC2") (pintype "power_in"))
      (node (ref "AB01") (pin "AH2") (pinfunction "GND_AH2") (pintype "power_in"))
      (node (ref "AB01") (pin "AK2") (pinfunction "GND_AK2") (pintype "power_in"))
      (node (ref "AB01") (pin "AL2") (pinfunction "GND_AL2") (pintype "power_in"))
      (node (ref "AB01") (pin "AT1") (pinfunction "GND_AT1") (pintype "power_in"))
      (node (ref "AB01") (pin "BC2") (pinfunction "GND_BC2") (pintype "power_in"))
      (node (ref "AB01") (pin "BD2") (pinfunction "GND_BD2") (pintype "power_in"))
      (node (ref "AB01") (pin "BH2") (pinfunction "GND_BH2") (pintype "power_in"))
      (node (ref "AB01") (pin "BK2") (pinfunction "GND_BK2") (pintype "power_in"))
      (node (ref "AB01") (pin "BL2") (pinfunction "GND_BL2") (pintype "power_in"))
      (node (ref "AB01") (pin "BT1") (pinfunction "GND_BT1") (pintype "power_in"))
      (node (ref "AB19") (pin "AJ2") (pinfunction "P$2_AJ2") (pintype "bidirectional"))
      (node (ref "AB19") (pin "AR2") (pinfunction "P$2_AR2") (pintype "bidirectional"))
      (node (ref "AB19") (pin "AU2") (pinfunction "P$2_AU2") (pintype "bidirectional"))
      (node (ref "AB19") (pin "BF2") (pinfunction "P$2_BF2") (pintype "bidirectional"))
      (node (ref "AB19") (pin "BM2") (pinfunction "P$2_BM2") (pintype "bidirectional"))
      (node (ref "B05") (pin "C1") (pinfunction "C_C1") (pintype "input"))
      (node (ref "B05") (pin "F2") (pinfunction "C_F2") (pintype "input"))
      (node (ref "B05") (pin "J1") (pinfunction "C_J1") (pintype "input"))
      (node (ref "B05") (pin "M2") (pinfunction "C_M2") (pintype "input"))
      (node (ref "B05") (pin "P1") (pinfunction "C_P1") (pintype "input"))
      (node (ref "B22") (pin "T2") (pinfunction "C_T2") (pintype "input"))
      (node (ref "D05") (pin "B1") (pinfunction "P$2_B1") (pintype "bidirectional"))
      (node (ref "D05") (pin "D1") (pinfunction "P$2_D1") (pintype "bidirectional"))
      (node (ref "D05") (pin "D2") (pinfunction "P$2_D2") (pintype "bidirectional"))
      (node (ref "D05") (pin "E1") (pinfunction "P$2_E1") (pintype "bidirectional"))
      (node (ref "D05") (pin "H1") (pinfunction "P$2_H1") (pintype "bidirectional"))
      (node (ref "D05") (pin "J1") (pinfunction "P$2_J1") (pintype "bidirectional"))
      (node (ref "D05") (pin "L1") (pinfunction "P$2_L1") (pintype "bidirectional"))
      (node (ref "D05") (pin "M1") (pinfunction "P$2_M1") (pintype "bidirectional"))
      (node (ref "D05") (pin "P1") (pinfunction "P$2_P1") (pintype "bidirectional"))
      (node (ref "D05") (pin "S1") (pinfunction "P$2_S1") (pintype "bidirectional"))
      (node (ref "D06") (pin "K2") (pinfunction "P$2_K2") (pintype "bidirectional"))
      (node (ref "D07") (pin "U1") (pinfunction "IN*_U1") (pintype "input"))
      (node (ref "D11") (pin "T2") (pinfunction "D_T2") (pintype "input"))
      (node (ref "IC5") (pin "12") (pinfunction "D_12") (pintype "input"))
    )
    (net (code "87") (name "IOP_1") (class "Default")
      (node (ref "A02") (pin "K2") (pinfunction "P$2_K2") (pintype "bidirectional"))
      (node (ref "D02") (pin "K2") (pinfunction "P$2_K2") (pintype "bidirectional"))
      (node (ref "IC2") (pin "12") (pinfunction "I0_12") (pintype "input"))
      (node (ref "IC8") (pin "12") (pinfunction "I0_12") (pintype "input"))
    )
    (net (code "88") (name "IOP_2") (class "Default")
      (node (ref "A02") (pin "M2") (pinfunction "P$2_M2") (pintype "bidirectional"))
      (node (ref "D02") (pin "M2") (pinfunction "P$2_M2") (pintype "bidirectional"))
      (node (ref "IC2") (pin "9") (pinfunction "I0_9") (pintype "input"))
      (node (ref "IC8") (pin "9") (pinfunction "I0_9") (pintype "input"))
    )
    (net (code "89") (name "IOP_4") (class "Default")
      (node (ref "A02") (pin "P2") (pinfunction "P$2_P2") (pintype "bidirectional"))
      (node (ref "D02") (pin "P2") (pinfunction "P$2_P2") (pintype "bidirectional"))
      (node (ref "IC2") (pin "4") (pinfunction "I0_4") (pintype "input"))
      (node (ref "IC8") (pin "4") (pinfunction "I0_4") (pintype "input"))
    )
    (net (code "90") (name "I{slash}O_B-BRK") (class "Default")
      (node (ref "A05") (pin "P2") (pinfunction "P$2_P2") (pintype "bidirectional"))
      (node (ref "D05") (pin "P2") (pinfunction "P$2_P2") (pintype "bidirectional"))
      (node (ref "IC9") (pin "13") (pinfunction "I_13") (pintype "input"))
    )
    (net (code "91") (name "I{slash}O_B-RUN") (class "Default")
      (node (ref "A04") (pin "S2") (pinfunction "P$2_S2") (pintype "bidirectional"))
      (node (ref "D04") (pin "S2") (pinfunction "P$2_S2") (pintype "bidirectional"))
      (node (ref "IC9") (pin "11") (pinfunction "I_11") (pintype "input"))
    )
    (net (code "92") (name "I{slash}O_BAC_00") (class "Default")
      (node (ref "A02") (pin "B1") (pinfunction "P$2_B1") (pintype "bidirectional"))
      (node (ref "C03") (pin "A1") (pinfunction "IN1_A1") (pintype "input"))
      (node (ref "D02") (pin "B1") (pinfunction "P$2_B1") (pintype "bidirectional"))
    )
    (net (code "93") (name "I{slash}O_BAC_01") (class "Default")
      (node (ref "A02") (pin "D1") (pinfunction "P$2_D1") (pintype "bidirectional"))
      (node (ref "C03") (pin "D1") (pinfunction "IN2_D1") (pintype "input"))
      (node (ref "D02") (pin "D1") (pinfunction "P$2_D1") (pintype "bidirectional"))
    )
    (net (code "94") (name "I{slash}O_BAC_02") (class "Default")
      (node (ref "A02") (pin "E1") (pinfunction "P$2_E1") (pintype "bidirectional"))
      (node (ref "C03") (pin "F1") (pinfunction "IN3_F1") (pintype "input"))
      (node (ref "D02") (pin "E1") (pinfunction "P$2_E1") (pintype "bidirectional"))
    )
    (net (code "95") (name "I{slash}O_BAC_03") (class "Default")
      (node (ref "A02") (pin "H1") (pinfunction "P$2_H1") (pintype "bidirectional"))
      (node (ref "C03") (pin "J1") (pinfunction "IN4_J1") (pintype "input"))
      (node (ref "D02") (pin "H1") (pinfunction "P$2_H1") (pintype "bidirectional"))
    )
    (net (code "96") (name "I{slash}O_BAC_04") (class "Default")
      (node (ref "A02") (pin "J1") (pinfunction "P$2_J1") (pintype "bidirectional"))
      (node (ref "C03") (pin "L1") (pinfunction "IN5_L1") (pintype "input"))
      (node (ref "D02") (pin "J1") (pinfunction "P$2_J1") (pintype "bidirectional"))
    )
    (net (code "97") (name "I{slash}O_BAC_05") (class "Default")
      (node (ref "A02") (pin "L1") (pinfunction "P$2_L1") (pintype "bidirectional"))
      (node (ref "C03") (pin "N1") (pinfunction "IN6_N1") (pintype "input"))
      (node (ref "D02") (pin "L1") (pinfunction "P$2_L1") (pintype "bidirectional"))
    )
    (net (code "98") (name "I{slash}O_BAC_06") (class "Default")
      (node (ref "A02") (pin "M1") (pinfunction "P$2_M1") (pintype "bidirectional"))
      (node (ref "C03") (pin "R1") (pinfunction "IN7_R1") (pintype "input"))
      (node (ref "D02") (pin "M1") (pinfunction "P$2_M1") (pintype "bidirectional"))
    )
    (net (code "99") (name "I{slash}O_BAC_07") (class "Default")
      (node (ref "A02") (pin "P1") (pinfunction "P$2_P1") (pintype "bidirectional"))
      (node (ref "C03") (pin "V1") (pinfunction "IN8_V1") (pintype "input"))
      (node (ref "D02") (pin "P1") (pinfunction "P$2_P1") (pintype "bidirectional"))
    )
    (net (code "100") (name "I{slash}O_BAC_08") (class "Default")
      (node (ref "A02") (pin "S1") (pinfunction "P$2_S1") (pintype "bidirectional"))
      (node (ref "C03") (pin "E2") (pinfunction "IN9_E2") (pintype "input"))
      (node (ref "D02") (pin "S1") (pinfunction "P$2_S1") (pintype "bidirectional"))
    )
    (net (code "101") (name "I{slash}O_BAC_09") (class "Default")
      (node (ref "A02") (pin "D2") (pinfunction "P$2_D2") (pintype "bidirectional"))
      (node (ref "C03") (pin "H2") (pinfunction "IN10_H2") (pintype "input"))
      (node (ref "D02") (pin "D2") (pinfunction "P$2_D2") (pintype "bidirectional"))
    )
    (net (code "102") (name "I{slash}O_BAC_10") (class "Default")
      (node (ref "A02") (pin "E2") (pinfunction "P$2_E2") (pintype "bidirectional"))
      (node (ref "C03") (pin "K2") (pinfunction "IN11_K2") (pintype "input"))
      (node (ref "D02") (pin "E2") (pinfunction "P$2_E2") (pintype "bidirectional"))
    )
    (net (code "103") (name "I{slash}O_BAC_11") (class "Default")
      (node (ref "A02") (pin "H2") (pinfunction "P$2_H2") (pintype "bidirectional"))
      (node (ref "C03") (pin "M2") (pinfunction "IN12_M2") (pintype "input"))
      (node (ref "D02") (pin "H2") (pinfunction "P$2_H2") (pintype "bidirectional"))
    )
    (net (code "104") (name "I{slash}O_BMB_00") (class "Default")
      (node (ref "A03") (pin "B1") (pinfunction "P$2_B1") (pintype "bidirectional"))
      (node (ref "C02") (pin "A1") (pinfunction "IN1_A1") (pintype "input"))
      (node (ref "D03") (pin "B1") (pinfunction "P$2_B1") (pintype "bidirectional"))
    )
    (net (code "105") (name "I{slash}O_BMB_01") (class "Default")
      (node (ref "A03") (pin "D1") (pinfunction "P$2_D1") (pintype "bidirectional"))
      (node (ref "C02") (pin "D1") (pinfunction "IN2_D1") (pintype "input"))
      (node (ref "D03") (pin "D1") (pinfunction "P$2_D1") (pintype "bidirectional"))
    )
    (net (code "106") (name "I{slash}O_BMB_02") (class "Default")
      (node (ref "A03") (pin "E1") (pinfunction "P$2_E1") (pintype "bidirectional"))
      (node (ref "C02") (pin "F1") (pinfunction "IN3_F1") (pintype "input"))
      (node (ref "D03") (pin "E1") (pinfunction "P$2_E1") (pintype "bidirectional"))
    )
    (net (code "107") (name "I{slash}O_BMB_03") (class "Default")
      (node (ref "A03") (pin "J1") (pinfunction "P$2_J1") (pintype "bidirectional"))
      (node (ref "C02") (pin "J1") (pinfunction "IN4_J1") (pintype "input"))
      (node (ref "D03") (pin "J1") (pinfunction "P$2_J1") (pintype "bidirectional"))
      (node (ref "IC1") (pin "3") (pinfunction "I2_3") (pintype "input"))
      (node (ref "IC6") (pin "3") (pinfunction "I2_3") (pintype "input"))
    )
    (net (code "108") (name "I{slash}O_BMB_04") (class "Default")
      (node (ref "A03") (pin "M1") (pinfunction "P$2_M1") (pintype "bidirectional"))
      (node (ref "C02") (pin "L1") (pinfunction "IN5_L1") (pintype "input"))
      (node (ref "D03") (pin "M1") (pinfunction "P$2_M1") (pintype "bidirectional"))
      (node (ref "IC1") (pin "4") (pinfunction "I3_4") (pintype "input"))
      (node (ref "IC6") (pin "4") (pinfunction "I3_4") (pintype "input"))
    )
    (net (code "109") (name "I{slash}O_BMB_05") (class "Default")
      (node (ref "A03") (pin "S1") (pinfunction "P$2_S1") (pintype "bidirectional"))
      (node (ref "C02") (pin "N1") (pinfunction "IN6_N1") (pintype "input"))
      (node (ref "D03") (pin "S1") (pinfunction "P$2_S1") (pintype "bidirectional"))
      (node (ref "IC1") (pin "5") (pinfunction "I4_5") (pintype "input"))
      (node (ref "IC6") (pin "5") (pinfunction "I4_5") (pintype "input"))
    )
    (net (code "110") (name "I{slash}O_BMB_06") (class "Default")
      (node (ref "A03") (pin "E2") (pinfunction "P$2_E2") (pintype "bidirectional"))
      (node (ref "C02") (pin "R1") (pinfunction "IN7_R1") (pintype "input"))
      (node (ref "D03") (pin "E2") (pinfunction "P$2_E2") (pintype "bidirectional"))
      (node (ref "IC1") (pin "6") (pinfunction "I5_6") (pintype "input"))
      (node (ref "IC6") (pin "6") (pinfunction "I5_6") (pintype "input"))
    )
    (net (code "111") (name "I{slash}O_BMB_07") (class "Default")
      (node (ref "A03") (pin "K2") (pinfunction "P$2_K2") (pintype "bidirectional"))
      (node (ref "C02") (pin "V1") (pinfunction "IN8_V1") (pintype "input"))
      (node (ref "D03") (pin "K2") (pinfunction "P$2_K2") (pintype "bidirectional"))
      (node (ref "IC1") (pin "11") (pinfunction "I6_11") (pintype "input"))
      (node (ref "IC6") (pin "11") (pinfunction "I6_11") (pintype "input"))
    )
    (net (code "112") (name "I{slash}O_BMB_08") (class "Default")
      (node (ref "A03") (pin "P2") (pinfunction "P$2_P2") (pintype "bidirectional"))
      (node (ref "C02") (pin "E2") (pinfunction "IN9_E2") (pintype "input"))
      (node (ref "D03") (pin "P2") (pinfunction "P$2_P2") (pintype "bidirectional"))
      (node (ref "IC6") (pin "12") (pinfunction "I7_12") (pintype "input"))
    )
    (net (code "113") (name "I{slash}O_BMB_09") (class "Default")
      (node (ref "A03") (pin "S2") (pinfunction "P$2_S2") (pintype "bidirectional"))
      (node (ref "C02") (pin "H2") (pinfunction "IN10_H2") (pintype "input"))
      (node (ref "D03") (pin "S2") (pinfunction "P$2_S2") (pintype "bidirectional"))
    )
    (net (code "114") (name "I{slash}O_BMB_10") (class "Default")
      (node (ref "A03") (pin "T2") (pinfunction "P$2_T2") (pintype "bidirectional"))
      (node (ref "C02") (pin "K2") (pinfunction "IN11_K2") (pintype "input"))
      (node (ref "D03") (pin "T2") (pinfunction "P$2_T2") (pintype "bidirectional"))
    )
    (net (code "115") (name "I{slash}O_BMB_11") (class "Default")
      (node (ref "A03") (pin "V2") (pinfunction "P$2_V2") (pintype "bidirectional"))
      (node (ref "C02") (pin "M2") (pinfunction "IN12_M2") (pintype "input"))
      (node (ref "D03") (pin "V2") (pinfunction "P$2_V2") (pintype "bidirectional"))
    )
    (net (code "116") (name "I{slash}O_DATA_IN") (class "Default")
      (node (ref "A05") (pin "M2") (pinfunction "P$2_M2") (pintype "bidirectional"))
      (node (ref "B05") (pin "J2") (pinfunction "E_J2") (pintype "open_collector"))
      (node (ref "D05") (pin "M2") (pinfunction "P$2_M2") (pintype "bidirectional"))
    )
    (net (code "117") (name "I{slash}O_PWR_CLR") (class "Default")
      (node (ref "A02") (pin "V2") (pinfunction "P$2_V2") (pintype "bidirectional"))
      (node (ref "C05") (pin "H1") (pinfunction "IN1_H1") (pintype "input"))
      (node (ref "D02") (pin "V2") (pinfunction "P$2_V2") (pintype "bidirectional"))
    )
    (net (code "118") (name "I{slash}O_TS03") (class "Default")
      (node (ref "A02") (pin "S2") (pinfunction "P$2_S2") (pintype "bidirectional"))
      (node (ref "D02") (pin "S2") (pinfunction "P$2_S2") (pintype "bidirectional"))
      (node (ref "IC3") (pin "9") (pinfunction "I_9") (pintype "input"))
    )
    (net (code "119") (name "I{slash}O_TS04") (class "Default")
      (node (ref "A02") (pin "T2") (pinfunction "P$2_T2") (pintype "bidirectional"))
      (node (ref "D02") (pin "T2") (pinfunction "P$2_T2") (pintype "bidirectional"))
    )
    (net (code "120") (name "I{slash}~{O_0_TO_AC}") (class "Default")
      (node (ref "A04") (pin "P2") (pinfunction "P$2_P2") (pintype "bidirectional"))
      (node (ref "B05") (pin "L1") (pinfunction "E_L1") (pintype "open_collector"))
      (node (ref "D04") (pin "P2") (pinfunction "P$2_P2") (pintype "bidirectional"))
    )
    (net (code "121") (name "I{slash}~{O_1_TO_CA_INH}") (class "Default")
      (node (ref "A06") (pin "M2") (pinfunction "P$2_M2") (pintype "bidirectional"))
      (node (ref "B05") (pin "N2") (pinfunction "D_N2") (pintype "open_collector"))
      (node (ref "D06") (pin "M2") (pinfunction "P$2_M2") (pintype "bidirectional"))
    )
    (net (code "122") (name "I{slash}~{O_ADDR_ACC}") (class "Default")
      (node (ref "A05") (pin "S2") (pinfunction "P$2_S2") (pintype "bidirectional"))
      (node (ref "C02") (pin "U2") (pinfunction "IN15_U2") (pintype "input"))
      (node (ref "D05") (pin "S2") (pinfunction "P$2_S2") (pintype "bidirectional"))
    )
    (net (code "123") (name "I{slash}~{O_BMB_03}") (class "Default")
      (node (ref "A03") (pin "H1") (pinfunction "P$2_H1") (pintype "bidirectional"))
      (node (ref "D03") (pin "H1") (pinfunction "P$2_H1") (pintype "bidirectional"))
    )
    (net (code "124") (name "I{slash}~{O_BMB_04}") (class "Default")
      (node (ref "A03") (pin "L1") (pinfunction "P$2_L1") (pintype "bidirectional"))
      (node (ref "D03") (pin "L1") (pinfunction "P$2_L1") (pintype "bidirectional"))
    )
    (net (code "125") (name "I{slash}~{O_BMB_05}") (class "Default")
      (node (ref "A03") (pin "P1") (pinfunction "P$2_P1") (pintype "bidirectional"))
      (node (ref "D03") (pin "P1") (pinfunction "P$2_P1") (pintype "bidirectional"))
    )
    (net (code "126") (name "I{slash}~{O_BMB_06}") (class "Default")
      (node (ref "A03") (pin "D2") (pinfunction "P$2_D2") (pintype "bidirectional"))
      (node (ref "D03") (pin "D2") (pinfunction "P$2_D2") (pintype "bidirectional"))
    )
    (net (code "127") (name "I{slash}~{O_BMB_07}") (class "Default")
      (node (ref "A03") (pin "H2") (pinfunction "P$2_H2") (pintype "bidirectional"))
      (node (ref "D03") (pin "H2") (pinfunction "P$2_H2") (pintype "bidirectional"))
    )
    (net (code "128") (name "I{slash}~{O_BMB_08}") (class "Default")
      (node (ref "A03") (pin "M2") (pinfunction "P$2_M2") (pintype "bidirectional"))
      (node (ref "D03") (pin "M2") (pinfunction "P$2_M2") (pintype "bidirectional"))
      (node (ref "IC1") (pin "12") (pinfunction "I7_12") (pintype "input"))
    )
    (net (code "129") (name "I{slash}~{O_BRK_RQ}") (class "Default")
      (node (ref "A05") (pin "K2") (pinfunction "P$2_K2") (pintype "bidirectional"))
      (node (ref "B05") (pin "D1") (pinfunction "D_D1") (pintype "open_collector"))
      (node (ref "D05") (pin "K2") (pinfunction "P$2_K2") (pintype "bidirectional"))
    )
    (net (code "130") (name "I{slash}~{O_BWC0}") (class "Default")
      (node (ref "A06") (pin "P2") (pinfunction "P$2_P2") (pintype "bidirectional"))
      (node (ref "D06") (pin "P2") (pinfunction "P$2_P2") (pintype "bidirectional"))
      (node (ref "IC9") (pin "9") (pinfunction "I_9") (pintype "input"))
    )
    (net (code "131") (name "I{slash}~{O_INT_RQ}") (class "Default")
      (node (ref "A04") (pin "M2") (pinfunction "P$2_M2") (pintype "bidirectional"))
      (node (ref "B05") (pin "E1") (pinfunction "E_E1") (pintype "open_collector"))
      (node (ref "D04") (pin "M2") (pinfunction "P$2_M2") (pintype "bidirectional"))
    )
    (net (code "132") (name "I{slash}~{O_SKP_RQ}") (class "Default")
      (node (ref "A04") (pin "K2") (pinfunction "P$2_K2") (pintype "bidirectional"))
      (node (ref "B05") (pin "K1") (pinfunction "D_K1") (pintype "open_collector"))
      (node (ref "D04") (pin "K2") (pinfunction "P$2_K2") (pintype "bidirectional"))
    )
    (net (code "133") (name "LDMF") (class "Default")
      (node (ref "IC4") (pin "11") (pinfunction "CLK_11") (pintype "input"))
      (node (ref "IC4") (pin "3") (pinfunction "CLK_3") (pintype "input"))
      (node (ref "IC5") (pin "3") (pinfunction "CLK_3") (pintype "input"))
      (node (ref "IC9") (pin "2") (pinfunction "O_2") (pintype "output"))
    )
    (net (code "134") (name "LPB_00") (class "Default")
      (node (ref "A25") (pin "T2") (pinfunction "P$2_T2") (pintype "bidirectional"))
      (node (ref "C08") (pin "D1") (pinfunction "IN2B_D1") (pintype "input"))
      (node (ref "D08") (pin "E1") (pinfunction "E1_E1") (pintype "output"))
    )
    (net (code "135") (name "LPB_01") (class "Default")
      (node (ref "A25") (pin "U2") (pinfunction "P$2_U2") (pintype "bidirectional"))
      (node (ref "C08") (pin "K1") (pinfunction "IN2B_K1") (pintype "input"))
      (node (ref "D08") (pin "L1") (pinfunction "L1_L1") (pintype "output"))
    )
    (net (code "136") (name "LPB_02") (class "Default")
      (node (ref "A25") (pin "V2") (pinfunction "P$2_V2") (pintype "bidirectional"))
      (node (ref "C08") (pin "R1") (pinfunction "IN2B_R1") (pintype "input"))
      (node (ref "D08") (pin "S1") (pinfunction "S1_S1") (pintype "output"))
    )
    (net (code "137") (name "LPB_03") (class "Default")
      (node (ref "A26") (pin "A2") (pinfunction "P$2_A2") (pintype "bidirectional"))
      (node (ref "C08") (pin "H2") (pinfunction "IN2B_H2") (pintype "input"))
      (node (ref "D08") (pin "H2") (pinfunction "H2_H2") (pintype "output"))
    )
    (net (code "138") (name "LPB_04") (class "Default")
      (node (ref "A26") (pin "B2") (pinfunction "P$2_B2") (pintype "bidirectional"))
      (node (ref "C08") (pin "N2") (pinfunction "IN2B_N2") (pintype "input"))
      (node (ref "D08") (pin "P2") (pinfunction "P2_P2") (pintype "output"))
    )
    (net (code "139") (name "LPB_05") (class "Default")
      (node (ref "A26") (pin "C2") (pinfunction "P$2_C2") (pintype "bidirectional"))
      (node (ref "C08") (pin "U2") (pinfunction "IN2B_U2") (pintype "input"))
      (node (ref "D08") (pin "V2") (pinfunction "V2_V2") (pintype "output"))
    )
    (net (code "140") (name "LPB_NOT_EQ_1") (class "Default")
      (node (ref "A10") (pin "M1") (pinfunction "IN2_M1") (pintype "input"))
      (node (ref "D10") (pin "V2") (pinfunction "OUT_V2") (pintype "output"))
    )
    (net (code "141") (name "LPB_TO_DTB") (class "Default")
      (node (ref "A11") (pin "T2") (pinfunction "OUT_T2") (pintype "output"))
      (node (ref "C08") (pin "C1") (pinfunction "IN2A_C1") (pintype "input"))
      (node (ref "C08") (pin "F2") (pinfunction "IN2A_F2") (pintype "input"))
      (node (ref "C08") (pin "J1") (pinfunction "IN2A_J1") (pintype "input"))
      (node (ref "C08") (pin "M2") (pinfunction "IN2A_M2") (pintype "input"))
      (node (ref "C08") (pin "P1") (pinfunction "IN2A_P1") (pintype "input"))
      (node (ref "C08") (pin "T2") (pinfunction "IN2A_T2") (pintype "input"))
    )
    (net (code "142") (name "MC00") (class "Default")
      (node (ref "A26") (pin "S1") (pinfunction "P$2_S1") (pintype "bidirectional"))
      (node (ref "B13") (pin "E1") (pinfunction "1_E1") (pintype "output"))
      (node (ref "B13") (pin "E2") (pinfunction "D_E2") (pintype "input"))
      (node (ref "D10") (pin "D2") (pinfunction "IN5_D2") (pintype "input"))
    )
    (net (code "143") (name "MC01") (class "Default")
      (node (ref "A08") (pin "L2") (pinfunction "C_L2") (pintype "input"))
      (node (ref "A26") (pin "T1") (pinfunction "P$2_T1") (pintype "bidirectional"))
      (node (ref "B13") (pin "H2") (pinfunction "1_H2") (pintype "output"))
      (node (ref "B13") (pin "J1") (pinfunction "D_J1") (pintype "input"))
      (node (ref "C11") (pin "E1") (pinfunction "IN2_E1") (pintype "input"))
    )
    (net (code "144") (name "MC02") (class "Default")
      (node (ref "A26") (pin "U1") (pinfunction "P$2_U1") (pintype "bidirectional"))
      (node (ref "B11") (pin "U2") (pinfunction "IN2_U2") (pintype "input"))
      (node (ref "B13") (pin "L1") (pinfunction "1_L1") (pintype "output"))
      (node (ref "D12") (pin "D2") (pinfunction "IN1_D2") (pintype "input"))
      (node (ref "D12") (pin "E2") (pinfunction "IN2_E2") (pintype "input"))
    )
    (net (code "145") (name "MF00") (class "Default")
      (node (ref "A25") (pin "V1") (pinfunction "P$2_V1") (pintype "bidirectional"))
      (node (ref "IC4") (pin "5") (pinfunction "Q_5") (pintype "output"))
    )
    (net (code "146") (name "MF01") (class "Default")
      (node (ref "A26") (pin "A1") (pinfunction "P$2_A1") (pintype "bidirectional"))
      (node (ref "IC4") (pin "9") (pinfunction "Q_9") (pintype "output"))
    )
    (net (code "147") (name "MF02") (class "Default")
      (node (ref "A26") (pin "B1") (pinfunction "P$2_B1") (pintype "bidirectional"))
      (node (ref "IC5") (pin "5") (pinfunction "Q_5") (pintype "output"))
    )
    (net (code "148") (name "MKT") (class "Default")
      (node (ref "A26") (pin "H2") (pinfunction "P$2_H2") (pintype "bidirectional"))
      (node (ref "B12") (pin "S2") (pinfunction "IN2_S2") (pintype "input"))
      (node (ref "B13") (pin "V2") (pinfunction "1_V2") (pintype "output"))
      (node (ref "B15") (pin "L1") (pinfunction "IN1_L1") (pintype "input"))
      (node (ref "C15") (pin "L2") (pinfunction "IN1_L2") (pintype "input"))
    )
    (net (code "149") (name "MKTK") (class "Default")
      (node (ref "A08") (pin "R2") (pinfunction "0_R2") (pintype "output"))
      (node (ref "A25") (pin "P1") (pinfunction "P$2_P1") (pintype "bidirectional"))
    )
    (net (code "150") (name "MK_BLK_END") (class "Default")
      (node (ref "A09") (pin "T2") (pinfunction "IN3_T2") (pintype "input"))
      (node (ref "CD18") (pin "BU1") (pinfunction "BU1_BU1") (pintype "output"))
    )
    (net (code "151") (name "MK_BLK_MK") (class "Default")
      (node (ref "CD18") (pin "AE2") (pinfunction "AE2_AE2") (pintype "output"))
      (node (ref "D10") (pin "A1") (pinfunction "IN1_A1") (pintype "input"))
      (node (ref "D10") (pin "B1") (pinfunction "IN2_B1") (pintype "input"))
    )
    (net (code "152") (name "MK_BLK_START") (class "Default")
      (node (ref "CD18") (pin "AJ2") (pinfunction "AJ2_AJ2") (pintype "output"))
    )
    (net (code "153") (name "MK_BLK_SYNC") (class "Default")
      (node (ref "CD18") (pin "BS2") (pinfunction "BS2_BS2") (pintype "output"))
    )
    (net (code "154") (name "MK_DATA") (class "Default")
      (node (ref "CD18") (pin "BP2") (pinfunction "BP2_BP2") (pintype "output"))
    )
    (net (code "155") (name "MK_DATA_SYNC") (class "Default")
      (node (ref "CD18") (pin "AH1") (pinfunction "AH1_AH1") (pintype "output"))
    )
    (net (code "156") (name "MK_END") (class "Default")
      (node (ref "A08") (pin "C1") (pinfunction "D_C1") (pintype "input"))
      (node (ref "CD18") (pin "AF2") (pinfunction "AF2_AF2") (pintype "output"))
    )
    (net (code "157") (name "MOVE") (class "Default")
      (node (ref "D07") (pin "D2") (pinfunction "O0_D2") (pintype "output"))
    )
    (net (code "158") (name "MR00") (class "Default")
      (node (ref "A25") (pin "D1") (pinfunction "P$2_D1") (pintype "bidirectional"))
      (node (ref "B07") (pin "P2") (pinfunction "P2_P2") (pintype "output"))
      (node (ref "B14") (pin "M2") (pinfunction "D_M2") (pintype "input"))
    )
    (net (code "159") (name "MR01") (class "Default")
      (node (ref "A25") (pin "E1") (pinfunction "P$2_E1") (pintype "bidirectional"))
      (node (ref "C07") (pin "P2") (pinfunction "P2_P2") (pintype "output"))
      (node (ref "C12") (pin "B1") (pinfunction "IN2_B1") (pintype "input"))
    )
    (net (code "160") (name "Net-(A08B-D)") (class "Default")
      (node (ref "A08") (pin "E2") (pinfunction "D_E2") (pintype "input"))
      (node (ref "A09") (pin "L1") (pinfunction "OUT_L1") (pintype "output"))
    )
    (net (code "161") (name "Net-(A08C-S)") (class "Default")
      (node (ref "A08") (pin "K1") (pinfunction "S_K1") (pintype "input"))
      (node (ref "A11") (pin "E1") (pinfunction "OUT_E1") (pintype "output"))
    )
    (net (code "162") (name "Net-(A08F-D)") (class "Default")
      (node (ref "A08") (pin "M2") (pinfunction "D_M2") (pintype "input"))
      (node (ref "A09") (pin "J2") (pinfunction "OUT_J2") (pintype "output"))
    )
    (net (code "163") (name "Net-(A08G-C)") (class "Default")
      (node (ref "A08") (pin "N1") (pinfunction "C_N1") (pintype "input"))
      (node (ref "A11") (pin "D2") (pinfunction "OUT_D2") (pintype "output"))
    )
    (net (code "164") (name "Net-(A08G-D)") (class "Default")
      (node (ref "A08") (pin "P1") (pinfunction "D_P1") (pintype "input"))
      (node (ref "A10") (pin "N1") (pinfunction "OUT_N1") (pintype "output"))
    )
    (net (code "165") (name "Net-(A08H-S)") (class "Default")
      (node (ref "A08") (pin "U2") (pinfunction "S_U2") (pintype "input"))
      (node (ref "B10") (pin "S1") (pinfunction "OUT_S1") (pintype "output"))
    )
    (net (code "166") (name "Net-(A09A-OUT)") (class "Default")
      (node (ref "A09") (pin "E1") (pinfunction "OUT_E1") (pintype "output"))
      (node (ref "A11") (pin "A1") (pinfunction "IN_A1") (pintype "input"))
    )
    (net (code "167") (name "Net-(A09C-IN1)") (class "Default")
      (node (ref "A09") (pin "F1") (pinfunction "IN1_F1") (pintype "input"))
      (node (ref "C10") (pin "P2") (pinfunction "OUT_P2") (pintype "output"))
    )
    (net (code "168") (name "Net-(A09C-IN3)") (class "Default")
      (node (ref "A09") (pin "J1") (pinfunction "IN3_J1") (pintype "input"))
      (node (ref "A10") (pin "K1") (pinfunction "OUT_K1") (pintype "output"))
    )
    (net (code "169") (name "Net-(A09C-IN4)") (class "Default")
      (node (ref "A09") (pin "K1") (pinfunction "IN4_K1") (pintype "input"))
      (node (ref "B21") (pin "U2") (pinfunction "OUT_U2") (pintype "output"))
    )
    (net (code "170") (name "Net-(A09D-OUT)") (class "Default")
      (node (ref "A09") (pin "S1") (pinfunction "OUT_S1") (pintype "output"))
      (node (ref "A10") (pin "U2") (pinfunction "IN2_U2") (pintype "input"))
    )
    (net (code "171") (name "Net-(A09E-IN4)") (class "Default")
      (node (ref "A09") (pin "H2") (pinfunction "IN4_H2") (pintype "input"))
      (node (ref "A11") (pin "B1") (pinfunction "OUT_B1") (pintype "output"))
    )
    (net (code "172") (name "Net-(A09F-OUT)") (class "Default")
      (node (ref "A09") (pin "P2") (pinfunction "OUT_P2") (pintype "output"))
      (node (ref "A11") (pin "F1") (pinfunction "IN_F1") (pintype "input"))
    )
    (net (code "173") (name "Net-(A09G-IN4)") (class "Default")
      (node (ref "A09") (pin "U2") (pinfunction "IN4_U2") (pintype "input"))
      (node (ref "C17") (pin "R2") (pinfunction "OUT_R2") (pintype "output"))
    )
    (net (code "174") (name "Net-(A09G-OUT)") (class "Default")
      (node (ref "A09") (pin "V2") (pinfunction "OUT_V2") (pintype "output"))
      (node (ref "A11") (pin "S2") (pinfunction "IN_S2") (pintype "input"))
    )
    (net (code "175") (name "Net-(A10A-IN2)") (class "Default")
      (node (ref "A10") (pin "B1") (pinfunction "IN2_B1") (pintype "input"))
      (node (ref "A10") (pin "F1") (pinfunction "OUT_F1") (pintype "output"))
      (node (ref "B15") (pin "P2") (pinfunction "IN1_P2") (pintype "input"))
    )
    (net (code "176") (name "Net-(A10A-OUT)") (class "Default")
      (node (ref "A10") (pin "C1") (pinfunction "OUT_C1") (pintype "output"))
      (node (ref "A10") (pin "D1") (pinfunction "IN1_D1") (pintype "input"))
    )
    (net (code "177") (name "Net-(A10B-IN1)") (class "Default")
      (node (ref "A10") (pin "S2") (pinfunction "OUT_S2") (pintype "output"))
      (node (ref "A10") (pin "T2") (pinfunction "IN1_T2") (pintype "input"))
    )
    (net (code "178") (name "Net-(A10B-OUT)") (class "Default")
      (node (ref "A10") (pin "V2") (pinfunction "OUT_V2") (pintype "output"))
      (node (ref "A11") (pin "D1") (pinfunction "IN_D1") (pintype "input"))
    )
    (net (code "179") (name "Net-(A10H-OUT)") (class "Default")
      (node (ref "A10") (pin "F2") (pinfunction "OUT_F2") (pintype "output"))
      (node (ref "A10") (pin "J2") (pinfunction "IN2_J2") (pintype "input"))
    )
    (net (code "180") (name "Net-(A10M-OUT)") (class "Default")
      (node (ref "A10") (pin "S1") (pinfunction "OUT_S1") (pintype "output"))
      (node (ref "A11") (pin "C1") (pinfunction "IN_C1") (pintype "input"))
    )
    (net (code "181") (name "Net-(A11D-IN)") (class "Default")
      (node (ref "A11") (pin "R1") (pinfunction "IN_R1") (pintype "input"))
      (node (ref "B11") (pin "S2") (pinfunction "OUT_S2") (pintype "output"))
    )
    (net (code "182") (name "Net-(A11E-IN)") (class "Default")
      (node (ref "A11") (pin "P2") (pinfunction "IN_P2") (pintype "input"))
      (node (ref "A14") (pin "F2") (pinfunction "F2_F2") (pintype "output"))
    )
    (net (code "183") (name "Net-(A11F-IN)") (class "Default")
      (node (ref "A11") (pin "V1") (pinfunction "IN_V1") (pintype "input"))
      (node (ref "B08") (pin "V2") (pinfunction "OUT_V2") (pintype "output"))
    )
    (net (code "184") (name "Net-(A11H-IN)") (class "Default")
      (node (ref "A11") (pin "U2") (pinfunction "IN_U2") (pintype "input"))
      (node (ref "A14") (pin "T2") (pinfunction "F2_T2") (pintype "output"))
    )
    (net (code "185") (name "Net-(A11K-OUT)") (class "Default")
      (node (ref "A11") (pin "H1") (pinfunction "OUT_H1") (pintype "output"))
      (node (ref "A12") (pin "B1") (pinfunction "IN2_B1") (pintype "input"))
      (node (ref "A12") (pin "D1") (pinfunction "IN1_D1") (pintype "input"))
    )
    (net (code "186") (name "Net-(A12B-IN1)") (class "Default")
      (node (ref "A12") (pin "N2") (pinfunction "OUT_N2") (pintype "output"))
      (node (ref "A12") (pin "T2") (pinfunction "IN1_T2") (pintype "input"))
    )
    (net (code "187") (name "Net-(A12B-IN2)") (class "Default")
      (node (ref "A12") (pin "S2") (pinfunction "OUT_S2") (pintype "output"))
      (node (ref "A12") (pin "U2") (pinfunction "IN2_U2") (pintype "input"))
    )
    (net (code "188") (name "Net-(A12H-OUT)") (class "Default")
      (node (ref "A12") (pin "F2") (pinfunction "OUT_F2") (pintype "output"))
      (node (ref "B10") (pin "A1") (pinfunction "IN1_A1") (pintype "input"))
      (node (ref "B10") (pin "B1") (pinfunction "IN2_B1") (pintype "input"))
    )
    (net (code "189") (name "Net-(A12I-IN2)") (class "Default")
      (node (ref "A12") (pin "J1") (pinfunction "IN2_J1") (pintype "input"))
      (node (ref "A12") (pin "N1") (pinfunction "OUT_N1") (pintype "output"))
      (node (ref "A12") (pin "P1") (pinfunction "IN1_P1") (pintype "input"))
    )
    (net (code "190") (name "Net-(A12J-OUT)") (class "Default")
      (node (ref "A12") (pin "K2") (pinfunction "OUT_K2") (pintype "output"))
      (node (ref "B10") (pin "C1") (pinfunction "IN3_C1") (pintype "input"))
      (node (ref "B10") (pin "D1") (pinfunction "IN4_D1") (pintype "input"))
    )
    (net (code "191") (name "Net-(A14-PadD2)") (class "Default")
      (node (ref "A14") (pin "D2") (pinfunction "D2_D2") (pintype "passive"))
      (node (ref "A14") (pin "E2") (pinfunction "E2_E2") (pintype "passive"))
    )
    (net (code "192") (name "Net-(A14-PadH1)") (class "Default")
      (node (ref "A14") (pin "H1") (pinfunction "H1_H1") (pintype "passive"))
      (node (ref "A14") (pin "L2") (pinfunction "L2_L2") (pintype "passive"))
    )
    (net (code "193") (name "Net-(A14B-D2)") (class "Default")
      (node (ref "A14") (pin "R2") (pinfunction "E2_R2") (pintype "passive"))
      (node (ref "A14") (pin "V2") (pinfunction "D2_V2") (pintype "passive"))
    )
    (net (code "194") (name "Net-(A14B-H1)") (class "Default")
      (node (ref "A14") (pin "S1") (pinfunction "H1_S1") (pintype "passive"))
      (node (ref "A14") (pin "S2") (pinfunction "L2_S2") (pintype "passive"))
    )
    (net (code "195") (name "Net-(A14B-H2)") (class "Default")
      (node (ref "A14") (pin "M2") (pinfunction "H2_M2") (pintype "input"))
      (node (ref "A14") (pin "N2") (pinfunction "J2_N2") (pintype "input"))
      (node (ref "A14") (pin "P2") (pinfunction "K2_P2") (pintype "input"))
      (node (ref "B15") (pin "F2") (pinfunction "OUT_F2") (pintype "output"))
    )
    (net (code "196") (name "Net-(A15A-IN3)") (class "Default")
      (node (ref "A15") (pin "C1") (pinfunction "IN3_C1") (pintype "input"))
      (node (ref "A15") (pin "D1") (pinfunction "IN4_D1") (pintype "input"))
      (node (ref "C17") (pin "D2") (pinfunction "OUT_D2") (pintype "output"))
    )
    (net (code "197") (name "Net-(A15D-IN1)") (class "Default")
      (node (ref "A15") (pin "D2") (pinfunction "IN1_D2") (pintype "input"))
      (node (ref "A15") (pin "E2") (pinfunction "IN2_E2") (pintype "input"))
      (node (ref "C17") (pin "F2") (pinfunction "OUT_F2") (pintype "output"))
    )
    (net (code "198") (name "Net-(A16-PadD2)") (class "Default")
      (node (ref "A16") (pin "D2") (pinfunction "D2_D2") (pintype "passive"))
      (node (ref "A16") (pin "E2") (pinfunction "E2_E2") (pintype "passive"))
    )
    (net (code "199") (name "Net-(A16B-D2)") (class "Default")
      (node (ref "A16") (pin "R2") (pinfunction "E2_R2") (pintype "passive"))
      (node (ref "A16") (pin "S2") (pinfunction "D2_S2") (pintype "passive"))
    )
    (net (code "200") (name "Net-(AB19A-P$2)") (class "Default")
      (node (ref "A18") (pin "D2") (pinfunction "D2_D2") (pintype "input"))
      (node (ref "A18") (pin "J2") (pinfunction "J2_J2") (pintype "output"))
      (node (ref "AB19") (pin "AF2") (pinfunction "P$2_AF2") (pintype "bidirectional"))
    )
    (net (code "201") (name "Net-(AB19C-P$2)") (class "Default")
      (node (ref "AB19") (pin "BH2") (pinfunction "P$2_BH2") (pintype "bidirectional"))
      (node (ref "B20") (pin "D2") (pinfunction "D2_D2") (pintype "input"))
      (node (ref "B20") (pin "J2") (pinfunction "J2_J2") (pintype "output"))
    )
    (net (code "202") (name "Net-(AB19D-P$2)") (class "Default")
      (node (ref "AB19") (pin "BJ2") (pinfunction "P$2_BJ2") (pintype "bidirectional"))
      (node (ref "B20") (pin "E2") (pinfunction "E2_E2") (pintype "input"))
      (node (ref "B20") (pin "K2") (pinfunction "K2_K2") (pintype "output"))
    )
    (net (code "203") (name "Net-(AB19F-P$2)") (class "Default")
      (node (ref "A21") (pin "D2") (pinfunction "D2_D2") (pintype "input"))
      (node (ref "A21") (pin "J2") (pinfunction "J2_J2") (pintype "output"))
      (node (ref "AB19") (pin "BN2") (pinfunction "P$2_BN2") (pintype "bidirectional"))
    )
    (net (code "204") (name "Net-(AB19G-P$2)") (class "Default")
      (node (ref "A21") (pin "E2") (pinfunction "E2_E2") (pintype "input"))
      (node (ref "A21") (pin "K2") (pinfunction "K2_K2") (pintype "output"))
      (node (ref "AB19") (pin "BP2") (pinfunction "P$2_BP2") (pintype "bidirectional"))
    )
    (net (code "205") (name "Net-(AB19L-P$2)") (class "Default")
      (node (ref "A18") (pin "E2") (pinfunction "E2_E2") (pintype "input"))
      (node (ref "A18") (pin "K2") (pinfunction "K2_K2") (pintype "output"))
      (node (ref "AB19") (pin "AH2") (pinfunction "P$2_AH2") (pintype "bidirectional"))
    )
    (net (code "206") (name "Net-(AB19P-P$2)") (class "Default")
      (node (ref "AB19") (pin "AN2") (pinfunction "P$2_AN2") (pintype "bidirectional"))
      (node (ref "B18") (pin "D2") (pinfunction "D2_D2") (pintype "input"))
      (node (ref "B18") (pin "J2") (pinfunction "J2_J2") (pintype "output"))
    )
    (net (code "207") (name "Net-(AB19Q-P$2)") (class "Default")
      (node (ref "AB19") (pin "AP2") (pinfunction "P$2_AP2") (pintype "bidirectional"))
      (node (ref "B18") (pin "E2") (pinfunction "E2_E2") (pintype "input"))
      (node (ref "B18") (pin "K2") (pinfunction "K2_K2") (pintype "output"))
    )
    (net (code "208") (name "Net-(AB19T-P$2)") (class "Default")
      (node (ref "A20") (pin "D2") (pinfunction "D2_D2") (pintype "input"))
      (node (ref "A20") (pin "J2") (pinfunction "J2_J2") (pintype "output"))
      (node (ref "AB19") (pin "AV2") (pinfunction "P$2_AV2") (pintype "bidirectional"))
    )
    (net (code "209") (name "Net-(AB19U-P$2)") (class "Default")
      (node (ref "A20") (pin "E2") (pinfunction "E2_E2") (pintype "input"))
      (node (ref "A20") (pin "K2") (pinfunction "K2_K2") (pintype "output"))
      (node (ref "AB19") (pin "BD2") (pinfunction "P$2_BD2") (pintype "bidirectional"))
    )
    (net (code "210") (name "Net-(B06G-IN)") (class "Default")
      (node (ref "B06") (pin "S2") (pinfunction "IN_S2") (pintype "input"))
      (node (ref "B08") (pin "S2") (pinfunction "OUT_S2") (pintype "output"))
    )
    (net (code "211") (name "Net-(B08A-OUT)") (class "Default")
      (node (ref "B08") (pin "C1") (pinfunction "OUT_C1") (pintype "output"))
      (node (ref "B09") (pin "D1") (pinfunction "S_D1") (pintype "input"))
    )
    (net (code "212") (name "Net-(B08G-OUT)") (class "Default")
      (node (ref "B08") (pin "F1") (pinfunction "OUT_F1") (pintype "output"))
      (node (ref "B09") (pin "U2") (pinfunction "S_U2") (pintype "input"))
    )
    (net (code "213") (name "Net-(B08H-OUT)") (class "Default")
      (node (ref "B08") (pin "F2") (pinfunction "OUT_F2") (pintype "output"))
      (node (ref "B09") (pin "K1") (pinfunction "S_K1") (pintype "input"))
    )
    (net (code "214") (name "Net-(B08I-OUT)") (class "Default")
      (node (ref "B08") (pin "K1") (pinfunction "OUT_K1") (pintype "output"))
      (node (ref "B09") (pin "F2") (pinfunction "S_F2") (pintype "input"))
    )
    (net (code "215") (name "Net-(B08K-OUT)") (class "Default")
      (node (ref "B08") (pin "N1") (pinfunction "OUT_N1") (pintype "output"))
      (node (ref "B09") (pin "N2") (pinfunction "S_N2") (pintype "input"))
    )
    (net (code "216") (name "Net-(B08M-OUT)") (class "Default")
      (node (ref "B08") (pin "S1") (pinfunction "OUT_S1") (pintype "output"))
      (node (ref "B09") (pin "R1") (pinfunction "S_R1") (pintype "input"))
    )
    (net (code "217") (name "Net-(B10B-IN1)") (class "Default")
      (node (ref "B10") (pin "F1") (pinfunction "IN1_F1") (pintype "input"))
      (node (ref "B11") (pin "J1") (pinfunction "OUT_J1") (pintype "output"))
    )
    (net (code "218") (name "Net-(B10B-IN4)") (class "Default")
      (node (ref "B10") (pin "K1") (pinfunction "IN4_K1") (pintype "input"))
      (node (ref "C17") (pin "H1") (pinfunction "OUT_H1") (pintype "output"))
    )
    (net (code "219") (name "Net-(B11A-OUT)") (class "Default")
      (node (ref "B11") (pin "D1") (pinfunction "OUT_D1") (pintype "output"))
      (node (ref "B11") (pin "F2") (pinfunction "IN3_F2") (pintype "input"))
    )
    (net (code "220") (name "Net-(B11C-IN1)") (class "Default")
      (node (ref "B11") (pin "E1") (pinfunction "IN1_E1") (pintype "input"))
      (node (ref "B11") (pin "U1") (pinfunction "OUT_U1") (pintype "output"))
    )
    (net (code "221") (name "Net-(B11C-IN3)") (class "Default")
      (node (ref "B11") (pin "H1") (pinfunction "IN3_H1") (pintype "input"))
      (node (ref "B11") (pin "N1") (pinfunction "OUT_N1") (pintype "output"))
    )
    (net (code "222") (name "Net-(B11F-IN1)") (class "Default")
      (node (ref "B11") (pin "D2") (pinfunction "IN1_D2") (pintype "input"))
      (node (ref "B12") (pin "E1") (pinfunction "OUT_E1") (pintype "output"))
    )
    (net (code "223") (name "Net-(B11F-IN2)") (class "Default")
      (node (ref "B11") (pin "E2") (pinfunction "IN2_E2") (pintype "input"))
      (node (ref "B12") (pin "L1") (pinfunction "OUT_L1") (pintype "output"))
    )
    (net (code "224") (name "Net-(B11F-OUT)") (class "Default")
      (node (ref "B11") (pin "H2") (pinfunction "OUT_H2") (pintype "output"))
      (node (ref "C13") (pin "C1") (pinfunction "IN_C1") (pintype "input"))
    )
    (net (code "225") (name "Net-(B11G-IN3)") (class "Default")
      (node (ref "B11") (pin "L2") (pinfunction "IN3_L2") (pintype "input"))
      (node (ref "B15") (pin "S2") (pinfunction "OUT_S2") (pintype "output"))
    )
    (net (code "226") (name "Net-(B11I-OUT)") (class "Default")
      (node (ref "B11") (pin "V1") (pinfunction "OUT_V1") (pintype "output"))
      (node (ref "C17") (pin "J1") (pinfunction "IN_J1") (pintype "input"))
    )
    (net (code "227") (name "Net-(B12D-IN1)") (class "Default")
      (node (ref "B12") (pin "M1") (pinfunction "IN1_M1") (pintype "input"))
      (node (ref "C11") (pin "C1") (pinfunction "OUT_C1") (pintype "output"))
    )
    (net (code "228") (name "Net-(B12D-IN4)") (class "Default")
      (node (ref "B12") (pin "R1") (pinfunction "IN4_R1") (pintype "input"))
      (node (ref "C11") (pin "F1") (pinfunction "OUT_F1") (pintype "output"))
    )
    (net (code "229") (name "Net-(B12D-OUT)") (class "Default")
      (node (ref "B12") (pin "S1") (pinfunction "OUT_S1") (pintype "output"))
      (node (ref "C11") (pin "P1") (pinfunction "IN1_P1") (pintype "input"))
    )
    (net (code "230") (name "Net-(B12E-OUT)") (class "Default")
      (node (ref "B12") (pin "J2") (pinfunction "OUT_J2") (pintype "output"))
      (node (ref "B12") (pin "N2") (pinfunction "IN4_N2") (pintype "input"))
    )
    (net (code "231") (name "Net-(B12F-IN1)") (class "Default")
      (node (ref "B12") (pin "K2") (pinfunction "IN1_K2") (pintype "input"))
      (node (ref "C12") (pin "N1") (pinfunction "OUT_N1") (pintype "output"))
    )
    (net (code "232") (name "Net-(B12F-IN2)") (class "Default")
      (node (ref "B12") (pin "L2") (pinfunction "IN2_L2") (pintype "input"))
      (node (ref "C12") (pin "U1") (pinfunction "OUT_U1") (pintype "output"))
    )
    (net (code "233") (name "Net-(B12F-IN3)") (class "Default")
      (node (ref "B12") (pin "M2") (pinfunction "IN3_M2") (pintype "input"))
      (node (ref "C12") (pin "V1") (pinfunction "OUT_V1") (pintype "output"))
    )
    (net (code "234") (name "Net-(B12G-IN4)") (class "Default")
      (node (ref "B12") (pin "U2") (pinfunction "IN4_U2") (pintype "input"))
      (node (ref "C11") (pin "N1") (pinfunction "OUT_N1") (pintype "output"))
    )
    (net (code "235") (name "Net-(B12G-OUT)") (class "Default")
      (node (ref "B12") (pin "V2") (pinfunction "OUT_V2") (pintype "output"))
      (node (ref "C12") (pin "F1") (pinfunction "IN2_F1") (pintype "input"))
    )
    (net (code "236") (name "Net-(B13F-S)") (class "Default")
      (node (ref "B13") (pin "N2") (pinfunction "S_N2") (pintype "input"))
      (node (ref "B15") (pin "K1") (pinfunction "OUT_K1") (pintype "output"))
    )
    (net (code "237") (name "Net-(B14G-C)") (class "Default")
      (node (ref "B14") (pin "N1") (pinfunction "C_N1") (pintype "input"))
      (node (ref "B14") (pin "S2") (pinfunction "C_S2") (pintype "input"))
      (node (ref "D15") (pin "D2") (pinfunction "D2_D2") (pintype "output"))
    )
    (net (code "238") (name "Net-(B15G-OUT)") (class "Default")
      (node (ref "A14") (pin "H2") (pinfunction "H2_H2") (pintype "input"))
      (node (ref "A14") (pin "J2") (pinfunction "J2_J2") (pintype "input"))
      (node (ref "A14") (pin "K2") (pinfunction "K2_K2") (pintype "input"))
      (node (ref "B15") (pin "F1") (pinfunction "OUT_F1") (pintype "output"))
    )
    (net (code "239") (name "Net-(B15K-OUT)") (class "Default")
      (node (ref "B15") (pin "N1") (pinfunction "OUT_N1") (pintype "output"))
      (node (ref "C17") (pin "F1") (pinfunction "IN_F1") (pintype "input"))
    )
    (net (code "240") (name "Net-(B15M-OUT)") (class "Default")
      (node (ref "B15") (pin "S1") (pinfunction "OUT_S1") (pintype "output"))
      (node (ref "C17") (pin "L1") (pinfunction "IN_L1") (pintype "input"))
    )
    (net (code "241") (name "Net-(B16-PadD2)") (class "Default")
      (node (ref "B16") (pin "D2") (pinfunction "D2_D2") (pintype "passive"))
      (node (ref "B16") (pin "E2") (pinfunction "E2_E2") (pintype "passive"))
    )
    (net (code "242") (name "Net-(B16B-D2)") (class "Default")
      (node (ref "B16") (pin "R2") (pinfunction "E2_R2") (pintype "passive"))
      (node (ref "B16") (pin "S2") (pinfunction "D2_S2") (pintype "passive"))
    )
    (net (code "243") (name "Net-(C08A-OUT)") (class "Default")
      (node (ref "C08") (pin "E1") (pinfunction "OUT_E1") (pintype "output"))
      (node (ref "C09") (pin "D1") (pinfunction "S_D1") (pintype "input"))
    )
    (net (code "244") (name "Net-(C08C-OUT)") (class "Default")
      (node (ref "C08") (pin "L1") (pinfunction "OUT_L1") (pintype "output"))
      (node (ref "C09") (pin "F2") (pinfunction "S_F2") (pintype "input"))
    )
    (net (code "245") (name "Net-(C08D-OUT)") (class "Default")
      (node (ref "C08") (pin "S1") (pinfunction "OUT_S1") (pintype "output"))
      (node (ref "C09") (pin "K1") (pinfunction "S_K1") (pintype "input"))
    )
    (net (code "246") (name "Net-(C08E-OUT)") (class "Default")
      (node (ref "C08") (pin "J2") (pinfunction "OUT_J2") (pintype "output"))
      (node (ref "C09") (pin "N2") (pinfunction "S_N2") (pintype "input"))
    )
    (net (code "247") (name "Net-(C08F-OUT)") (class "Default")
      (node (ref "C08") (pin "P2") (pinfunction "OUT_P2") (pintype "output"))
      (node (ref "C09") (pin "R1") (pinfunction "S_R1") (pintype "input"))
    )
    (net (code "248") (name "Net-(C08G-OUT)") (class "Default")
      (node (ref "C08") (pin "V2") (pinfunction "OUT_V2") (pintype "output"))
      (node (ref "C09") (pin "U2") (pinfunction "S_U2") (pintype "input"))
    )
    (net (code "249") (name "Net-(C10A-OUT)") (class "Default")
      (node (ref "C10") (pin "E1") (pinfunction "OUT_E1") (pintype "output"))
      (node (ref "C14") (pin "C1") (pinfunction "D_C1") (pintype "input"))
    )
    (net (code "250") (name "Net-(C10C-OUT)") (class "Default")
      (node (ref "C10") (pin "L1") (pinfunction "OUT_L1") (pintype "output"))
      (node (ref "C14") (pin "E2") (pinfunction "D_E2") (pintype "input"))
    )
    (net (code "251") (name "Net-(C10D-OUT)") (class "Default")
      (node (ref "C10") (pin "S1") (pinfunction "OUT_S1") (pintype "output"))
      (node (ref "C14") (pin "J1") (pinfunction "D_J1") (pintype "input"))
    )
    (net (code "252") (name "Net-(C10E-OUT)") (class "Default")
      (node (ref "C10") (pin "J2") (pinfunction "OUT_J2") (pintype "output"))
      (node (ref "C17") (pin "M2") (pinfunction "IN_M2") (pintype "input"))
    )
    (net (code "253") (name "Net-(C10G-OUT)") (class "Default")
      (node (ref "C10") (pin "V2") (pinfunction "OUT_V2") (pintype "output"))
      (node (ref "C17") (pin "V1") (pinfunction "IN_V1") (pintype "input"))
    )
    (net (code "254") (name "Net-(C11B-IN1)") (class "Default")
      (node (ref "C11") (pin "S2") (pinfunction "OUT_S2") (pintype "output"))
      (node (ref "C11") (pin "T2") (pinfunction "IN1_T2") (pintype "input"))
    )
    (net (code "255") (name "Net-(C11B-OUT)") (class "Default")
      (node (ref "C11") (pin "V2") (pinfunction "OUT_V2") (pintype "output"))
      (node (ref "C13") (pin "V1") (pinfunction "IN_V1") (pintype "input"))
    )
    (net (code "256") (name "Net-(C11H-OUT)") (class "Default")
      (node (ref "C11") (pin "F2") (pinfunction "OUT_F2") (pintype "output"))
      (node (ref "C12") (pin "H1") (pinfunction "IN3_H1") (pintype "input"))
    )
    (net (code "257") (name "Net-(C11I-OUT)") (class "Default")
      (node (ref "C11") (pin "K1") (pinfunction "OUT_K1") (pintype "output"))
      (node (ref "C11") (pin "L1") (pinfunction "IN1_L1") (pintype "input"))
    )
    (net (code "258") (name "Net-(C11J-OUT)") (class "Default")
      (node (ref "C11") (pin "K2") (pinfunction "OUT_K2") (pintype "output"))
      (node (ref "D12") (pin "K2") (pinfunction "IN1_K2") (pintype "input"))
      (node (ref "D12") (pin "L2") (pinfunction "IN2_L2") (pintype "input"))
    )
    (net (code "259") (name "Net-(C11M-OUT)") (class "Default")
      (node (ref "C11") (pin "S1") (pinfunction "OUT_S1") (pintype "output"))
      (node (ref "C12") (pin "E1") (pinfunction "IN1_E1") (pintype "input"))
    )
    (net (code "260") (name "Net-(C12A-OUT)") (class "Default")
      (node (ref "C12") (pin "D1") (pinfunction "OUT_D1") (pintype "output"))
      (node (ref "C13") (pin "M2") (pinfunction "IN_M2") (pintype "input"))
    )
    (net (code "261") (name "Net-(C12F-OUT)") (class "Default")
      (node (ref "C12") (pin "H2") (pinfunction "OUT_H2") (pintype "output"))
      (node (ref "D12") (pin "M2") (pinfunction "IN3_M2") (pintype "input"))
      (node (ref "D12") (pin "N2") (pinfunction "IN4_N2") (pintype "input"))
    )
    (net (code "262") (name "Net-(C12H-OUT)") (class "Default")
      (node (ref "C12") (pin "S2") (pinfunction "OUT_S2") (pintype "output"))
      (node (ref "C15") (pin "P1") (pinfunction "IN1_P1") (pintype "input"))
    )
    (net (code "263") (name "Net-(C13C-OUT)") (class "Default")
      (node (ref "C13") (pin "N2") (pinfunction "OUT_N2") (pintype "output"))
      (node (ref "C14") (pin "N2") (pinfunction "S_N2") (pintype "input"))
    )
    (net (code "264") (name "Net-(C13E-IN)") (class "Default")
      (node (ref "C13") (pin "P2") (pinfunction "IN_P2") (pintype "input"))
      (node (ref "C15") (pin "F2") (pinfunction "OUT_F2") (pintype "output"))
    )
    (net (code "265") (name "Net-(C13G-IN)") (class "Default")
      (node (ref "C13") (pin "S2") (pinfunction "IN_S2") (pintype "input"))
      (node (ref "C15") (pin "K2") (pinfunction "OUT_K2") (pintype "output"))
    )
    (net (code "266") (name "Net-(C13I-OUT)") (class "Default")
      (node (ref "C13") (pin "D2") (pinfunction "OUT_D2") (pintype "output"))
      (node (ref "C14") (pin "P1") (pinfunction "D_P1") (pintype "input"))
    )
    (net (code "267") (name "Net-(C14F-C)") (class "Default")
      (node (ref "C14") (pin "L2") (pinfunction "C_L2") (pintype "input"))
      (node (ref "C15") (pin "S2") (pinfunction "OUT_S2") (pintype "output"))
    )
    (net (code "268") (name "Net-(C15A-OUT)") (class "Default")
      (node (ref "C15") (pin "C1") (pinfunction "OUT_C1") (pintype "output"))
      (node (ref "C15") (pin "H1") (pinfunction "IN1_H1") (pintype "input"))
    )
    (net (code "269") (name "Net-(C15G-OUT)") (class "Default")
      (node (ref "C15") (pin "F1") (pinfunction "OUT_F1") (pintype "output"))
      (node (ref "C15") (pin "J1") (pinfunction "IN2_J1") (pintype "input"))
    )
    (net (code "270") (name "Net-(C15K-OUT)") (class "Default")
      (node (ref "C15") (pin "N1") (pinfunction "OUT_N1") (pintype "output"))
      (node (ref "C15") (pin "R1") (pinfunction "IN2_R1") (pintype "input"))
    )
    (net (code "271") (name "Net-(C15L-OUT)") (class "Default")
      (node (ref "C15") (pin "N2") (pinfunction "OUT_N2") (pintype "output"))
      (node (ref "C17") (pin "P2") (pinfunction "IN_P2") (pintype "input"))
    )
    (net (code "272") (name "Net-(C16C-OUT)") (class "Default")
      (node (ref "B16") (pin "K2") (pinfunction "K2_K2") (pintype "input"))
      (node (ref "C16") (pin "S1") (pinfunction "OUT_S1") (pintype "output"))
    )
    (net (code "273") (name "Net-(C16E-IN1)") (class "Default")
      (node (ref "C16") (pin "K2") (pinfunction "IN1_K2") (pintype "input"))
      (node (ref "C16") (pin "L2") (pinfunction "IN2_L2") (pintype "input"))
      (node (ref "C16") (pin "M2") (pinfunction "IN3_M2") (pintype "input"))
      (node (ref "C16") (pin "N2") (pinfunction "IN4_N2") (pintype "input"))
      (node (ref "C17") (pin "B1") (pinfunction "OUT_B1") (pintype "output"))
    )
    (net (code "274") (name "Net-(C16F-OUT)") (class "Default")
      (node (ref "A16") (pin "H2") (pinfunction "H2_H2") (pintype "input"))
      (node (ref "C16") (pin "V2") (pinfunction "OUT_V2") (pintype "output"))
    )
    (net (code "275") (name "Net-(C17C-OUT)") (class "Default")
      (node (ref "C17") (pin "N2") (pinfunction "OUT_N2") (pintype "output"))
      (node (ref "D08") (pin "B1") (pinfunction "B1_B1") (pintype "input"))
      (node (ref "D08") (pin "H1") (pinfunction "H1_H1") (pintype "input"))
      (node (ref "D08") (pin "N1") (pinfunction "N1_N1") (pintype "input"))
    )
    (net (code "276") (name "Net-(C17D-IN)") (class "Default")
      (node (ref "C17") (pin "R1") (pinfunction "IN_R1") (pintype "input"))
      (node (ref "D17") (pin "F2") (pinfunction "F2_F2") (pintype "output"))
    )
    (net (code "277") (name "Net-(C17F-OUT)") (class "Default")
      (node (ref "C17") (pin "U1") (pinfunction "OUT_U1") (pintype "output"))
      (node (ref "D08") (pin "D2") (pinfunction "D2_D2") (pintype "input"))
      (node (ref "D08") (pin "L2") (pinfunction "L2_L2") (pintype "input"))
      (node (ref "D08") (pin "S2") (pinfunction "S2_S2") (pintype "input"))
    )
    (net (code "278") (name "Net-(C17G-IN)") (class "Default")
      (node (ref "C17") (pin "S2") (pinfunction "IN_S2") (pintype "input"))
      (node (ref "D16") (pin "T2") (pinfunction "F2_T2") (pintype "output"))
    )
    (net (code "279") (name "Net-(C17I-IN)") (class "Default")
      (node (ref "A16") (pin "F2") (pinfunction "F2_F2") (pintype "output"))
      (node (ref "C17") (pin "C1") (pinfunction "IN_C1") (pintype "input"))
    )
    (net (code "280") (name "Net-(C17L-IN)") (class "Default")
      (node (ref "B16") (pin "F2") (pinfunction "F2_F2") (pintype "output"))
      (node (ref "C17") (pin "E2") (pinfunction "IN_E2") (pintype "input"))
    )
    (net (code "281") (name "Net-(D09A-OUT)") (class "Default")
      (node (ref "D08") (pin "C1") (pinfunction "C1_C1") (pintype "input"))
      (node (ref "D08") (pin "D1") (pinfunction "D1_D1") (pintype "input"))
      (node (ref "D09") (pin "E1") (pinfunction "OUT_E1") (pintype "output"))
    )
    (net (code "282") (name "Net-(D09C-OUT)") (class "Default")
      (node (ref "D08") (pin "J1") (pinfunction "J1_J1") (pintype "input"))
      (node (ref "D08") (pin "K1") (pinfunction "K1_K1") (pintype "input"))
      (node (ref "D09") (pin "L1") (pinfunction "OUT_L1") (pintype "output"))
    )
    (net (code "283") (name "Net-(D09D-OUT)") (class "Default")
      (node (ref "D08") (pin "P1") (pinfunction "P1_P1") (pintype "input"))
      (node (ref "D08") (pin "R1") (pinfunction "R1_R1") (pintype "input"))
      (node (ref "D09") (pin "S1") (pinfunction "OUT_S1") (pintype "output"))
    )
    (net (code "284") (name "Net-(D09E-OUT)") (class "Default")
      (node (ref "D08") (pin "E2") (pinfunction "E2_E2") (pintype "input"))
      (node (ref "D08") (pin "F2") (pinfunction "F2_F2") (pintype "input"))
      (node (ref "D09") (pin "J2") (pinfunction "OUT_J2") (pintype "output"))
    )
    (net (code "285") (name "Net-(D09F-OUT)") (class "Default")
      (node (ref "D08") (pin "M2") (pinfunction "M2_M2") (pintype "input"))
      (node (ref "D08") (pin "N2") (pinfunction "N2_N2") (pintype "input"))
      (node (ref "D09") (pin "P2") (pinfunction "OUT_P2") (pintype "output"))
    )
    (net (code "286") (name "Net-(D09G-OUT)") (class "Default")
      (node (ref "D08") (pin "T2") (pinfunction "T2_T2") (pintype "input"))
      (node (ref "D08") (pin "U2") (pinfunction "U2_U2") (pintype "input"))
      (node (ref "D09") (pin "V2") (pinfunction "OUT_V2") (pintype "output"))
    )
    (net (code "287") (name "Net-(D10B-OUT)") (class "Default")
      (node (ref "D10") (pin "P2") (pinfunction "OUT_P2") (pintype "output"))
      (node (ref "D14") (pin "J2") (pinfunction "N1_J2") (pintype "input"))
    )
    (net (code "288") (name "Net-(D12A-IN1)") (class "Default")
      (node (ref "D12") (pin "A1") (pinfunction "IN1_A1") (pintype "input"))
      (node (ref "D12") (pin "B1") (pinfunction "IN2_B1") (pintype "input"))
      (node (ref "D12") (pin "C1") (pinfunction "IN3_C1") (pintype "input"))
      (node (ref "D12") (pin "D1") (pinfunction "IN4_D1") (pintype "input"))
      (node (ref "D13") (pin "F2") (pinfunction "F2_F2") (pintype "output"))
    )
    (net (code "289") (name "Net-(D13B-D2)") (class "Default")
      (node (ref "D13") (pin "R2") (pinfunction "E2_R2") (pintype "passive"))
      (node (ref "D13") (pin "S2") (pinfunction "D2_S2") (pintype "passive"))
    )
    (net (code "290") (name "Net-(D14-PadM2)") (class "Default")
      (node (ref "D14") (pin "M2") (pinfunction "M2_M2") (pintype "passive"))
      (node (ref "D14") (pin "V2") (pinfunction "V2_V2") (pintype "passive"))
    )
    (net (code "291") (name "Net-(D14-PadP1)") (class "Default")
      (node (ref "D14") (pin "P1") (pinfunction "P1_P1") (pintype "passive"))
      (node (ref "D14") (pin "V1") (pinfunction "V1_V1") (pintype "passive"))
    )
    (net (code "292") (name "Net-(D14B-M2)") (class "Default")
      (node (ref "D14") (pin "D2") (pinfunction "M2_D2") (pintype "passive"))
      (node (ref "D14") (pin "H1") (pinfunction "P2_H1") (pintype "passive"))
    )
    (net (code "293") (name "Net-(D14B-P1)") (class "Default")
      (node (ref "D14") (pin "A1") (pinfunction "V1_A1") (pintype "passive"))
      (node (ref "D14") (pin "C1") (pinfunction "P1_C1") (pintype "passive"))
    )
    (net (code "294") (name "Net-(D15-PadN2)") (class "Default")
      (node (ref "D15") (pin "N2") (pinfunction "N2_N2") (pintype "passive"))
      (node (ref "D15") (pin "S2") (pinfunction "S2_S2") (pintype "passive"))
    )
    (net (code "295") (name "Net-(D16B-D2)") (class "Default")
      (node (ref "D16") (pin "R2") (pinfunction "E2_R2") (pintype "passive"))
      (node (ref "D16") (pin "V2") (pinfunction "D2_V2") (pintype "passive"))
    )
    (net (code "296") (name "Net-(D16B-H1)") (class "Default")
      (node (ref "D16") (pin "S1") (pinfunction "H1_S1") (pintype "passive"))
      (node (ref "D16") (pin "S2") (pinfunction "L2_S2") (pintype "passive"))
    )
    (net (code "297") (name "Net-(D17-PadD2)") (class "Default")
      (node (ref "D17") (pin "D2") (pinfunction "D2_D2") (pintype "passive"))
      (node (ref "D17") (pin "E2") (pinfunction "E2_E2") (pintype "passive"))
    )
    (net (code "298") (name "Net-(D17B-D2)") (class "Default")
      (node (ref "D17") (pin "R2") (pinfunction "E2_R2") (pintype "passive"))
      (node (ref "D17") (pin "S2") (pinfunction "D2_S2") (pintype "passive"))
    )
    (net (code "299") (name "Net-(IC1A-O)") (class "Default")
      (node (ref "IC1") (pin "8") (pinfunction "O_8") (pintype "output"))
      (node (ref "IC2") (pin "1") (pinfunction "I0_1") (pintype "input"))
      (node (ref "IC2") (pin "2") (pinfunction "I1_2") (pintype "input"))
    )
    (net (code "300") (name "Net-(IC6A-O)") (class "Default")
      (node (ref "IC6") (pin "8") (pinfunction "O_8") (pintype "output"))
      (node (ref "IC7") (pin "1") (pinfunction "I0_1") (pintype "input"))
      (node (ref "IC7") (pin "2") (pinfunction "I1_2") (pintype "input"))
    )
    (net (code "301") (name "PAR") (class "Default")
      (node (ref "A08") (pin "U1") (pinfunction "0_U1") (pintype "output"))
      (node (ref "A25") (pin "T1") (pinfunction "P$2_T1") (pintype "bidirectional"))
    )
    (net (code "302") (name "PC+ES") (class "Default")
      (node (ref "A11") (pin "H2") (pinfunction "IN_H2") (pintype "input"))
      (node (ref "A12") (pin "C1") (pinfunction "OUT_C1") (pintype "output"))
    )
    (net (code "303") (name "PWR_CLR") (class "Default")
      (node (ref "C06") (pin "R2") (pinfunction "OUT_R2") (pintype "output"))
    )
    (net (code "304") (name "RD+WD") (class "Default")
      (node (ref "A09") (pin "P1") (pinfunction "IN3_P1") (pintype "input"))
      (node (ref "B08") (pin "N2") (pinfunction "OUT_N2") (pintype "output"))
      (node (ref "B12") (pin "D2") (pinfunction "IN1_D2") (pintype "input"))
      (node (ref "C12") (pin "R1") (pinfunction "IN2_R1") (pintype "input"))
    )
    (net (code "305") (name "RDD_00") (class "Default")
      (node (ref "A21") (pin "U2") (pinfunction "U2_U2") (pintype "output"))
      (node (ref "B09") (pin "M2") (pinfunction "D_M2") (pintype "input"))
      (node (ref "D09") (pin "C1") (pinfunction "IN2A_C1") (pintype "input"))
      (node (ref "D09") (pin "F2") (pinfunction "IN2A_F2") (pintype "input"))
    )
    (net (code "306") (name "RDD_01") (class "Default")
      (node (ref "B09") (pin "P1") (pinfunction "D_P1") (pintype "input"))
      (node (ref "B20") (pin "U2") (pinfunction "U2_U2") (pintype "output"))
      (node (ref "D09") (pin "J1") (pinfunction "IN2A_J1") (pintype "input"))
      (node (ref "D09") (pin "M2") (pinfunction "IN2A_M2") (pintype "input"))
    )
    (net (code "307") (name "RDD_02") (class "Default")
      (node (ref "A20") (pin "U2") (pinfunction "U2_U2") (pintype "output"))
      (node (ref "B09") (pin "E2") (pinfunction "D_E2") (pintype "input"))
      (node (ref "D09") (pin "P1") (pinfunction "IN2A_P1") (pintype "input"))
      (node (ref "D09") (pin "T2") (pinfunction "IN2A_T2") (pintype "input"))
    )
    (net (code "308") (name "RDMK") (class "Default")
      (node (ref "B18") (pin "U2") (pinfunction "U2_U2") (pintype "output"))
      (node (ref "CD18") (pin "AS2") (pinfunction "AS2_AS2") (pintype "input"))
    )
    (net (code "309") (name "RD_EN") (class "Default")
      (node (ref "C11") (pin "J1") (pinfunction "IN2_J1") (pintype "input"))
      (node (ref "C11") (pin "N2") (pinfunction "OUT_N2") (pintype "output"))
    )
    (net (code "310") (name "RD_EN_LPB_00-02") (class "Default")
      (node (ref "C10") (pin "D2") (pinfunction "IN1A_D2") (pintype "input"))
      (node (ref "C13") (pin "T2") (pinfunction "OUT_T2") (pintype "output"))
      (node (ref "D09") (pin "D1") (pinfunction "IN2B_D1") (pintype "input"))
      (node (ref "D09") (pin "K1") (pinfunction "IN2B_K1") (pintype "input"))
      (node (ref "D09") (pin "R1") (pinfunction "IN2B_R1") (pintype "input"))
    )
    (net (code "311") (name "RD_EN_LPB_03-05") (class "Default")
      (node (ref "C10") (pin "R2") (pinfunction "IN1A_R2") (pintype "input"))
      (node (ref "C13") (pin "R2") (pinfunction "OUT_R2") (pintype "output"))
      (node (ref "D09") (pin "H2") (pinfunction "IN2B_H2") (pintype "input"))
      (node (ref "D09") (pin "N2") (pinfunction "IN2B_N2") (pintype "input"))
      (node (ref "D09") (pin "U2") (pinfunction "IN2B_U2") (pintype "input"))
    )
    (net (code "312") (name "READ_ALL") (class "Default")
      (node (ref "D07") (pin "N2") (pinfunction "O3_N2") (pintype "output"))
    )
    (net (code "313") (name "READ_DATA") (class "Default")
      (node (ref "A10") (pin "L1") (pinfunction "IN1_L1") (pintype "input"))
      (node (ref "C11") (pin "H1") (pinfunction "IN1_H1") (pintype "input"))
      (node (ref "D07") (pin "J2") (pinfunction "O2_J2") (pintype "output"))
    )
    (net (code "314") (name "RSTA") (class "Default")
      (node (ref "IC3") (pin "6") (pinfunction "O_6") (pintype "output"))
    )
    (net (code "315") (name "RSTB") (class "Default")
      (node (ref "IC9") (pin "4") (pinfunction "O_4") (pintype "output"))
    )
    (net (code "316") (name "SE") (class "Default")
      (node (ref "D07") (pin "L2") (pinfunction "O7_L2") (pintype "output"))
    )
    (net (code "317") (name "SEARCH") (class "Default")
      (node (ref "C11") (pin "D2") (pinfunction "IN1_D2") (pintype "input"))
      (node (ref "D07") (pin "E2") (pinfunction "O1_E2") (pintype "output"))
    )
    (net (code "318") (name "SEL") (class "Default")
      (node (ref "A08") (pin "H2") (pinfunction "1_H2") (pintype "output"))
      (node (ref "A25") (pin "S1") (pinfunction "P$2_S1") (pintype "bidirectional"))
    )
    (net (code "319") (name "SHIFT_CK") (class "Default")
      (node (ref "C17") (pin "K1") (pinfunction "OUT_K1") (pintype "output"))
      (node (ref "CD18") (pin "BR2") (pinfunction "BR2_BR2") (pintype "input"))
    )
    (net (code "320") (name "SH_DTB") (class "Default")
      (node (ref "A10") (pin "R2") (pinfunction "IN2_R2") (pintype "input"))
      (node (ref "B09") (pin "B1") (pinfunction "C_B1") (pintype "input"))
      (node (ref "B09") (pin "D2") (pinfunction "C_D2") (pintype "input"))
      (node (ref "B09") (pin "H1") (pinfunction "C_H1") (pintype "input"))
      (node (ref "B09") (pin "L2") (pinfunction "C_L2") (pintype "input"))
      (node (ref "B09") (pin "N1") (pinfunction "C_N1") (pintype "input"))
      (node (ref "B09") (pin "S2") (pinfunction "C_S2") (pintype "input"))
      (node (ref "B10") (pin "E1") (pinfunction "OUT_E1") (pintype "output"))
      (node (ref "C09") (pin "B1") (pinfunction "C_B1") (pintype "input"))
      (node (ref "C09") (pin "D2") (pinfunction "C_D2") (pintype "input"))
      (node (ref "C09") (pin "H1") (pinfunction "C_H1") (pintype "input"))
      (node (ref "C09") (pin "L2") (pinfunction "C_L2") (pintype "input"))
      (node (ref "C09") (pin "N1") (pinfunction "C_N1") (pintype "input"))
      (node (ref "C09") (pin "S2") (pinfunction "C_S2") (pintype "input"))
    )
    (net (code "321") (name "SH_EN") (class "Default")
      (node (ref "A11") (pin "N2") (pinfunction "OUT_N2") (pintype "output"))
      (node (ref "A12") (pin "E2") (pinfunction "IN2_E2") (pintype "input"))
      (node (ref "C10") (pin "A1") (pinfunction "IN1A_A1") (pintype "input"))
      (node (ref "C10") (pin "F1") (pinfunction "IN1A_F1") (pintype "input"))
      (node (ref "C10") (pin "M1") (pinfunction "IN1A_M1") (pintype "input"))
    )
    (net (code "322") (name "SH_ST") (class "Default")
      (node (ref "C17") (pin "A1") (pinfunction "IN_A1") (pintype "input"))
      (node (ref "CD18") (pin "AM1") (pinfunction "AM1_AM1") (pintype "output"))
    )
    (net (code "323") (name "SH_ST-B") (class "Default")
      (node (ref "C16") (pin "P2") (pinfunction "OUT_P2") (pintype "output"))
      (node (ref "CD18") (pin "BC1") (pinfunction "BC1_BC1") (pintype "input"))
    )
    (net (code "324") (name "SP_DY") (class "Default")
      (node (ref "D14") (pin "H2") (pinfunction "H2_H2") (pintype "output"))
    )
    (net (code "325") (name "ST_BLK_MK") (class "Default")
      (node (ref "A26") (pin "K1") (pinfunction "P$2_K1") (pintype "bidirectional"))
      (node (ref "C13") (pin "E2") (pinfunction "IN_E2") (pintype "input"))
      (node (ref "CD18") (pin "AR2") (pinfunction "AR2_AR2") (pintype "output"))
    )
    (net (code "326") (name "ST_CK") (class "Default")
      (node (ref "A10") (pin "P1") (pinfunction "IN1_P1") (pintype "input"))
      (node (ref "A26") (pin "P1") (pinfunction "P$2_P1") (pintype "bidirectional"))
      (node (ref "C13") (pin "J1") (pinfunction "IN_J1") (pintype "input"))
      (node (ref "CD18") (pin "BR1") (pinfunction "BR1_BR1") (pintype "output"))
      (node (ref "D17") (pin "M2") (pinfunction "K2_M2") (pintype "input"))
      (node (ref "D17") (pin "N2") (pinfunction "J2_N2") (pintype "input"))
      (node (ref "D17") (pin "P2") (pinfunction "H2_P2") (pintype "input"))
    )
    (net (code "327") (name "ST_CK_0P") (class "Default")
      (node (ref "B12") (pin "H2") (pinfunction "IN4_H2") (pintype "input"))
      (node (ref "C12") (pin "S1") (pinfunction "IN3_S1") (pintype "input"))
      (node (ref "C13") (pin "B1") (pinfunction "OUT_B1") (pintype "output"))
    )
    (net (code "328") (name "ST_DATA") (class "Default")
      (node (ref "B12") (pin "A1") (pinfunction "IN1_A1") (pintype "input"))
      (node (ref "C13") (pin "H2") (pinfunction "IN_H2") (pintype "input"))
      (node (ref "C16") (pin "J2") (pinfunction "OUT_J2") (pintype "output"))
    )
    (net (code "329") (name "ST_FINAL") (class "Default")
      (node (ref "A09") (pin "S2") (pinfunction "IN2_S2") (pintype "input"))
      (node (ref "A26") (pin "N1") (pinfunction "P$2_N1") (pintype "bidirectional"))
      (node (ref "C11") (pin "D1") (pinfunction "IN1_D1") (pintype "input"))
      (node (ref "C13") (pin "L1") (pinfunction "IN_L1") (pintype "input"))
      (node (ref "CD18") (pin "BL2") (pinfunction "BL2_BL2") (pintype "output"))
    )
    (net (code "330") (name "ST_IDLE") (class "Default")
      (node (ref "A26") (pin "R1") (pinfunction "P$2_R1") (pintype "bidirectional"))
      (node (ref "C13") (pin "K2") (pinfunction "IN_K2") (pintype "input"))
      (node (ref "CD18") (pin "BD2") (pinfunction "BD2_BD2") (pintype "input"))
    )
    (net (code "331") (name "ST_REV_CK") (class "Default")
      (node (ref "A26") (pin "L1") (pinfunction "P$2_L1") (pintype "bidirectional"))
      (node (ref "B11") (pin "S1") (pinfunction "IN3_S1") (pintype "input"))
      (node (ref "C11") (pin "A1") (pinfunction "IN1_A1") (pintype "input"))
      (node (ref "C13") (pin "D1") (pinfunction "IN_D1") (pintype "input"))
      (node (ref "CD18") (pin "BS1") (pinfunction "BS1_BS1") (pintype "output"))
      (node (ref "D12") (pin "F2") (pinfunction "IN3_F2") (pintype "input"))
      (node (ref "D12") (pin "H2") (pinfunction "IN4_H2") (pintype "input"))
    )
    (net (code "332") (name "SWTM") (class "Default")
      (node (ref "A26") (pin "V2") (pinfunction "P$2_V2") (pintype "bidirectional"))
      (node (ref "B06") (pin "P2") (pinfunction "IN_P2") (pintype "input"))
      (node (ref "B08") (pin "V1") (pinfunction "P$1_V1") (pintype "output"))
      (node (ref "B11") (pin "B1") (pinfunction "IN2_B1") (pintype "input"))
      (node (ref "C10") (pin "N2") (pinfunction "IN2B_N2") (pintype "input"))
      (node (ref "C12") (pin "P2") (pinfunction "IN2_P2") (pintype "input"))
      (node (ref "C15") (pin "L1") (pinfunction "IN1_L1") (pintype "input"))
    )
    (net (code "333") (name "SYNC") (class "Default")
      (node (ref "B10") (pin "D2") (pinfunction "IN1_D2") (pintype "input"))
      (node (ref "B10") (pin "E2") (pinfunction "IN2_E2") (pintype "input"))
      (node (ref "CD18") (pin "BN2") (pinfunction "BN2_BN2") (pintype "output"))
    )
    (net (code "334") (name "SYNC_EN") (class "Default")
      (node (ref "B11") (pin "M2") (pinfunction "OUT_M2") (pintype "output"))
      (node (ref "CD18") (pin "BH1") (pinfunction "BH1_BH1") (pintype "input"))
    )
    (net (code "335") (name "T3") (class "Default")
      (node (ref "C17") (pin "S1") (pinfunction "OUT_S1") (pintype "output"))
      (node (ref "D12") (pin "N1") (pinfunction "IN2_N1") (pintype "input"))
      (node (ref "D12") (pin "P1") (pinfunction "IN3_P1") (pintype "input"))
    )
    (net (code "336") (name "TIM") (class "Default")
      (node (ref "A08") (pin "L1") (pinfunction "1_L1") (pintype "output"))
      (node (ref "A25") (pin "U1") (pinfunction "P$2_U1") (pintype "bidirectional"))
    )
    (net (code "337") (name "TM_EN") (class "Default")
      (node (ref "A18") (pin "R2") (pinfunction "R2_R2") (pintype "input"))
      (node (ref "B18") (pin "R2") (pinfunction "R2_R2") (pintype "input"))
      (node (ref "C13") (pin "N1") (pinfunction "IN_N1") (pintype "input"))
      (node (ref "C15") (pin "S1") (pinfunction "OUT_S1") (pintype "output"))
      (node (ref "C16") (pin "M1") (pinfunction "IN1_M1") (pintype "input"))
      (node (ref "C16") (pin "R2") (pinfunction "IN1_R2") (pintype "input"))
    )
    (net (code "338") (name "TP00") (class "Default")
      (node (ref "A08") (pin "B1") (pinfunction "C_B1") (pintype "input"))
      (node (ref "A15") (pin "L1") (pinfunction "OUT_L1") (pintype "output"))
      (node (ref "A16") (pin "M2") (pinfunction "K2_M2") (pintype "input"))
      (node (ref "A16") (pin "N2") (pinfunction "J2_N2") (pintype "input"))
      (node (ref "A16") (pin "P2") (pinfunction "H2_P2") (pintype "input"))
      (node (ref "B10") (pin "F2") (pinfunction "IN3_F2") (pintype "input"))
      (node (ref "B10") (pin "H2") (pinfunction "IN4_H2") (pintype "input"))
      (node (ref "B10") (pin "N1") (pinfunction "IN2_N1") (pintype "input"))
      (node (ref "B13") (pin "B1") (pinfunction "C_B1") (pintype "input"))
      (node (ref "B13") (pin "D2") (pinfunction "C_D2") (pintype "input"))
      (node (ref "B13") (pin "H1") (pinfunction "C_H1") (pintype "input"))
      (node (ref "B15") (pin "J1") (pinfunction "IN2_J1") (pintype "input"))
      (node (ref "C15") (pin "E1") (pinfunction "IN2_E1") (pintype "input"))
    )
    (net (code "339") (name "TP00_A") (class "Default")
      (node (ref "A15") (pin "S1") (pinfunction "OUT_S1") (pintype "output"))
      (node (ref "B10") (pin "H1") (pinfunction "IN2_H1") (pintype "input"))
      (node (ref "C12") (pin "E2") (pinfunction "IN2_E2") (pintype "input"))
    )
    (net (code "340") (name "TP01") (class "Default")
      (node (ref "A12") (pin "J2") (pinfunction "IN2_J2") (pintype "input"))
      (node (ref "A15") (pin "P2") (pinfunction "OUT_P2") (pintype "output"))
      (node (ref "B16") (pin "M2") (pinfunction "K2_M2") (pintype "input"))
      (node (ref "B16") (pin "N2") (pinfunction "J2_N2") (pintype "input"))
      (node (ref "B16") (pin "P2") (pinfunction "H2_P2") (pintype "input"))
      (node (ref "C11") (pin "J2") (pinfunction "IN2_J2") (pintype "input"))
      (node (ref "C15") (pin "B1") (pinfunction "IN2_B1") (pintype "input"))
      (node (ref "CD18") (pin "BF1") (pinfunction "BF1_BF1") (pintype "input"))
    )
    (net (code "341") (name "TP01_A") (class "Default")
      (node (ref "A15") (pin "V2") (pinfunction "OUT_V2") (pintype "output"))
      (node (ref "B12") (pin "T2") (pinfunction "IN3_T2") (pintype "input"))
      (node (ref "C15") (pin "M2") (pinfunction "IN2_M2") (pintype "input"))
    )
    (net (code "342") (name "T_TRK") (class "Default")
      (node (ref "A18") (pin "U2") (pinfunction "U2_U2") (pintype "output"))
      (node (ref "B15") (pin "E2") (pinfunction "IN2_E2") (pintype "input"))
      (node (ref "C15") (pin "R2") (pinfunction "IN2_R2") (pintype "input"))
      (node (ref "D14") (pin "S1") (pinfunction "S1_S1") (pintype "input"))
      (node (ref "D14") (pin "U1") (pinfunction "U1_U1") (pintype "input"))
    )
    (net (code "343") (name "U+M_DY") (class "Default")
      (node (ref "D14") (pin "K1") (pinfunction "H2_K1") (pintype "output"))
    )
    (net (code "344") (name "USR_00") (class "Default")
      (node (ref "A07") (pin "V2") (pinfunction "IN2_V2") (pintype "input"))
      (node (ref "A25") (pin "A1") (pinfunction "P$2_A1") (pintype "bidirectional"))
      (node (ref "B07") (pin "E1") (pinfunction "E1_E1") (pintype "output"))
    )
    (net (code "345") (name "USR_01") (class "Default")
      (node (ref "A07") (pin "U2") (pinfunction "IN1_U2") (pintype "input"))
      (node (ref "A25") (pin "B1") (pinfunction "P$2_B1") (pintype "bidirectional"))
      (node (ref "B07") (pin "H2") (pinfunction "H2_H2") (pintype "output"))
    )
    (net (code "346") (name "USR_02") (class "Default")
      (node (ref "A07") (pin "V1") (pinfunction "IN0_V1") (pintype "input"))
      (node (ref "A25") (pin "C1") (pinfunction "P$2_C1") (pintype "bidirectional"))
      (node (ref "B07") (pin "L1") (pinfunction "L1_L1") (pintype "output"))
    )
    (net (code "347") (name "UTS") (class "Default")
      (node (ref "A10") (pin "E1") (pinfunction "IN2_E1") (pintype "input"))
      (node (ref "A26") (pin "J1") (pinfunction "P$2_J1") (pintype "bidirectional"))
      (node (ref "B15") (pin "P1") (pinfunction "IN1_P1") (pintype "input"))
      (node (ref "C14") (pin "R2") (pinfunction "0_R2") (pintype "output"))
    )
    (net (code "348") (name "VCC") (class "Default")
      (node (ref "AB01") (pin "AA2") (pinfunction "VCC_AA2") (pintype "power_in"))
      (node (ref "AB01") (pin "AB1") (pinfunction "VCC_AB1") (pintype "power_in"))
      (node (ref "AB01") (pin "AC1") (pinfunction "VCC_AC1") (pintype "power_in"))
      (node (ref "AB01") (pin "AD1") (pinfunction "VCC_AD1") (pintype "power_in"))
      (node (ref "AB01") (pin "AE1") (pinfunction "VCC_AE1") (pintype "power_in"))
      (node (ref "AB01") (pin "AF1") (pinfunction "VCC_AF1") (pintype "power_in"))
      (node (ref "AB01") (pin "AH1") (pinfunction "VCC_AH1") (pintype "power_in"))
      (node (ref "AB01") (pin "AJ1") (pinfunction "VCC_AJ1") (pintype "power_in"))
      (node (ref "AB01") (pin "AK1") (pinfunction "VCC_AK1") (pintype "power_in"))
      (node (ref "AB01") (pin "AL1") (pinfunction "VCC_AL1") (pintype "power_in"))
      (node (ref "AB01") (pin "BA2") (pinfunction "VCC_BA2") (pintype "power_in"))
      (node (ref "AB01") (pin "BB1") (pinfunction "VCC_BB1") (pintype "power_in"))
      (node (ref "AB01") (pin "BC1") (pinfunction "VCC_BC1") (pintype "power_in"))
      (node (ref "AB01") (pin "BD1") (pinfunction "VCC_BD1") (pintype "power_in"))
      (node (ref "AB01") (pin "BE1") (pinfunction "VCC_BE1") (pintype "power_in"))
      (node (ref "IC1") (pin "1") (pinfunction "I0_1") (pintype "input"))
      (node (ref "IC1") (pin "2") (pinfunction "I1_2") (pintype "input"))
      (node (ref "IC4") (pin "10") (pinfunction "PRE_10") (pintype "input"))
      (node (ref "IC4") (pin "4") (pinfunction "PRE_4") (pintype "input"))
      (node (ref "IC5") (pin "13") (pinfunction "CLR_13") (pintype "input"))
      (node (ref "IC5") (pin "4") (pinfunction "PRE_4") (pintype "input"))
      (node (ref "IC6") (pin "1") (pinfunction "I0_1") (pintype "input"))
      (node (ref "IC6") (pin "2") (pinfunction "I1_2") (pintype "input"))
    )
    (net (code "349") (name "W+UTS") (class "Default")
      (node (ref "A15") (pin "A1") (pinfunction "IN1_A1") (pintype "input"))
      (node (ref "A15") (pin "H2") (pinfunction "IN4_H2") (pintype "input"))
      (node (ref "C12") (pin "M2") (pinfunction "OUT_M2") (pintype "output"))
    )
    (net (code "350") (name "W-INH") (class "Default")
      (node (ref "A08") (pin "V1") (pinfunction "0_V1") (pintype "output"))
    )
    (net (code "351") (name "W01") (class "Default")
      (node (ref "A26") (pin "J2") (pinfunction "P$2_J2") (pintype "bidirectional"))
      (node (ref "CD18") (pin "BJ2") (pinfunction "BJ2_BJ2") (pintype "output"))
    )
    (net (code "352") (name "W01-W05") (class "Default")
      (node (ref "CD18") (pin "AK1") (pinfunction "AK1_AK1") (pintype "output"))
    )
    (net (code "353") (name "W02") (class "Default")
      (node (ref "A26") (pin "K2") (pinfunction "P$2_K2") (pintype "bidirectional"))
      (node (ref "CD18") (pin "BV2") (pinfunction "BV2_BV2") (pintype "output"))
    )
    (net (code "354") (name "W03") (class "Default")
      (node (ref "A26") (pin "L2") (pinfunction "P$2_L2") (pintype "bidirectional"))
      (node (ref "CD18") (pin "BE2") (pinfunction "BE2_BE2") (pintype "output"))
    )
    (net (code "355") (name "W04") (class "Default")
      (node (ref "A26") (pin "M2") (pinfunction "P$2_M2") (pintype "bidirectional"))
      (node (ref "CD18") (pin "AT2") (pinfunction "AT2_AT2") (pintype "output"))
    )
    (net (code "356") (name "W05") (class "Default")
      (node (ref "A26") (pin "N2") (pinfunction "P$2_N2") (pintype "bidirectional"))
      (node (ref "CD18") (pin "BU2") (pinfunction "BU2_BU2") (pintype "output"))
    )
    (net (code "357") (name "W06") (class "Default")
      (node (ref "A26") (pin "P2") (pinfunction "P$2_P2") (pintype "bidirectional"))
      (node (ref "CD18") (pin "AM2") (pinfunction "AM2_AM2") (pintype "output"))
    )
    (net (code "358") (name "W07") (class "Default")
      (node (ref "A26") (pin "R2") (pinfunction "P$2_R2") (pintype "bidirectional"))
      (node (ref "CD18") (pin "AK2") (pinfunction "AK2_AK2") (pintype "output"))
    )
    (net (code "359") (name "W08") (class "Default")
      (node (ref "A26") (pin "S2") (pinfunction "P$2_S2") (pintype "bidirectional"))
      (node (ref "CD18") (pin "AL1") (pinfunction "AL1_AL1") (pintype "output"))
    )
    (net (code "360") (name "W09") (class "Default")
      (node (ref "A26") (pin "T2") (pinfunction "P$2_T2") (pintype "bidirectional"))
      (node (ref "CD18") (pin "BF2") (pinfunction "BF2_BF2") (pintype "output"))
    )
    (net (code "361") (name "WB00") (class "Default")
      (node (ref "A21") (pin "N2") (pinfunction "N2_N2") (pintype "input"))
      (node (ref "A25") (pin "P2") (pinfunction "P$2_P2") (pintype "bidirectional"))
      (node (ref "B18") (pin "N2") (pinfunction "N2_N2") (pintype "input"))
      (node (ref "C14") (pin "F1") (pinfunction "0_F1") (pintype "output"))
      (node (ref "D09") (pin "A1") (pinfunction "IN1A_A1") (pintype "input"))
    )
    (net (code "362") (name "WB01") (class "Default")
      (node (ref "A25") (pin "R2") (pinfunction "P$2_R2") (pintype "bidirectional"))
      (node (ref "B20") (pin "N2") (pinfunction "N2_N2") (pintype "input"))
      (node (ref "C14") (pin "J2") (pinfunction "0_J2") (pintype "output"))
      (node (ref "D09") (pin "F1") (pinfunction "IN1A_F1") (pintype "input"))
    )
    (net (code "363") (name "WB02") (class "Default")
      (node (ref "A20") (pin "N2") (pinfunction "N2_N2") (pintype "input"))
      (node (ref "A25") (pin "S2") (pinfunction "P$2_S2") (pintype "bidirectional"))
      (node (ref "C14") (pin "M1") (pinfunction "0_M1") (pintype "output"))
      (node (ref "D09") (pin "M1") (pinfunction "IN1A_M1") (pintype "input"))
    )
    (net (code "364") (name "WC") (class "Default")
      (node (ref "A26") (pin "H1") (pinfunction "P$2_H1") (pintype "bidirectional"))
      (node (ref "B10") (pin "M1") (pinfunction "IN1_M1") (pintype "input"))
      (node (ref "B11") (pin "K1") (pinfunction "IN1_K1") (pintype "input"))
      (node (ref "IC5") (pin "9") (pinfunction "Q_9") (pintype "output"))
    )
    (net (code "365") (name "WC0") (class "Default")
      (node (ref "C06") (pin "M2") (pinfunction "IN_M2") (pintype "input"))
      (node (ref "IC9") (pin "8") (pinfunction "O_8") (pintype "output"))
    )
    (net (code "366") (name "WRITE_ALL") (class "Default")
      (node (ref "A08") (pin "S2") (pinfunction "C_S2") (pintype "input"))
      (node (ref "B11") (pin "M1") (pinfunction "IN3_M1") (pintype "input"))
      (node (ref "B12") (pin "F1") (pinfunction "IN1_F1") (pintype "input"))
      (node (ref "D07") (pin "M2") (pinfunction "O5_M2") (pintype "output"))
    )
    (net (code "367") (name "WRITE_DATA") (class "Default")
      (node (ref "A09") (pin "R2") (pinfunction "IN1_R2") (pintype "input"))
      (node (ref "B11") (pin "R1") (pinfunction "IN2_R1") (pintype "input"))
      (node (ref "B12") (pin "B1") (pinfunction "IN2_B1") (pintype "input"))
      (node (ref "B12") (pin "P1") (pinfunction "IN3_P1") (pintype "input"))
      (node (ref "D07") (pin "F2") (pinfunction "O4_F2") (pintype "output"))
    )
    (net (code "368") (name "WRITE_OK") (class "Default")
      (node (ref "A22") (pin "D2") (pinfunction "D2_D2") (pintype "output"))
      (node (ref "B11") (pin "C1") (pinfunction "IN3_C1") (pintype "input"))
      (node (ref "B15") (pin "R1") (pinfunction "IN2_R1") (pintype "input"))
      (node (ref "C17") (pin "H2") (pinfunction "IN_H2") (pintype "input"))
    )
    (net (code "369") (name "WRITE_OK+UTS") (class "Default")
      (node (ref "B12") (pin "D1") (pinfunction "IN4_D1") (pintype "input"))
      (node (ref "B12") (pin "K1") (pinfunction "IN4_K1") (pintype "input"))
      (node (ref "C17") (pin "M1") (pinfunction "OUT_M1") (pintype "output"))
    )
    (net (code "370") (name "WRTM") (class "Default")
      (node (ref "B11") (pin "A1") (pinfunction "IN1_A1") (pintype "input"))
      (node (ref "C10") (pin "K2") (pinfunction "IN1A_K2") (pintype "input"))
      (node (ref "C12") (pin "N2") (pinfunction "IN1_N2") (pintype "input"))
      (node (ref "D07") (pin "H2") (pinfunction "O6_H2") (pintype "output"))
    )
    (net (code "371") (name "WRTM+FR03") (class "Default")
      (node (ref "B08") (pin "K2") (pinfunction "OUT_K2") (pintype "output"))
      (node (ref "C12") (pin "M1") (pinfunction "IN3_M1") (pintype "input"))
      (node (ref "C12") (pin "V2") (pinfunction "IN3_V2") (pintype "input"))
    )
    (net (code "372") (name "WR_EN") (class "Default")
      (node (ref "A20") (pin "R2") (pinfunction "R2_R2") (pintype "input"))
      (node (ref "A21") (pin "R2") (pinfunction "R2_R2") (pintype "input"))
      (node (ref "A26") (pin "F1") (pinfunction "P$2_F1") (pintype "bidirectional"))
      (node (ref "B20") (pin "R2") (pinfunction "R2_R2") (pintype "input"))
      (node (ref "C10") (pin "H2") (pinfunction "IN2B_H2") (pintype "input"))
      (node (ref "C10") (pin "U2") (pinfunction "IN2B_U2") (pintype "input"))
      (node (ref "C12") (pin "D2") (pinfunction "IN1_D2") (pintype "input"))
      (node (ref "C14") (pin "U1") (pinfunction "0_U1") (pintype "output"))
      (node (ref "C15") (pin "A1") (pinfunction "IN1_A1") (pintype "input"))
      (node (ref "C15") (pin "M1") (pinfunction "IN2_M1") (pintype "input"))
      (node (ref "D09") (pin "B1") (pinfunction "IN1B_B1") (pintype "input"))
      (node (ref "D09") (pin "E2") (pinfunction "IN1B_E2") (pintype "input"))
      (node (ref "D09") (pin "H1") (pinfunction "IN1B_H1") (pintype "input"))
      (node (ref "D09") (pin "L2") (pinfunction "IN1B_L2") (pintype "input"))
      (node (ref "D09") (pin "N1") (pinfunction "IN1B_N1") (pintype "input"))
      (node (ref "D09") (pin "S2") (pinfunction "IN1B_S2") (pintype "input"))
    )
    (net (code "373") (name "XOR_TO_LPB") (class "Default")
      (node (ref "C10") (pin "E2") (pinfunction "IN1B_E2") (pintype "input"))
      (node (ref "C10") (pin "F2") (pinfunction "IN2A_F2") (pintype "input"))
      (node (ref "C10") (pin "S2") (pinfunction "IN1B_S2") (pintype "input"))
      (node (ref "C10") (pin "T2") (pinfunction "IN2A_T2") (pintype "input"))
      (node (ref "D12") (pin "P2") (pinfunction "OUT_P2") (pintype "output"))
    )
    (net (code "374") (name "XSAD") (class "Default")
      (node (ref "A09") (pin "R1") (pinfunction "IN4_R1") (pintype "input"))
      (node (ref "A11") (pin "L2") (pinfunction "OUT_L2") (pintype "output"))
    )
    (net (code "375") (name "XSA_DY") (class "Default")
      (node (ref "A08") (pin "D2") (pinfunction "C_D2") (pintype "input"))
      (node (ref "B14") (pin "B1") (pinfunction "C_B1") (pintype "input"))
      (node (ref "B14") (pin "L2") (pinfunction "C_L2") (pintype "input"))
      (node (ref "C17") (pin "T2") (pinfunction "OUT_T2") (pintype "output"))
    )
    (net (code "376") (name "XSTA") (class "Default")
      (node (ref "B07") (pin "B1") (pinfunction "B1_B1") (pintype "input"))
      (node (ref "B07") (pin "D2") (pinfunction "D2_D2") (pintype "input"))
      (node (ref "B07") (pin "H1") (pinfunction "H1_H1") (pintype "input"))
      (node (ref "B07") (pin "L2") (pinfunction "L2_L2") (pintype "input"))
      (node (ref "B07") (pin "N1") (pinfunction "N1_N1") (pintype "input"))
      (node (ref "B07") (pin "S2") (pinfunction "S2_S2") (pintype "input"))
      (node (ref "C07") (pin "B1") (pinfunction "B1_B1") (pintype "input"))
      (node (ref "C07") (pin "D2") (pinfunction "D2_D2") (pintype "input"))
      (node (ref "C07") (pin "H1") (pinfunction "H1_H1") (pintype "input"))
      (node (ref "C07") (pin "L2") (pinfunction "L2_L2") (pintype "input"))
      (node (ref "D13") (pin "M2") (pinfunction "K2_M2") (pintype "input"))
      (node (ref "D13") (pin "N2") (pinfunction "J2_N2") (pintype "input"))
      (node (ref "D13") (pin "P2") (pinfunction "H2_P2") (pintype "input"))
      (node (ref "IC3") (pin "2") (pinfunction "O_2") (pintype "output"))
      (node (ref "IC5") (pin "11") (pinfunction "CLK_11") (pintype "input"))
    )
    (net (code "377") (name "unconnected-(A07A-O8-PadP2)") (class "Default")
      (node (ref "A07") (pin "P2") (pinfunction "O8_P2") (pintype "output"))
    )
    (net (code "378") (name "unconnected-(A07A-O9-PadR2)") (class "Default")
      (node (ref "A07") (pin "R2") (pinfunction "O9_R2") (pintype "output"))
    )
    (net (code "379") (name "unconnected-(A07A-~{O8}-PadP1)") (class "Default")
      (node (ref "A07") (pin "P1") (pinfunction "~{O8}_P1") (pintype "output"))
    )
    (net (code "380") (name "unconnected-(A07A-~{O9}-PadR1)") (class "Default")
      (node (ref "A07") (pin "R1") (pinfunction "~{O9}_R1") (pintype "output"))
    )
    (net (code "381") (name "unconnected-(A14-PadD1)") (class "Default")
      (node (ref "A14") (pin "D1") (pinfunction "D1_D1") (pintype "passive"))
    )
    (net (code "382") (name "unconnected-(A14-PadE1)") (class "Default")
      (node (ref "A14") (pin "E1") (pinfunction "E1_E1") (pintype "passive"))
    )
    (net (code "383") (name "unconnected-(A14-PadF1)") (class "Default")
      (node (ref "A14") (pin "F1") (pinfunction "F1_F1") (pintype "passive"))
    )
    (net (code "384") (name "unconnected-(A14-PadJ1)") (class "Default")
      (node (ref "A14") (pin "J1") (pinfunction "J1_J1") (pintype "passive"))
    )
    (net (code "385") (name "unconnected-(A14B-D1-PadN1)") (class "Default")
      (node (ref "A14") (pin "N1") (pinfunction "D1_N1") (pintype "passive"))
    )
    (net (code "386") (name "unconnected-(A14B-E1-PadP1)") (class "Default")
      (node (ref "A14") (pin "P1") (pinfunction "E1_P1") (pintype "passive"))
    )
    (net (code "387") (name "unconnected-(A14B-F1-PadR1)") (class "Default")
      (node (ref "A14") (pin "R1") (pinfunction "F1_R1") (pintype "passive"))
    )
    (net (code "388") (name "unconnected-(A14B-J1-PadU1)") (class "Default")
      (node (ref "A14") (pin "U1") (pinfunction "J1_U1") (pintype "passive"))
    )
    (net (code "389") (name "unconnected-(A18-PadH2)") (class "Default")
      (node (ref "A18") (pin "H2") (pinfunction "H2_H2") (pintype "input"))
    )
    (net (code "390") (name "unconnected-(A18-PadL2)") (class "Default")
      (node (ref "A18") (pin "L2") (pinfunction "L2_L2") (pintype "input"))
    )
    (net (code "391") (name "unconnected-(A18-PadM2)") (class "Default")
      (node (ref "A18") (pin "M2") (pinfunction "M2_M2") (pintype "input"))
    )
    (net (code "392") (name "unconnected-(A20-PadH2)") (class "Default")
      (node (ref "A20") (pin "H2") (pinfunction "H2_H2") (pintype "input"))
    )
    (net (code "393") (name "unconnected-(A20-PadL2)") (class "Default")
      (node (ref "A20") (pin "L2") (pinfunction "L2_L2") (pintype "input"))
    )
    (net (code "394") (name "unconnected-(A20-PadM2)") (class "Default")
      (node (ref "A20") (pin "M2") (pinfunction "M2_M2") (pintype "input"))
    )
    (net (code "395") (name "unconnected-(A21-PadH2)") (class "Default")
      (node (ref "A21") (pin "H2") (pinfunction "H2_H2") (pintype "input"))
    )
    (net (code "396") (name "unconnected-(A21-PadL2)") (class "Default")
      (node (ref "A21") (pin "L2") (pinfunction "L2_L2") (pintype "input"))
    )
    (net (code "397") (name "unconnected-(A21-PadM2)") (class "Default")
      (node (ref "A21") (pin "M2") (pinfunction "M2_M2") (pintype "input"))
    )
    (net (code "398") (name "unconnected-(A22-PadE2)") (class "Default")
      (node (ref "A22") (pin "E2") (pinfunction "E2_E2") (pintype "passive"))
    )
    (net (code "399") (name "unconnected-(AB01-PadBM1)") (class "Default")
      (node (ref "AB01") (pin "BM1") (pinfunction "BM1_BM1") (pintype "output"))
    )
    (net (code "400") (name "unconnected-(AB01-PadBN1)") (class "Default")
      (node (ref "AB01") (pin "BN1") (pinfunction "BN1_BN1") (pintype "input"))
    )
    (net (code "401") (name "unconnected-(AB01-PadBP1)") (class "Default")
      (node (ref "AB01") (pin "BP1") (pinfunction "BP1_BP1") (pintype "input"))
    )
    (net (code "402") (name "unconnected-(AB01-PadBR1)") (class "Default")
      (node (ref "AB01") (pin "BR1") (pinfunction "BR1_BR1") (pintype "output"))
    )
    (net (code "403") (name "unconnected-(B05F-B-PadL2)") (class "Default")
      (node (ref "B05") (pin "L2") (pinfunction "B_L2") (pintype "input"))
    )
    (net (code "404") (name "unconnected-(B05F-E-PadP2)") (class "Default")
      (node (ref "B05") (pin "P2") (pinfunction "E_P2") (pintype "open_collector"))
    )
    (net (code "405") (name "unconnected-(B18-PadH2)") (class "Default")
      (node (ref "B18") (pin "H2") (pinfunction "H2_H2") (pintype "input"))
    )
    (net (code "406") (name "unconnected-(B18-PadL2)") (class "Default")
      (node (ref "B18") (pin "L2") (pinfunction "L2_L2") (pintype "input"))
    )
    (net (code "407") (name "unconnected-(B18-PadM2)") (class "Default")
      (node (ref "B18") (pin "M2") (pinfunction "M2_M2") (pintype "input"))
    )
    (net (code "408") (name "unconnected-(B20-PadH2)") (class "Default")
      (node (ref "B20") (pin "H2") (pinfunction "H2_H2") (pintype "input"))
    )
    (net (code "409") (name "unconnected-(B20-PadL2)") (class "Default")
      (node (ref "B20") (pin "L2") (pinfunction "L2_L2") (pintype "input"))
    )
    (net (code "410") (name "unconnected-(B20-PadM2)") (class "Default")
      (node (ref "B20") (pin "M2") (pinfunction "M2_M2") (pintype "input"))
    )
    (net (code "411") (name "unconnected-(B22H-A-PadR2)") (class "Default")
      (node (ref "B22") (pin "R2") (pinfunction "A_R2") (pintype "input"))
    )
    (net (code "412") (name "unconnected-(B22H-D-PadU2)") (class "Default")
      (node (ref "B22") (pin "U2") (pinfunction "D_U2") (pintype "output"))
    )
    (net (code "413") (name "unconnected-(C02A-IN13-PadP2)") (class "Default")
      (node (ref "C02") (pin "P2") (pinfunction "IN13_P2") (pintype "input"))
    )
    (net (code "414") (name "unconnected-(C02A-IN14-PadS2)") (class "Default")
      (node (ref "C02") (pin "S2") (pinfunction "IN14_S2") (pintype "input"))
    )
    (net (code "415") (name "unconnected-(C02A-O13-PadR2)") (class "Default")
      (node (ref "C02") (pin "R2") (pinfunction "O13_R2") (pintype "output"))
    )
    (net (code "416") (name "unconnected-(C02A-O14-PadT2)") (class "Default")
      (node (ref "C02") (pin "T2") (pinfunction "O14_T2") (pintype "output"))
    )
    (net (code "417") (name "unconnected-(C03A-IN13-PadP2)") (class "Default")
      (node (ref "C03") (pin "P2") (pinfunction "IN13_P2") (pintype "input"))
    )
    (net (code "418") (name "unconnected-(C03A-IN14-PadS2)") (class "Default")
      (node (ref "C03") (pin "S2") (pinfunction "IN14_S2") (pintype "input"))
    )
    (net (code "419") (name "unconnected-(C03A-IN15-PadU2)") (class "Default")
      (node (ref "C03") (pin "U2") (pinfunction "IN15_U2") (pintype "input"))
    )
    (net (code "420") (name "unconnected-(C03A-O13-PadR2)") (class "Default")
      (node (ref "C03") (pin "R2") (pinfunction "O13_R2") (pintype "output"))
    )
    (net (code "421") (name "unconnected-(C03A-O14-PadT2)") (class "Default")
      (node (ref "C03") (pin "T2") (pinfunction "O14_T2") (pintype "output"))
    )
    (net (code "422") (name "unconnected-(C03A-O15-PadV2)") (class "Default")
      (node (ref "C03") (pin "V2") (pinfunction "O15_V2") (pintype "output"))
    )
    (net (code "423") (name "unconnected-(C07-PadN1)") (class "Default")
      (node (ref "C07") (pin "N1") (pinfunction "N1_N1") (pintype "input"))
    )
    (net (code "424") (name "unconnected-(C07-PadP1)") (class "Default")
      (node (ref "C07") (pin "P1") (pinfunction "P1_P1") (pintype "input"))
    )
    (net (code "425") (name "unconnected-(C07-PadR1)") (class "Default")
      (node (ref "C07") (pin "R1") (pinfunction "R1_R1") (pintype "input"))
    )
    (net (code "426") (name "unconnected-(C07-PadS1)") (class "Default")
      (node (ref "C07") (pin "S1") (pinfunction "S1_S1") (pintype "output"))
    )
    (net (code "427") (name "unconnected-(C07-PadS2)") (class "Default")
      (node (ref "C07") (pin "S2") (pinfunction "S2_S2") (pintype "input"))
    )
    (net (code "428") (name "unconnected-(C07-PadT2)") (class "Default")
      (node (ref "C07") (pin "T2") (pinfunction "T2_T2") (pintype "input"))
    )
    (net (code "429") (name "unconnected-(C07-PadU1)") (class "Default")
      (node (ref "C07") (pin "U1") (pinfunction "U1_U1") (pintype "output"))
    )
    (net (code "430") (name "unconnected-(C07-PadU2)") (class "Default")
      (node (ref "C07") (pin "U2") (pinfunction "U2_U2") (pintype "input"))
    )
    (net (code "431") (name "unconnected-(C07-PadV1)") (class "Default")
      (node (ref "C07") (pin "V1") (pinfunction "V1_V1") (pintype "output"))
    )
    (net (code "432") (name "unconnected-(C07-PadV2)") (class "Default")
      (node (ref "C07") (pin "V2") (pinfunction "V2_V2") (pintype "output"))
    )
    (net (code "433") (name "unconnected-(CD18-PadAN2)") (class "Default")
      (node (ref "CD18") (pin "AN2") (pinfunction "AN2_AN2") (pintype "output"))
    )
    (net (code "434") (name "unconnected-(CD18-PadAU1)") (class "Default")
      (node (ref "CD18") (pin "AU1") (pinfunction "AU1_AU1") (pintype "output"))
    )
    (net (code "435") (name "unconnected-(D07A-O8-PadP2)") (class "Default")
      (node (ref "D07") (pin "P2") (pinfunction "O8_P2") (pintype "output"))
    )
    (net (code "436") (name "unconnected-(D07A-O9-PadR2)") (class "Default")
      (node (ref "D07") (pin "R2") (pinfunction "O9_R2") (pintype "output"))
    )
    (net (code "437") (name "unconnected-(D07A-~{O8}-PadP1)") (class "Default")
      (node (ref "D07") (pin "P1") (pinfunction "~{O8}_P1") (pintype "output"))
    )
    (net (code "438") (name "unconnected-(D07A-~{O9}-PadR1)") (class "Default")
      (node (ref "D07") (pin "R1") (pinfunction "~{O9}_R1") (pintype "output"))
    )
    (net (code "439") (name "unconnected-(D13-PadD2)") (class "Default")
      (node (ref "D13") (pin "D2") (pinfunction "D2_D2") (pintype "passive"))
    )
    (net (code "440") (name "unconnected-(D13-PadE2)") (class "Default")
      (node (ref "D13") (pin "E2") (pinfunction "E2_E2") (pintype "passive"))
    )
    (net (code "441") (name "unconnected-(D14-PadN2)") (class "Default")
      (node (ref "D14") (pin "N2") (pinfunction "N2_N2") (pintype "passive"))
    )
    (net (code "442") (name "unconnected-(D14-PadP2)") (class "Default")
      (node (ref "D14") (pin "P2") (pinfunction "P2_P2") (pintype "passive"))
    )
    (net (code "443") (name "unconnected-(D14-PadR2)") (class "Default")
      (node (ref "D14") (pin "R2") (pinfunction "R2_R2") (pintype "passive"))
    )
    (net (code "444") (name "unconnected-(D14-PadS2)") (class "Default")
      (node (ref "D14") (pin "S2") (pinfunction "S2_S2") (pintype "passive"))
    )
    (net (code "445") (name "unconnected-(D14-PadU2)") (class "Default")
      (node (ref "D14") (pin "U2") (pinfunction "U2_U2") (pintype "passive"))
    )
    (net (code "446") (name "unconnected-(D14B-N2-PadJ1)") (class "Default")
      (node (ref "D14") (pin "J1") (pinfunction "N2_J1") (pintype "passive"))
    )
    (net (code "447") (name "unconnected-(D14B-R2-PadF1)") (class "Default")
      (node (ref "D14") (pin "F1") (pinfunction "R2_F1") (pintype "passive"))
    )
    (net (code "448") (name "unconnected-(D14B-S2-PadE1)") (class "Default")
      (node (ref "D14") (pin "E1") (pinfunction "S2_E1") (pintype "passive"))
    )
    (net (code "449") (name "unconnected-(D14B-U2-PadD1)") (class "Default")
      (node (ref "D14") (pin "D1") (pinfunction "U2_D1") (pintype "passive"))
    )
    (net (code "450") (name "unconnected-(D14B-V2-PadB1)") (class "Default")
      (node (ref "D14") (pin "B1") (pinfunction "V2_B1") (pintype "passive"))
    )
    (net (code "451") (name "unconnected-(D15-PadE2)") (class "Default")
      (node (ref "D15") (pin "E2") (pinfunction "E2_E2") (pintype "output"))
    )
    (net (code "452") (name "unconnected-(D15-PadM2)") (class "Default")
      (node (ref "D15") (pin "M2") (pinfunction "M2_M2") (pintype "passive"))
    )
    (net (code "453") (name "unconnected-(D15-PadP2)") (class "Default")
      (node (ref "D15") (pin "P2") (pinfunction "P2_P2") (pintype "passive"))
    )
    (net (code "454") (name "unconnected-(D15-PadR2)") (class "Default")
      (node (ref "D15") (pin "R2") (pinfunction "R2_R2") (pintype "passive"))
    )
    (net (code "455") (name "unconnected-(D15-PadT2)") (class "Default")
      (node (ref "D15") (pin "T2") (pinfunction "T2_T2") (pintype "passive"))
    )
    (net (code "456") (name "unconnected-(D16B-D1-PadN1)") (class "Default")
      (node (ref "D16") (pin "N1") (pinfunction "D1_N1") (pintype "passive"))
    )
    (net (code "457") (name "unconnected-(D16B-E1-PadP1)") (class "Default")
      (node (ref "D16") (pin "P1") (pinfunction "E1_P1") (pintype "passive"))
    )
    (net (code "458") (name "unconnected-(D16B-F1-PadR1)") (class "Default")
      (node (ref "D16") (pin "R1") (pinfunction "F1_R1") (pintype "passive"))
    )
    (net (code "459") (name "unconnected-(D16B-J1-PadU1)") (class "Default")
      (node (ref "D16") (pin "U1") (pinfunction "J1_U1") (pintype "passive"))
    )
    (net (code "460") (name "~{0_TO_AC}") (class "Default")
      (node (ref "B05") (pin "H1") (pinfunction "B_H1") (pintype "input"))
      (node (ref "B06") (pin "T2") (pinfunction "OUT_T2") (pintype "output"))
    )
    (net (code "461") (name "~{0_TO_DTB}") (class "Default")
      (node (ref "A11") (pin "L1") (pinfunction "IN_L1") (pintype "input"))
      (node (ref "B09") (pin "A1") (pinfunction "R_A1") (pintype "input"))
      (node (ref "B09") (pin "K2") (pinfunction "R_K2") (pintype "input"))
      (node (ref "B10") (pin "L1") (pinfunction "OUT_L1") (pintype "output"))
      (node (ref "C09") (pin "A1") (pinfunction "R_A1") (pintype "input"))
      (node (ref "C09") (pin "K2") (pinfunction "R_K2") (pintype "input"))
    )
    (net (code "462") (name "~{0_TO_EF}") (class "Default")
      (node (ref "A08") (pin "A1") (pinfunction "R_A1") (pintype "input"))
      (node (ref "A08") (pin "N2") (pinfunction "S_N2") (pintype "input"))
      (node (ref "A08") (pin "R1") (pinfunction "S_R1") (pintype "input"))
      (node (ref "A11") (pin "F2") (pinfunction "OUT_F2") (pintype "output"))
    )
    (net (code "463") (name "~{0_TO_LPB}") (class "Default")
      (node (ref "D08") (pin "A1") (pinfunction "A1_A1") (pintype "input"))
      (node (ref "D08") (pin "K2") (pinfunction "K2_K2") (pintype "input"))
      (node (ref "D12") (pin "J2") (pinfunction "OUT_J2") (pintype "output"))
    )
    (net (code "464") (name "~{0_TO_STATE}") (class "Default")
      (node (ref "C16") (pin "L1") (pinfunction "OUT_L1") (pintype "output"))
      (node (ref "CD18") (pin "AV2") (pinfunction "AV2_AV2") (pintype "input"))
    )
    (net (code "465") (name "~{0_TO_STA}") (class "Default")
      (node (ref "A11") (pin "P1") (pinfunction "OUT_P1") (pintype "output"))
      (node (ref "B07") (pin "A1") (pinfunction "A1_A1") (pintype "input"))
      (node (ref "B07") (pin "K2") (pinfunction "K2_K2") (pintype "input"))
      (node (ref "B11") (pin "P2") (pinfunction "IN2_P2") (pintype "input"))
      (node (ref "C07") (pin "A1") (pinfunction "A1_A1") (pintype "input"))
    )
    (net (code "466") (name "~{0_TO_W}") (class "Default")
      (node (ref "C16") (pin "E1") (pinfunction "OUT_E1") (pintype "output"))
      (node (ref "CD18") (pin "BH2") (pinfunction "BH2_BH2") (pintype "input"))
    )
    (net (code "467") (name "~{00}") (class "Default")
      (node (ref "A07") (pin "D1") (pinfunction "~{O0}_D1") (pintype "output"))
      (node (ref "B22") (pin "S2") (pinfunction "B_S2") (pintype "input"))
    )
    (net (code "468") (name "~{01}") (class "Default")
      (node (ref "A07") (pin "E1") (pinfunction "~{O1}_E1") (pintype "output"))
      (node (ref "A23") (pin "N1") (pinfunction "B_N1") (pintype "input"))
    )
    (net (code "469") (name "~{02}") (class "Default")
      (node (ref "A07") (pin "J1") (pinfunction "~{O2}_J1") (pintype "output"))
      (node (ref "A23") (pin "D2") (pinfunction "A_D2") (pintype "input"))
    )
    (net (code "470") (name "~{03}") (class "Default")
      (node (ref "A07") (pin "N1") (pinfunction "~{O3}_N1") (pintype "output"))
      (node (ref "A23") (pin "E2") (pinfunction "B_E2") (pintype "input"))
    )
    (net (code "471") (name "~{04}") (class "Default")
      (node (ref "A07") (pin "F1") (pinfunction "~{O4}_F1") (pintype "output"))
      (node (ref "A23") (pin "K2") (pinfunction "A_K2") (pintype "input"))
    )
    (net (code "472") (name "~{05}") (class "Default")
      (node (ref "A07") (pin "M1") (pinfunction "~{O5}_M1") (pintype "output"))
      (node (ref "A23") (pin "L2") (pinfunction "B_L2") (pintype "input"))
    )
    (net (code "473") (name "~{06}") (class "Default")
      (node (ref "A07") (pin "H1") (pinfunction "~{O6}_H1") (pintype "output"))
      (node (ref "A23") (pin "R2") (pinfunction "A_R2") (pintype "input"))
    )
    (net (code "474") (name "~{07}") (class "Default")
      (node (ref "A07") (pin "L1") (pinfunction "~{O7}_L1") (pintype "output"))
      (node (ref "A23") (pin "S2") (pinfunction "B_S2") (pintype "input"))
    )
    (net (code "475") (name "~{76}") (class "Default")
      (node (ref "C06") (pin "T2") (pinfunction "OUT_T2") (pintype "output"))
      (node (ref "D12") (pin "R2") (pinfunction "IN1_R2") (pintype "input"))
      (node (ref "D12") (pin "S2") (pinfunction "IN2_S2") (pintype "input"))
    )
    (net (code "476") (name "~{77}") (class "Default")
      (node (ref "C06") (pin "V2") (pinfunction "OUT_V2") (pintype "output"))
      (node (ref "D12") (pin "T2") (pinfunction "IN3_T2") (pintype "input"))
      (node (ref "D12") (pin "U2") (pinfunction "IN4_U2") (pintype "input"))
    )
    (net (code "477") (name "~{ADDR_ACC}") (class "Default")
      (node (ref "B08") (pin "T2") (pinfunction "IN1_T2") (pintype "input"))
      (node (ref "C17") (pin "P1") (pinfunction "OUT_P1") (pintype "output"))
    )
    (net (code "478") (name "~{B-BRK}") (class "Default")
      (node (ref "B02") (pin "C1") (pinfunction "C_C1") (pintype "input"))
      (node (ref "B02") (pin "F2") (pinfunction "C_F2") (pintype "input"))
      (node (ref "B02") (pin "J1") (pinfunction "C_J1") (pintype "input"))
      (node (ref "B02") (pin "M2") (pinfunction "C_M2") (pintype "input"))
      (node (ref "B02") (pin "P1") (pinfunction "C_P1") (pintype "input"))
      (node (ref "B02") (pin "T2") (pinfunction "C_T2") (pintype "input"))
      (node (ref "B10") (pin "V2") (pinfunction "OUT_V2") (pintype "output"))
    )
    (net (code "479") (name "~{BAC_00}") (class "Default")
      (node (ref "B06") (pin "A1") (pinfunction "IN_A1") (pintype "input"))
      (node (ref "C03") (pin "B1") (pinfunction "O1_B1") (pintype "output"))
      (node (ref "D10") (pin "F1") (pinfunction "IN1_F1") (pintype "input"))
    )
    (net (code "480") (name "~{BAC_01}") (class "Default")
      (node (ref "B06") (pin "D1") (pinfunction "IN_D1") (pintype "input"))
      (node (ref "C03") (pin "E1") (pinfunction "O2_E1") (pintype "output"))
      (node (ref "D10") (pin "H1") (pinfunction "IN2_H1") (pintype "input"))
    )
    (net (code "481") (name "~{BAC_02}") (class "Default")
      (node (ref "B06") (pin "F1") (pinfunction "IN_F1") (pintype "input"))
      (node (ref "C03") (pin "H1") (pinfunction "O3_H1") (pintype "output"))
      (node (ref "D10") (pin "J1") (pinfunction "IN3_J1") (pintype "input"))
    )
    (net (code "482") (name "~{BAC_03}") (class "Default")
      (node (ref "B06") (pin "J1") (pinfunction "IN_J1") (pintype "input"))
      (node (ref "C03") (pin "K1") (pinfunction "O4_K1") (pintype "output"))
      (node (ref "D10") (pin "K1") (pinfunction "IN4_K1") (pintype "input"))
    )
    (net (code "483") (name "~{BAC_04}") (class "Default")
      (node (ref "B06") (pin "L1") (pinfunction "IN_L1") (pintype "input"))
      (node (ref "C03") (pin "M1") (pinfunction "O5_M1") (pintype "output"))
      (node (ref "D10") (pin "K2") (pinfunction "IN5_K2") (pintype "input"))
    )
    (net (code "484") (name "~{BAC_05}") (class "Default")
      (node (ref "B06") (pin "N1") (pinfunction "IN_N1") (pintype "input"))
      (node (ref "C03") (pin "P1") (pinfunction "O6_P1") (pintype "output"))
    )
    (net (code "485") (name "~{BAC_06}") (class "Default")
      (node (ref "B06") (pin "R1") (pinfunction "IN_R1") (pintype "input"))
      (node (ref "C03") (pin "S1") (pinfunction "O7_S1") (pintype "output"))
    )
    (net (code "486") (name "~{BAC_07}") (class "Default")
      (node (ref "B06") (pin "V1") (pinfunction "IN_V1") (pintype "input"))
      (node (ref "C03") (pin "U1") (pinfunction "O8_U1") (pintype "output"))
    )
    (net (code "487") (name "~{BAC_08}") (class "Default")
      (node (ref "B06") (pin "C1") (pinfunction "IN_C1") (pintype "input"))
      (node (ref "C03") (pin "F2") (pinfunction "O9_F2") (pintype "output"))
    )
    (net (code "488") (name "~{BAC_09}") (class "Default")
      (node (ref "B06") (pin "E2") (pinfunction "IN_E2") (pintype "input"))
      (node (ref "C03") (pin "J2") (pinfunction "O10_J2") (pintype "output"))
    )
    (net (code "489") (name "~{BAC_10}") (class "Default")
      (node (ref "A10") (pin "D2") (pinfunction "IN1_D2") (pintype "input"))
      (node (ref "B06") (pin "H2") (pinfunction "IN_H2") (pintype "input"))
      (node (ref "C03") (pin "L2") (pinfunction "O11_L2") (pintype "output"))
    )
    (net (code "490") (name "~{BAC_11}") (class "Default")
      (node (ref "B06") (pin "K2") (pinfunction "IN_K2") (pintype "input"))
      (node (ref "C03") (pin "N2") (pinfunction "O12_N2") (pintype "output"))
      (node (ref "C11") (pin "R2") (pinfunction "IN2_R2") (pintype "input"))
    )
    (net (code "491") (name "~{BLK_IN_SYNC}") (class "Default")
      (node (ref "A10") (pin "A1") (pinfunction "IN1_A1") (pintype "input"))
      (node (ref "C13") (pin "R1") (pinfunction "IN_R1") (pintype "input"))
      (node (ref "D10") (pin "J2") (pinfunction "OUT_J2") (pintype "output"))
    )
    (net (code "492") (name "~{BMB_00}") (class "Default")
      (node (ref "C02") (pin "B1") (pinfunction "O1_B1") (pintype "output"))
      (node (ref "C06") (pin "A1") (pinfunction "IN_A1") (pintype "input"))
    )
    (net (code "493") (name "~{BMB_01}") (class "Default")
      (node (ref "C02") (pin "E1") (pinfunction "O2_E1") (pintype "output"))
      (node (ref "C06") (pin "D1") (pinfunction "IN_D1") (pintype "input"))
    )
    (net (code "494") (name "~{BMB_02}") (class "Default")
      (node (ref "C02") (pin "H1") (pinfunction "O3_H1") (pintype "output"))
      (node (ref "C06") (pin "F1") (pinfunction "IN_F1") (pintype "input"))
    )
    (net (code "495") (name "~{BMB_03}") (class "Default")
      (node (ref "C02") (pin "K1") (pinfunction "O4_K1") (pintype "output"))
      (node (ref "C06") (pin "J1") (pinfunction "IN_J1") (pintype "input"))
    )
    (net (code "496") (name "~{BMB_04}") (class "Default")
      (node (ref "C02") (pin "M1") (pinfunction "O5_M1") (pintype "output"))
      (node (ref "C06") (pin "L1") (pinfunction "IN_L1") (pintype "input"))
    )
    (net (code "497") (name "~{BMB_05}") (class "Default")
      (node (ref "C02") (pin "P1") (pinfunction "O6_P1") (pintype "output"))
      (node (ref "C06") (pin "N1") (pinfunction "IN_N1") (pintype "input"))
    )
    (net (code "498") (name "~{BMB_06}") (class "Default")
      (node (ref "C02") (pin "S1") (pinfunction "O7_S1") (pintype "output"))
      (node (ref "C06") (pin "R1") (pinfunction "IN_R1") (pintype "input"))
    )
    (net (code "499") (name "~{BMB_07}") (class "Default")
      (node (ref "C02") (pin "U1") (pinfunction "O8_U1") (pintype "output"))
      (node (ref "C06") (pin "V1") (pinfunction "IN_V1") (pintype "input"))
    )
    (net (code "500") (name "~{BMB_08}") (class "Default")
      (node (ref "C02") (pin "F2") (pinfunction "O9_F2") (pintype "output"))
      (node (ref "C06") (pin "C1") (pinfunction "IN_C1") (pintype "input"))
    )
    (net (code "501") (name "~{BMB_09}") (class "Default")
      (node (ref "C02") (pin "J2") (pinfunction "O10_J2") (pintype "output"))
      (node (ref "C06") (pin "E2") (pinfunction "IN_E2") (pintype "input"))
    )
    (net (code "502") (name "~{BMB_10}") (class "Default")
      (node (ref "C02") (pin "L2") (pinfunction "O11_L2") (pintype "output"))
      (node (ref "C06") (pin "H2") (pinfunction "IN_H2") (pintype "input"))
    )
    (net (code "503") (name "~{BMB_11}") (class "Default")
      (node (ref "C02") (pin "N2") (pinfunction "O12_N2") (pintype "output"))
      (node (ref "C06") (pin "K2") (pinfunction "IN_K2") (pintype "input"))
    )
    (net (code "504") (name "~{BMR00}") (class "Default")
      (node (ref "A23") (pin "H1") (pinfunction "B_H1") (pintype "input"))
      (node (ref "B14") (pin "R2") (pinfunction "0_R2") (pintype "output"))
    )
    (net (code "505") (name "~{BMR01}") (class "Default")
      (node (ref "A23") (pin "A1") (pinfunction "A_A1") (pintype "input"))
      (node (ref "B14") (pin "E1") (pinfunction "1_E1") (pintype "output"))
    )
    (net (code "506") (name "~{C00}") (class "Default")
      (node (ref "A12") (pin "P2") (pinfunction "IN1_P2") (pintype "input"))
      (node (ref "B13") (pin "P1") (pinfunction "D_P1") (pintype "input"))
      (node (ref "B13") (pin "S2") (pinfunction "C_S2") (pintype "input"))
      (node (ref "B13") (pin "U1") (pinfunction "0_U1") (pintype "output"))
      (node (ref "B15") (pin "H1") (pinfunction "IN1_H1") (pintype "input"))
      (node (ref "C15") (pin "J2") (pinfunction "IN2_J2") (pintype "input"))
    )
    (net (code "507") (name "~{C01}") (class "Default")
      (node (ref "A12") (pin "R2") (pinfunction "IN2_R2") (pintype "input"))
      (node (ref "B10") (pin "P1") (pinfunction "IN3_P1") (pintype "input"))
      (node (ref "B13") (pin "M2") (pinfunction "D_M2") (pintype "input"))
      (node (ref "B13") (pin "R2") (pinfunction "0_R2") (pintype "output"))
      (node (ref "C12") (pin "F2") (pinfunction "IN3_F2") (pintype "input"))
      (node (ref "D10") (pin "D1") (pinfunction "IN4_D1") (pintype "input"))
    )
    (net (code "508") (name "~{CK00}") (class "Default")
      (node (ref "A18") (pin "N2") (pinfunction "N2_N2") (pintype "input"))
      (node (ref "B14") (pin "T2") (pinfunction "D_T2") (pintype "input"))
      (node (ref "B14") (pin "U1") (pinfunction "0_U1") (pintype "output"))
    )
    (net (code "509") (name "~{CK01}") (class "Default")
      (node (ref "B14") (pin "V1") (pinfunction "0_V1") (pintype "output"))
      (node (ref "C16") (pin "S2") (pinfunction "IN2_S2") (pintype "input"))
      (node (ref "C16") (pin "T2") (pinfunction "IN3_T2") (pintype "input"))
      (node (ref "C16") (pin "U2") (pinfunction "IN4_U2") (pintype "input"))
    )
    (net (code "510") (name "~{CLR_DF}") (class "Default")
      (node (ref "A11") (pin "U1") (pinfunction "OUT_U1") (pintype "output"))
      (node (ref "D11") (pin "N2") (pinfunction "S_N2") (pintype "input"))
    )
    (net (code "511") (name "~{CLR_DTF}") (class "Default")
      (node (ref "C13") (pin "U1") (pinfunction "OUT_U1") (pintype "output"))
      (node (ref "D11") (pin "U2") (pinfunction "S_U2") (pintype "input"))
    )
    (net (code "512") (name "~{CSTA}") (class "Default")
      (node (ref "A10") (pin "L2") (pinfunction "IN1_L2") (pintype "input"))
      (node (ref "IC2") (pin "8") (pinfunction "O_8") (pintype "output"))
      (node (ref "IC3") (pin "3") (pinfunction "I_3") (pintype "input"))
    )
    (net (code "513") (name "~{DATA}") (class "Default")
      (node (ref "B12") (pin "N1") (pinfunction "IN2_N1") (pintype "input"))
      (node (ref "C11") (pin "L2") (pinfunction "IN1_L2") (pintype "input"))
      (node (ref "C13") (pin "H1") (pinfunction "OUT_H1") (pintype "output"))
      (node (ref "C16") (pin "D2") (pinfunction "IN1_D2") (pintype "input"))
    )
    (net (code "514") (name "~{DB_00}") (class "Default")
      (node (ref "A06") (pin "B1") (pinfunction "P$2_B1") (pintype "bidirectional"))
      (node (ref "B02") (pin "D1") (pinfunction "D_D1") (pintype "open_collector"))
      (node (ref "D06") (pin "B1") (pinfunction "P$2_B1") (pintype "bidirectional"))
    )
    (net (code "515") (name "~{DB_01}") (class "Default")
      (node (ref "A06") (pin "D1") (pinfunction "P$2_D1") (pintype "bidirectional"))
      (node (ref "B02") (pin "E1") (pinfunction "E_E1") (pintype "open_collector"))
      (node (ref "D06") (pin "D1") (pinfunction "P$2_D1") (pintype "bidirectional"))
    )
    (net (code "516") (name "~{DB_02}") (class "Default")
      (node (ref "A06") (pin "E1") (pinfunction "P$2_E1") (pintype "bidirectional"))
      (node (ref "B02") (pin "K1") (pinfunction "D_K1") (pintype "open_collector"))
      (node (ref "D06") (pin "E1") (pinfunction "P$2_E1") (pintype "bidirectional"))
    )
    (net (code "517") (name "~{DB_03}") (class "Default")
      (node (ref "A06") (pin "H1") (pinfunction "P$2_H1") (pintype "bidirectional"))
      (node (ref "B02") (pin "L1") (pinfunction "E_L1") (pintype "open_collector"))
      (node (ref "D06") (pin "H1") (pinfunction "P$2_H1") (pintype "bidirectional"))
    )
    (net (code "518") (name "~{DB_04}") (class "Default")
      (node (ref "A06") (pin "J1") (pinfunction "P$2_J1") (pintype "bidirectional"))
      (node (ref "B02") (pin "R1") (pinfunction "D_R1") (pintype "open_collector"))
      (node (ref "D06") (pin "J1") (pinfunction "P$2_J1") (pintype "bidirectional"))
    )
    (net (code "519") (name "~{DB_05}") (class "Default")
      (node (ref "A06") (pin "L1") (pinfunction "P$2_L1") (pintype "bidirectional"))
      (node (ref "B02") (pin "S1") (pinfunction "E_S1") (pintype "open_collector"))
      (node (ref "D06") (pin "L1") (pinfunction "P$2_L1") (pintype "bidirectional"))
    )
    (net (code "520") (name "~{DB_06}") (class "Default")
      (node (ref "A06") (pin "M1") (pinfunction "P$2_M1") (pintype "bidirectional"))
      (node (ref "B02") (pin "H2") (pinfunction "D_H2") (pintype "open_collector"))
      (node (ref "D06") (pin "M1") (pinfunction "P$2_M1") (pintype "bidirectional"))
    )
    (net (code "521") (name "~{DB_07}") (class "Default")
      (node (ref "A06") (pin "P1") (pinfunction "P$2_P1") (pintype "bidirectional"))
      (node (ref "B02") (pin "J2") (pinfunction "E_J2") (pintype "open_collector"))
      (node (ref "D06") (pin "P1") (pinfunction "P$2_P1") (pintype "bidirectional"))
    )
    (net (code "522") (name "~{DB_08}") (class "Default")
      (node (ref "A06") (pin "S1") (pinfunction "P$2_S1") (pintype "bidirectional"))
      (node (ref "B02") (pin "N2") (pinfunction "D_N2") (pintype "open_collector"))
      (node (ref "D06") (pin "S1") (pinfunction "P$2_S1") (pintype "bidirectional"))
    )
    (net (code "523") (name "~{DB_09}") (class "Default")
      (node (ref "A06") (pin "D2") (pinfunction "P$2_D2") (pintype "bidirectional"))
      (node (ref "B02") (pin "P2") (pinfunction "E_P2") (pintype "open_collector"))
      (node (ref "D06") (pin "D2") (pinfunction "P$2_D2") (pintype "bidirectional"))
    )
    (net (code "524") (name "~{DB_10}") (class "Default")
      (node (ref "A06") (pin "E2") (pinfunction "P$2_E2") (pintype "bidirectional"))
      (node (ref "B02") (pin "U2") (pinfunction "D_U2") (pintype "open_collector"))
      (node (ref "D06") (pin "E2") (pinfunction "P$2_E2") (pintype "bidirectional"))
    )
    (net (code "525") (name "~{DB_11}") (class "Default")
      (node (ref "A06") (pin "H2") (pinfunction "P$2_H2") (pintype "bidirectional"))
      (node (ref "B02") (pin "V2") (pinfunction "E_V2") (pintype "open_collector"))
      (node (ref "D06") (pin "H2") (pinfunction "P$2_H2") (pintype "bidirectional"))
    )
    (net (code "526") (name "~{DF}") (class "Default")
      (node (ref "B05") (pin "A1") (pinfunction "A_A1") (pintype "input"))
      (node (ref "B12") (pin "J1") (pinfunction "IN3_J1") (pintype "input"))
      (node (ref "D11") (pin "P2") (pinfunction "1_P2") (pintype "output"))
    )
    (net (code "527") (name "~{DTB_00}") (class "Default")
      (node (ref "B02") (pin "A1") (pinfunction "A_A1") (pintype "input"))
      (node (ref "C09") (pin "F1") (pinfunction "0_F1") (pintype "output"))
    )
    (net (code "528") (name "~{DTB_01}") (class "Default")
      (node (ref "B02") (pin "B1") (pinfunction "B_B1") (pintype "input"))
      (node (ref "C09") (pin "J2") (pinfunction "0_J2") (pintype "output"))
    )
    (net (code "529") (name "~{DTB_02}") (class "Default")
      (node (ref "B02") (pin "F1") (pinfunction "A_F1") (pintype "input"))
      (node (ref "C09") (pin "M1") (pinfunction "0_M1") (pintype "output"))
    )
    (net (code "530") (name "~{DTB_03}") (class "Default")
      (node (ref "B02") (pin "H1") (pinfunction "B_H1") (pintype "input"))
      (node (ref "C09") (pin "R2") (pinfunction "0_R2") (pintype "output"))
    )
    (net (code "531") (name "~{DTB_04}") (class "Default")
      (node (ref "B02") (pin "M1") (pinfunction "A_M1") (pintype "input"))
      (node (ref "C09") (pin "U1") (pinfunction "0_U1") (pintype "output"))
    )
    (net (code "532") (name "~{DTB_05}") (class "Default")
      (node (ref "B02") (pin "N1") (pinfunction "B_N1") (pintype "input"))
      (node (ref "C09") (pin "V1") (pinfunction "0_V1") (pintype "output"))
    )
    (net (code "533") (name "~{DTB_06}") (class "Default")
      (node (ref "B02") (pin "D2") (pinfunction "A_D2") (pintype "input"))
      (node (ref "B09") (pin "F1") (pinfunction "0_F1") (pintype "output"))
    )
    (net (code "534") (name "~{DTB_07}") (class "Default")
      (node (ref "B02") (pin "E2") (pinfunction "B_E2") (pintype "input"))
      (node (ref "B09") (pin "V1") (pinfunction "0_V1") (pintype "output"))
    )
    (net (code "535") (name "~{DTB_08}") (class "Default")
      (node (ref "B02") (pin "K2") (pinfunction "A_K2") (pintype "input"))
      (node (ref "B09") (pin "M1") (pinfunction "0_M1") (pintype "output"))
    )
    (net (code "536") (name "~{DTB_09}") (class "Default")
      (node (ref "B02") (pin "L2") (pinfunction "B_L2") (pintype "input"))
      (node (ref "B09") (pin "R2") (pinfunction "0_R2") (pintype "output"))
    )
    (net (code "537") (name "~{DTB_10}") (class "Default")
      (node (ref "B02") (pin "R2") (pinfunction "A_R2") (pintype "input"))
      (node (ref "B09") (pin "U1") (pinfunction "0_U1") (pintype "output"))
    )
    (net (code "538") (name "~{DTB_11}") (class "Default")
      (node (ref "B02") (pin "S2") (pinfunction "B_S2") (pintype "input"))
      (node (ref "B09") (pin "J2") (pinfunction "0_J2") (pintype "output"))
    )
    (net (code "539") (name "~{DTF}") (class "Default")
      (node (ref "B04") (pin "L2") (pinfunction "B_L2") (pintype "input"))
      (node (ref "B12") (pin "C1") (pinfunction "IN3_C1") (pintype "input"))
      (node (ref "D11") (pin "V2") (pinfunction "1_V2") (pintype "output"))
    )
    (net (code "540") (name "~{DTSF}") (class "Default")
      (node (ref "IC8") (pin "11") (pinfunction "O_11") (pintype "output"))
      (node (ref "IC9") (pin "5") (pinfunction "I_5") (pintype "input"))
    )
    (net (code "541") (name "~{EA_00}") (class "Default")
      (node (ref "A06") (pin "V2") (pinfunction "P$2_V2") (pintype "bidirectional"))
      (node (ref "B05") (pin "R1") (pinfunction "D_R1") (pintype "open_collector"))
      (node (ref "D06") (pin "V2") (pinfunction "P$2_V2") (pintype "bidirectional"))
    )
    (net (code "542") (name "~{EA_01}") (class "Default")
      (node (ref "A06") (pin "T2") (pinfunction "P$2_T2") (pintype "bidirectional"))
      (node (ref "B05") (pin "S1") (pinfunction "E_S1") (pintype "open_collector"))
      (node (ref "D06") (pin "T2") (pinfunction "P$2_T2") (pintype "bidirectional"))
    )
    (net (code "543") (name "~{EA_02}") (class "Default")
      (node (ref "A06") (pin "S2") (pinfunction "P$2_S2") (pintype "bidirectional"))
      (node (ref "B05") (pin "H2") (pinfunction "D_H2") (pintype "open_collector"))
      (node (ref "D06") (pin "S2") (pinfunction "P$2_S2") (pintype "bidirectional"))
    )
    (net (code "544") (name "~{EF}") (class "Default")
      (node (ref "A11") (pin "K1") (pinfunction "OUT_K1") (pintype "output"))
      (node (ref "B04") (pin "A1") (pinfunction "A_A1") (pintype "input"))
    )
    (net (code "545") (name "~{END}") (class "Default")
      (node (ref "A08") (pin "F1") (pinfunction "0_F1") (pintype "output"))
      (node (ref "A09") (pin "M2") (pinfunction "IN3_M2") (pintype "input"))
      (node (ref "B04") (pin "F1") (pinfunction "A_F1") (pintype "input"))
    )
    (net (code "546") (name "~{ENI}") (class "Default")
      (node (ref "B03") (pin "L2") (pinfunction "B_L2") (pintype "input"))
      (node (ref "C07") (pin "M1") (pinfunction "M1_M1") (pintype "output"))
    )
    (net (code "547") (name "~{FR_00}") (class "Default")
      (node (ref "B03") (pin "N1") (pinfunction "B_N1") (pintype "input"))
      (node (ref "B07") (pin "U1") (pinfunction "U1_U1") (pintype "output"))
      (node (ref "C12") (pin "K1") (pinfunction "IN1_K1") (pintype "input"))
      (node (ref "C12") (pin "P1") (pinfunction "IN1_P1") (pintype "input"))
    )
    (net (code "548") (name "~{FR_01}") (class "Default")
      (node (ref "A12") (pin "H2") (pinfunction "IN1_H2") (pintype "input"))
      (node (ref "B03") (pin "D2") (pinfunction "A_D2") (pintype "input"))
      (node (ref "B05") (pin "E2") (pinfunction "B_E2") (pintype "input"))
      (node (ref "B07") (pin "V1") (pinfunction "V1_V1") (pintype "output"))
    )
    (net (code "549") (name "~{FR_02}") (class "Default")
      (node (ref "B03") (pin "E2") (pinfunction "B_E2") (pintype "input"))
      (node (ref "C07") (pin "F1") (pinfunction "F1_F1") (pintype "output"))
    )
    (net (code "550") (name "~{FR_03}") (class "Default")
      (node (ref "B03") (pin "K2") (pinfunction "A_K2") (pintype "input"))
      (node (ref "B08") (pin "J2") (pinfunction "IN2_J2") (pintype "input"))
      (node (ref "C07") (pin "J2") (pinfunction "J2_J2") (pintype "output"))
    )
    (net (code "551") (name "~{IM_00}") (class "Default")
      (node (ref "A04") (pin "B1") (pinfunction "P$2_B1") (pintype "bidirectional"))
      (node (ref "B03") (pin "D1") (pinfunction "D_D1") (pintype "open_collector"))
      (node (ref "B04") (pin "D1") (pinfunction "D_D1") (pintype "open_collector"))
      (node (ref "D04") (pin "B1") (pinfunction "P$2_B1") (pintype "bidirectional"))
    )
    (net (code "552") (name "~{IM_01}") (class "Default")
      (node (ref "A04") (pin "D1") (pinfunction "P$2_D1") (pintype "bidirectional"))
      (node (ref "B03") (pin "E1") (pinfunction "E_E1") (pintype "open_collector"))
      (node (ref "B04") (pin "E1") (pinfunction "E_E1") (pintype "open_collector"))
      (node (ref "D04") (pin "D1") (pinfunction "P$2_D1") (pintype "bidirectional"))
    )
    (net (code "553") (name "~{IM_02}") (class "Default")
      (node (ref "A04") (pin "E1") (pinfunction "P$2_E1") (pintype "bidirectional"))
      (node (ref "B03") (pin "K1") (pinfunction "D_K1") (pintype "open_collector"))
      (node (ref "B04") (pin "K1") (pinfunction "D_K1") (pintype "open_collector"))
      (node (ref "D04") (pin "E1") (pinfunction "P$2_E1") (pintype "bidirectional"))
    )
    (net (code "554") (name "~{IM_03}") (class "Default")
      (node (ref "A04") (pin "H1") (pinfunction "P$2_H1") (pintype "bidirectional"))
      (node (ref "B03") (pin "L1") (pinfunction "E_L1") (pintype "open_collector"))
      (node (ref "B04") (pin "L1") (pinfunction "E_L1") (pintype "open_collector"))
      (node (ref "D04") (pin "H1") (pinfunction "P$2_H1") (pintype "bidirectional"))
    )
    (net (code "555") (name "~{IM_04}") (class "Default")
      (node (ref "A04") (pin "J1") (pinfunction "P$2_J1") (pintype "bidirectional"))
      (node (ref "B03") (pin "R1") (pinfunction "D_R1") (pintype "open_collector"))
      (node (ref "B04") (pin "R1") (pinfunction "D_R1") (pintype "open_collector"))
      (node (ref "D04") (pin "J1") (pinfunction "P$2_J1") (pintype "bidirectional"))
    )
    (net (code "556") (name "~{IM_05}") (class "Default")
      (node (ref "A04") (pin "L1") (pinfunction "P$2_L1") (pintype "bidirectional"))
      (node (ref "B03") (pin "S1") (pinfunction "E_S1") (pintype "open_collector"))
      (node (ref "B04") (pin "S1") (pinfunction "E_S1") (pintype "open_collector"))
      (node (ref "D04") (pin "L1") (pinfunction "P$2_L1") (pintype "bidirectional"))
    )
    (net (code "557") (name "~{IM_06}") (class "Default")
      (node (ref "A04") (pin "M1") (pinfunction "P$2_M1") (pintype "bidirectional"))
      (node (ref "B03") (pin "H2") (pinfunction "D_H2") (pintype "open_collector"))
      (node (ref "B04") (pin "H2") (pinfunction "D_H2") (pintype "open_collector"))
      (node (ref "D04") (pin "M1") (pinfunction "P$2_M1") (pintype "bidirectional"))
    )
    (net (code "558") (name "~{IM_07}") (class "Default")
      (node (ref "A04") (pin "P1") (pinfunction "P$2_P1") (pintype "bidirectional"))
      (node (ref "B03") (pin "J2") (pinfunction "E_J2") (pintype "open_collector"))
      (node (ref "B04") (pin "J2") (pinfunction "E_J2") (pintype "open_collector"))
      (node (ref "D04") (pin "P1") (pinfunction "P$2_P1") (pintype "bidirectional"))
    )
    (net (code "559") (name "~{IM_08}") (class "Default")
      (node (ref "A04") (pin "S1") (pinfunction "P$2_S1") (pintype "bidirectional"))
      (node (ref "B03") (pin "N2") (pinfunction "D_N2") (pintype "open_collector"))
      (node (ref "B04") (pin "N2") (pinfunction "D_N2") (pintype "open_collector"))
      (node (ref "D04") (pin "S1") (pinfunction "P$2_S1") (pintype "bidirectional"))
    )
    (net (code "560") (name "~{IM_09}") (class "Default")
      (node (ref "A04") (pin "D2") (pinfunction "P$2_D2") (pintype "bidirectional"))
      (node (ref "B03") (pin "P2") (pinfunction "E_P2") (pintype "open_collector"))
      (node (ref "D04") (pin "D2") (pinfunction "P$2_D2") (pintype "bidirectional"))
    )
    (net (code "561") (name "~{IM_10}") (class "Default")
      (node (ref "A04") (pin "E2") (pinfunction "P$2_E2") (pintype "bidirectional"))
      (node (ref "D04") (pin "E2") (pinfunction "P$2_E2") (pintype "bidirectional"))
    )
    (net (code "562") (name "~{IM_11}") (class "Default")
      (node (ref "A04") (pin "H2") (pinfunction "P$2_H2") (pintype "bidirectional"))
      (node (ref "B04") (pin "P2") (pinfunction "E_P2") (pintype "open_collector"))
      (node (ref "D04") (pin "H2") (pinfunction "P$2_H2") (pintype "bidirectional"))
    )
    (net (code "563") (name "~{INT_RQ}") (class "Default")
      (node (ref "A12") (pin "K1") (pinfunction "OUT_K1") (pintype "output"))
      (node (ref "B05") (pin "B1") (pinfunction "B_B1") (pintype "input"))
    )
    (net (code "564") (name "~{LDMF}") (class "Default")
      (node (ref "B08") (pin "P2") (pinfunction "IN1_P2") (pintype "input"))
      (node (ref "IC8") (pin "6") (pinfunction "O_6") (pintype "output"))
      (node (ref "IC9") (pin "1") (pinfunction "I_1") (pintype "input"))
    )
    (net (code "565") (name "~{LPB_00}") (class "Default")
      (node (ref "D08") (pin "F1") (pinfunction "F1_F1") (pintype "output"))
      (node (ref "D10") (pin "M1") (pinfunction "IN1_M1") (pintype "input"))
    )
    (net (code "566") (name "~{LPB_01}") (class "Default")
      (node (ref "D08") (pin "M1") (pinfunction "M1_M1") (pintype "output"))
      (node (ref "D10") (pin "N1") (pinfunction "IN2_N1") (pintype "input"))
    )
    (net (code "567") (name "~{LPB_02}") (class "Default")
      (node (ref "D08") (pin "U1") (pinfunction "U1_U1") (pintype "output"))
      (node (ref "D10") (pin "P1") (pinfunction "IN3_P1") (pintype "input"))
    )
    (net (code "568") (name "~{LPB_03}") (class "Default")
      (node (ref "D08") (pin "J2") (pinfunction "J2_J2") (pintype "output"))
      (node (ref "D10") (pin "R1") (pinfunction "IN4_R1") (pintype "input"))
    )
    (net (code "569") (name "~{LPB_04}") (class "Default")
      (node (ref "D08") (pin "R2") (pinfunction "R2_R2") (pintype "output"))
      (node (ref "D10") (pin "R2") (pinfunction "IN5_R2") (pintype "input"))
    )
    (net (code "570") (name "~{LPB_05}") (class "Default")
      (node (ref "D08") (pin "V1") (pinfunction "V1_V1") (pintype "output"))
      (node (ref "D10") (pin "S2") (pinfunction "IN6_S2") (pintype "input"))
      (node (ref "D10") (pin "T2") (pinfunction "IN7_T2") (pintype "input"))
      (node (ref "D10") (pin "U2") (pinfunction "IN8_U2") (pintype "input"))
    )
    (net (code "571") (name "~{M-STOP}") (class "Default")
      (node (ref "A11") (pin "S1") (pinfunction "OUT_S1") (pintype "output"))
      (node (ref "B14") (pin "D1") (pinfunction "S_D1") (pintype "input"))
      (node (ref "C07") (pin "K2") (pinfunction "K2_K2") (pintype "input"))
      (node (ref "D14") (pin "L1") (pinfunction "M1_L1") (pintype "input"))
    )
    (net (code "572") (name "~{MB_TO_DTB}") (class "Default")
      (node (ref "D12") (pin "F1") (pinfunction "IN1_F1") (pintype "input"))
      (node (ref "D12") (pin "H1") (pinfunction "IN2_H1") (pintype "input"))
      (node (ref "D12") (pin "J1") (pinfunction "IN3_J1") (pintype "input"))
      (node (ref "D12") (pin "K1") (pinfunction "IN4_K1") (pintype "input"))
      (node (ref "D12") (pin "S1") (pinfunction "OUT_S1") (pintype "output"))
    )
    (net (code "573") (name "~{MC00}") (class "Default")
      (node (ref "A10") (pin "R1") (pinfunction "IN2_R1") (pintype "input"))
      (node (ref "B11") (pin "T2") (pinfunction "IN1_T2") (pintype "input"))
      (node (ref "B13") (pin "F1") (pinfunction "0_F1") (pintype "output"))
    )
    (net (code "574") (name "~{MC01}") (class "Default")
      (node (ref "B11") (pin "P1") (pinfunction "IN1_P1") (pintype "input"))
      (node (ref "B13") (pin "J2") (pinfunction "0_J2") (pintype "output"))
      (node (ref "C11") (pin "B1") (pinfunction "IN2_B1") (pintype "input"))
      (node (ref "D10") (pin "E2") (pinfunction "IN6_E2") (pintype "input"))
    )
    (net (code "575") (name "~{MC02}") (class "Default")
      (node (ref "B13") (pin "C1") (pinfunction "D_C1") (pintype "input"))
      (node (ref "B13") (pin "M1") (pinfunction "0_M1") (pintype "output"))
      (node (ref "D10") (pin "F2") (pinfunction "IN7_F2") (pintype "input"))
    )
    (net (code "576") (name "~{MF00}") (class "Default")
      (node (ref "B04") (pin "D2") (pinfunction "A_D2") (pintype "input"))
      (node (ref "B05") (pin "M1") (pinfunction "A_M1") (pintype "input"))
      (node (ref "IC4") (pin "6") (pinfunction "~{Q}_6") (pintype "output"))
    )
    (net (code "577") (name "~{MF01}") (class "Default")
      (node (ref "B04") (pin "E2") (pinfunction "B_E2") (pintype "input"))
      (node (ref "B05") (pin "N1") (pinfunction "B_N1") (pintype "input"))
      (node (ref "IC4") (pin "8") (pinfunction "~{Q}_8") (pintype "output"))
    )
    (net (code "578") (name "~{MF02}") (class "Default")
      (node (ref "B04") (pin "K2") (pinfunction "A_K2") (pintype "input"))
      (node (ref "B05") (pin "D2") (pinfunction "A_D2") (pintype "input"))
      (node (ref "IC5") (pin "6") (pinfunction "~{Q}_6") (pintype "output"))
    )
    (net (code "579") (name "~{MKTK}") (class "Default")
      (node (ref "A08") (pin "P2") (pinfunction "1_P2") (pintype "output"))
      (node (ref "A09") (pin "K2") (pinfunction "IN1_K2") (pintype "input"))
      (node (ref "B04") (pin "B1") (pinfunction "B_B1") (pintype "input"))
    )
    (net (code "580") (name "~{MKT}") (class "Default")
      (node (ref "B10") (pin "R1") (pinfunction "IN4_R1") (pintype "input"))
      (node (ref "B13") (pin "T2") (pinfunction "D_T2") (pintype "input"))
      (node (ref "B13") (pin "V1") (pinfunction "0_V1") (pintype "output"))
      (node (ref "C14") (pin "N1") (pinfunction "C_N1") (pintype "input"))
      (node (ref "D10") (pin "H2") (pinfunction "IN8_H2") (pintype "input"))
    )
    (net (code "581") (name "~{MK_BLK_END}") (class "Default")
      (node (ref "A09") (pin "C1") (pinfunction "IN3_C1") (pintype "input"))
      (node (ref "CD18") (pin "BV1") (pinfunction "BV1_BV1") (pintype "output"))
    )
    (net (code "582") (name "~{MK_BLK_MK}") (class "Default")
      (node (ref "CD18") (pin "AD2") (pinfunction "AD2_AD2") (pintype "output"))
    )
    (net (code "583") (name "~{MK_BLK_START}") (class "Default")
      (node (ref "A09") (pin "A1") (pinfunction "IN1_A1") (pintype "input"))
      (node (ref "CD18") (pin "AF1") (pinfunction "AF1_AF1") (pintype "output"))
    )
    (net (code "584") (name "~{MK_BLK_SYNC}") (class "Default")
      (node (ref "CD18") (pin "BT2") (pinfunction "BT2_BT2") (pintype "output"))
    )
    (net (code "585") (name "~{MK_DATA_SYNC}") (class "Default")
      (node (ref "CD18") (pin "AJ1") (pinfunction "AJ1_AJ1") (pintype "output"))
    )
    (net (code "586") (name "~{MK_DATA}") (class "Default")
      (node (ref "A09") (pin "B1") (pinfunction "IN2_B1") (pintype "input"))
      (node (ref "CD18") (pin "AU2") (pinfunction "AU2_AU2") (pintype "output"))
    )
    (net (code "587") (name "~{MK_END}") (class "Default")
      (node (ref "A09") (pin "D1") (pinfunction "IN4_D1") (pintype "input"))
      (node (ref "CD18") (pin "AH2") (pinfunction "AH2_AH2") (pintype "output"))
    )
    (net (code "588") (name "~{MOVE}") (class "Default")
      (node (ref "A09") (pin "F2") (pinfunction "IN3_F2") (pintype "input"))
      (node (ref "D07") (pin "D1") (pinfunction "~{O0}_D1") (pintype "output"))
    )
    (net (code "589") (name "~{MR00}") (class "Default")
      (node (ref "B03") (pin "H1") (pinfunction "B_H1") (pintype "input"))
      (node (ref "B07") (pin "R2") (pinfunction "R2_R2") (pintype "output"))
    )
    (net (code "590") (name "~{MR01}") (class "Default")
      (node (ref "B03") (pin "M1") (pinfunction "A_M1") (pintype "input"))
      (node (ref "B14") (pin "C1") (pinfunction "D_C1") (pintype "input"))
      (node (ref "C07") (pin "R2") (pinfunction "R2_R2") (pintype "output"))
    )
    (net (code "591") (name "~{PAR}") (class "Default")
      (node (ref "A08") (pin "S1") (pinfunction "1_S1") (pintype "output"))
      (node (ref "A12") (pin "E1") (pinfunction "IN2_E1") (pintype "input"))
      (node (ref "B04") (pin "M1") (pinfunction "A_M1") (pintype "input"))
    )
    (net (code "592") (name "~{PC+ES}") (class "Default")
      (node (ref "A11") (pin "J2") (pinfunction "OUT_J2") (pintype "output"))
      (node (ref "B11") (pin "R2") (pinfunction "IN3_R2") (pintype "input"))
    )
    (net (code "593") (name "~{PWR_CLR}") (class "Default")
      (node (ref "A10") (pin "H2") (pinfunction "IN1_H2") (pintype "input"))
      (node (ref "A10") (pin "M2") (pinfunction "IN2_M2") (pintype "input"))
      (node (ref "A12") (pin "A1") (pinfunction "IN1_A1") (pintype "input"))
      (node (ref "A23") (pin "M1") (pinfunction "A_M1") (pintype "input"))
      (node (ref "B08") (pin "U2") (pinfunction "IN2_U2") (pintype "input"))
      (node (ref "C05") (pin "K1") (pinfunction "OUT_K1") (pintype "output"))
      (node (ref "C06") (pin "P2") (pinfunction "IN_P2") (pintype "input"))
      (node (ref "C11") (pin "U2") (pinfunction "IN2_U2") (pintype "input"))
      (node (ref "C14") (pin "R1") (pinfunction "S_R1") (pintype "input"))
      (node (ref "IC4") (pin "1") (pinfunction "CLR_1") (pintype "input"))
      (node (ref "IC4") (pin "13") (pinfunction "CLR_13") (pintype "input"))
      (node (ref "IC5") (pin "1") (pinfunction "CLR_1") (pintype "input"))
    )
    (net (code "594") (name "~{RDD_00}") (class "Default")
      (node (ref "A21") (pin "V2") (pinfunction "V2_V2") (pintype "output"))
    )
    (net (code "595") (name "~{RDD_01}") (class "Default")
      (node (ref "B20") (pin "V2") (pinfunction "V2_V2") (pintype "output"))
    )
    (net (code "596") (name "~{RDD_02}") (class "Default")
      (node (ref "A20") (pin "V2") (pinfunction "V2_V2") (pintype "output"))
    )
    (net (code "597") (name "~{RDMK}") (class "Default")
      (node (ref "B18") (pin "V2") (pinfunction "V2_V2") (pintype "output"))
    )
    (net (code "598") (name "~{READ_ALL}") (class "Default")
      (node (ref "C11") (pin "M1") (pinfunction "IN2_M1") (pintype "input"))
      (node (ref "D07") (pin "N1") (pinfunction "~{O3}_N1") (pintype "output"))
    )
    (net (code "599") (name "~{READ_DATA}") (class "Default")
      (node (ref "B08") (pin "L2") (pinfunction "IN1_L2") (pintype "input"))
      (node (ref "B11") (pin "J2") (pinfunction "IN1_J2") (pintype "input"))
      (node (ref "D07") (pin "J1") (pinfunction "~{O2}_J1") (pintype "output"))
    )
    (net (code "600") (name "~{RSTA}") (class "Default")
      (node (ref "B03") (pin "C1") (pinfunction "C_C1") (pintype "input"))
      (node (ref "B03") (pin "F2") (pinfunction "C_F2") (pintype "input"))
      (node (ref "B03") (pin "J1") (pinfunction "C_J1") (pintype "input"))
      (node (ref "B03") (pin "M2") (pinfunction "C_M2") (pintype "input"))
      (node (ref "B03") (pin "P1") (pinfunction "C_P1") (pintype "input"))
      (node (ref "IC2") (pin "11") (pinfunction "O_11") (pintype "output"))
      (node (ref "IC3") (pin "5") (pinfunction "I_5") (pintype "input"))
    )
    (net (code "601") (name "~{RSTB}") (class "Default")
      (node (ref "B04") (pin "C1") (pinfunction "C_C1") (pintype "input"))
      (node (ref "B04") (pin "F2") (pinfunction "C_F2") (pintype "input"))
      (node (ref "B04") (pin "J1") (pinfunction "C_J1") (pintype "input"))
      (node (ref "B04") (pin "M2") (pinfunction "C_M2") (pintype "input"))
      (node (ref "B04") (pin "P1") (pinfunction "C_P1") (pintype "input"))
      (node (ref "IC8") (pin "8") (pinfunction "O_8") (pintype "output"))
      (node (ref "IC9") (pin "3") (pinfunction "I_3") (pintype "input"))
    )
    (net (code "602") (name "~{SEARCH}") (class "Default")
      (node (ref "B05") (pin "K2") (pinfunction "A_K2") (pintype "input"))
      (node (ref "B11") (pin "K2") (pinfunction "IN2_K2") (pintype "input"))
      (node (ref "D07") (pin "E1") (pinfunction "~{O1}_E1") (pintype "output"))
    )
    (net (code "603") (name "~{SEL}") (class "Default")
      (node (ref "A08") (pin "J2") (pinfunction "0_J2") (pintype "output"))
      (node (ref "A09") (pin "N2") (pinfunction "IN4_N2") (pintype "input"))
      (node (ref "B04") (pin "H1") (pinfunction "B_H1") (pintype "input"))
    )
    (net (code "604") (name "~{SE}") (class "Default")
      (node (ref "A09") (pin "H1") (pinfunction "IN2_H1") (pintype "input"))
      (node (ref "D07") (pin "L1") (pinfunction "~{O7}_L1") (pintype "output"))
    )
    (net (code "605") (name "~{SH_EN}") (class "Default")
      (node (ref "A11") (pin "M2") (pinfunction "IN_M2") (pintype "input"))
      (node (ref "A12") (pin "V2") (pinfunction "OUT_V2") (pintype "output"))
      (node (ref "C10") (pin "C1") (pinfunction "IN2A_C1") (pintype "input"))
      (node (ref "C10") (pin "J1") (pinfunction "IN2A_J1") (pintype "input"))
      (node (ref "C10") (pin "P1") (pinfunction "IN2A_P1") (pintype "input"))
    )
    (net (code "606") (name "~{SKP_RQ}") (class "Default")
      (node (ref "A12") (pin "S1") (pinfunction "OUT_S1") (pintype "output"))
      (node (ref "B05") (pin "F1") (pinfunction "A_F1") (pintype "input"))
    )
    (net (code "607") (name "~{SP_DY}") (class "Default")
      (node (ref "C14") (pin "M2") (pinfunction "D_M2") (pintype "input"))
      (node (ref "D14") (pin "F2") (pinfunction "F2_F2") (pintype "output"))
    )
    (net (code "608") (name "~{ST_BLK_MK}") (class "Default")
      (node (ref "A09") (pin "D2") (pinfunction "IN1_D2") (pintype "input"))
      (node (ref "A09") (pin "M1") (pinfunction "IN1_M1") (pintype "input"))
      (node (ref "C13") (pin "F2") (pinfunction "OUT_F2") (pintype "output"))
    )
    (net (code "609") (name "~{ST_CK_0P}") (class "Default")
      (node (ref "C13") (pin "A1") (pinfunction "IN_A1") (pintype "input"))
      (node (ref "D17") (pin "L2") (pinfunction "F2_L2") (pintype "output"))
    )
    (net (code "610") (name "~{ST_CK}") (class "Default")
      (node (ref "C13") (pin "K1") (pinfunction "OUT_K1") (pintype "output"))
      (node (ref "C16") (pin "E2") (pinfunction "IN2_E2") (pintype "input"))
    )
    (net (code "611") (name "~{ST_DATA}") (class "Default")
      (node (ref "C13") (pin "J2") (pinfunction "OUT_J2") (pintype "output"))
    )
    (net (code "612") (name "~{ST_FINAL}") (class "Default")
      (node (ref "C11") (pin "M2") (pinfunction "IN2_M2") (pintype "input"))
      (node (ref "C13") (pin "M1") (pinfunction "OUT_M1") (pintype "output"))
      (node (ref "C16") (pin "F2") (pinfunction "IN3_F2") (pintype "input"))
    )
    (net (code "613") (name "~{ST_IDLE}") (class "Default")
      (node (ref "A09") (pin "E2") (pinfunction "IN2_E2") (pintype "input"))
      (node (ref "A09") (pin "N1") (pinfunction "IN2_N1") (pintype "input"))
      (node (ref "C13") (pin "L2") (pinfunction "OUT_L2") (pintype "output"))
    )
    (net (code "614") (name "~{ST_REV_CK}") (class "Default")
      (node (ref "C13") (pin "E1") (pinfunction "OUT_E1") (pintype "output"))
    )
    (net (code "615") (name "~{SWTM}") (class "Default")
      (node (ref "B06") (pin "R2") (pinfunction "OUT_R2") (pintype "output"))
      (node (ref "C10") (pin "L2") (pinfunction "IN1B_L2") (pintype "input"))
    )
    (net (code "616") (name "~{SYNC-P}") (class "Default")
      (node (ref "B10") (pin "J2") (pinfunction "OUT_J2") (pintype "output"))
      (node (ref "B13") (pin "A1") (pinfunction "R_A1") (pintype "input"))
      (node (ref "B13") (pin "K2") (pinfunction "R_K2") (pintype "input"))
    )
    (net (code "617") (name "~{SYNC}") (class "Default")
      (node (ref "CD18") (pin "BM2") (pinfunction "BM2_BM2") (pintype "output"))
    )
    (net (code "618") (name "~{TIM}") (class "Default")
      (node (ref "A08") (pin "M1") (pinfunction "0_M1") (pintype "output"))
      (node (ref "A09") (pin "L2") (pinfunction "IN2_L2") (pintype "input"))
      (node (ref "B04") (pin "N1") (pinfunction "B_N1") (pintype "input"))
    )
    (net (code "619") (name "~{TM_EN}") (class "Default")
      (node (ref "B15") (pin "D1") (pinfunction "IN1_D1") (pintype "input"))
      (node (ref "B15") (pin "D2") (pinfunction "IN1_D2") (pintype "input"))
      (node (ref "C12") (pin "C1") (pinfunction "IN3_C1") (pintype "input"))
      (node (ref "C12") (pin "K2") (pinfunction "IN2_K2") (pintype "input"))
      (node (ref "C13") (pin "P1") (pinfunction "OUT_P1") (pintype "output"))
      (node (ref "D15") (pin "J2") (pinfunction "J2_J2") (pintype "input"))
      (node (ref "D15") (pin "K2") (pinfunction "K2_K2") (pintype "input"))
    )
    (net (code "620") (name "~{TP00_A}") (class "Default")
      (node (ref "A15") (pin "M1") (pinfunction "IN1_M1") (pintype "input"))
      (node (ref "A15") (pin "N1") (pinfunction "IN2_N1") (pintype "input"))
      (node (ref "A15") (pin "P1") (pinfunction "IN3_P1") (pintype "input"))
      (node (ref "A15") (pin "R1") (pinfunction "IN4_R1") (pintype "input"))
      (node (ref "A16") (pin "L2") (pinfunction "F2_L2") (pintype "output"))
    )
    (net (code "621") (name "~{TP0_XTLK_DY}") (class "Default")
      (node (ref "A11") (pin "R2") (pinfunction "OUT_R2") (pintype "output"))
      (node (ref "A15") (pin "F2") (pinfunction "IN3_F2") (pintype "input"))
      (node (ref "A16") (pin "J2") (pinfunction "J2_J2") (pintype "input"))
      (node (ref "A16") (pin "K2") (pinfunction "K2_K2") (pintype "input"))
    )
    (net (code "622") (name "~{TP00}") (class "Default")
      (node (ref "A15") (pin "E1") (pinfunction "OUT_E1") (pintype "output"))
      (node (ref "A15") (pin "F1") (pinfunction "IN1_F1") (pintype "input"))
      (node (ref "A15") (pin "H1") (pinfunction "IN2_H1") (pintype "input"))
      (node (ref "A15") (pin "J1") (pinfunction "IN3_J1") (pintype "input"))
      (node (ref "A15") (pin "K1") (pinfunction "IN4_K1") (pintype "input"))
      (node (ref "B13") (pin "N1") (pinfunction "C_N1") (pintype "input"))
      (node (ref "CD18") (pin "AN1") (pinfunction "AN1_AN1") (pintype "input"))
    )
    (net (code "623") (name "~{TP01_A}") (class "Default")
      (node (ref "A15") (pin "R2") (pinfunction "IN1_R2") (pintype "input"))
      (node (ref "A15") (pin "S2") (pinfunction "IN2_S2") (pintype "input"))
      (node (ref "A15") (pin "T2") (pinfunction "IN3_T2") (pintype "input"))
      (node (ref "A15") (pin "U2") (pinfunction "IN4_U2") (pintype "input"))
      (node (ref "B16") (pin "L2") (pinfunction "F2_L2") (pintype "output"))
    )
    (net (code "624") (name "~{TP1_XTLK_DY}") (class "Default")
      (node (ref "A11") (pin "V2") (pinfunction "OUT_V2") (pintype "output"))
      (node (ref "A15") (pin "B1") (pinfunction "IN2_B1") (pintype "input"))
      (node (ref "B16") (pin "H2") (pinfunction "H2_H2") (pintype "input"))
      (node (ref "B16") (pin "J2") (pinfunction "J2_J2") (pintype "input"))
    )
    (net (code "625") (name "~{TP01}") (class "Default")
      (node (ref "A15") (pin "J2") (pinfunction "OUT_J2") (pintype "output"))
      (node (ref "A15") (pin "K2") (pinfunction "IN1_K2") (pintype "input"))
      (node (ref "A15") (pin "L2") (pinfunction "IN2_L2") (pintype "input"))
      (node (ref "A15") (pin "M2") (pinfunction "IN3_M2") (pintype "input"))
      (node (ref "A15") (pin "N2") (pinfunction "IN4_N2") (pintype "input"))
      (node (ref "B13") (pin "L2") (pinfunction "C_L2") (pintype "input"))
    )
    (net (code "626") (name "~{TS03}") (class "Default")
      (node (ref "D17") (pin "H2") (pinfunction "H2_H2") (pintype "input"))
      (node (ref "D17") (pin "J2") (pinfunction "J2_J2") (pintype "input"))
      (node (ref "D17") (pin "K2") (pinfunction "K2_K2") (pintype "input"))
      (node (ref "IC3") (pin "8") (pinfunction "O_8") (pintype "output"))
    )
    (net (code "627") (name "~{T_00}") (class "Default")
      (node (ref "A24") (pin "V2") (pinfunction "P$2_V2") (pintype "bidirectional"))
      (node (ref "B22") (pin "V2") (pinfunction "E_V2") (pintype "output"))
      (node (ref "B23") (pin "V2") (pinfunction "P$1_V2") (pintype "passive"))
    )
    (net (code "628") (name "~{T_01}") (class "Default")
      (node (ref "A23") (pin "S1") (pinfunction "E_S1") (pintype "output"))
      (node (ref "A24") (pin "M2") (pinfunction "P$2_M2") (pintype "bidirectional"))
      (node (ref "B23") (pin "M2") (pinfunction "P$1_M2") (pintype "passive"))
    )
    (net (code "629") (name "~{T_02}") (class "Default")
      (node (ref "A23") (pin "H2") (pinfunction "D_H2") (pintype "output"))
      (node (ref "A24") (pin "N2") (pinfunction "P$2_N2") (pintype "bidirectional"))
      (node (ref "B23") (pin "N2") (pinfunction "P$1_N2") (pintype "passive"))
    )
    (net (code "630") (name "~{T_03}") (class "Default")
      (node (ref "A23") (pin "J2") (pinfunction "E_J2") (pintype "output"))
      (node (ref "A24") (pin "P2") (pinfunction "P$2_P2") (pintype "bidirectional"))
      (node (ref "B23") (pin "P2") (pinfunction "P$1_P2") (pintype "passive"))
    )
    (net (code "631") (name "~{T_04}") (class "Default")
      (node (ref "A23") (pin "N2") (pinfunction "D_N2") (pintype "output"))
      (node (ref "A24") (pin "R2") (pinfunction "P$2_R2") (pintype "bidirectional"))
      (node (ref "B23") (pin "R2") (pinfunction "P$1_R2") (pintype "passive"))
    )
    (net (code "632") (name "~{T_05}") (class "Default")
      (node (ref "A23") (pin "P2") (pinfunction "E_P2") (pintype "output"))
      (node (ref "A24") (pin "S2") (pinfunction "P$2_S2") (pintype "bidirectional"))
      (node (ref "B23") (pin "S2") (pinfunction "P$1_S2") (pintype "passive"))
    )
    (net (code "633") (name "~{T_06}") (class "Default")
      (node (ref "A23") (pin "U2") (pinfunction "D_U2") (pintype "output"))
      (node (ref "A24") (pin "T2") (pinfunction "P$2_T2") (pintype "bidirectional"))
      (node (ref "B23") (pin "T2") (pinfunction "P$1_T2") (pintype "passive"))
    )
    (net (code "634") (name "~{T_07}") (class "Default")
      (node (ref "A23") (pin "V2") (pinfunction "E_V2") (pintype "output"))
      (node (ref "A24") (pin "U2") (pinfunction "P$2_U2") (pintype "bidirectional"))
      (node (ref "B23") (pin "U2") (pinfunction "P$1_U2") (pintype "passive"))
    )
    (net (code "635") (name "~{T_FWD}") (class "Default")
      (node (ref "A23") (pin "K1") (pinfunction "D_K1") (pintype "output"))
      (node (ref "A24") (pin "E2") (pinfunction "P$2_E2") (pintype "bidirectional"))
      (node (ref "B23") (pin "H2") (pinfunction "P$1_H2") (pintype "passive"))
    )
    (net (code "636") (name "~{T_GO}") (class "Default")
      (node (ref "A23") (pin "D1") (pinfunction "D_D1") (pintype "output"))
      (node (ref "A24") (pin "C2") (pinfunction "P$2_C2") (pintype "bidirectional"))
      (node (ref "B23") (pin "D2") (pinfunction "P$1_D2") (pintype "passive"))
    )
    (net (code "637") (name "~{T_PWR_CLR}") (class "Default")
      (node (ref "A23") (pin "R1") (pinfunction "D_R1") (pintype "output"))
      (node (ref "A24") (pin "H2") (pinfunction "P$2_H2") (pintype "bidirectional"))
      (node (ref "B23") (pin "K2") (pinfunction "P$1_K2") (pintype "passive"))
    )
    (net (code "638") (name "~{T_REV}") (class "Default")
      (node (ref "A23") (pin "L1") (pinfunction "E_L1") (pintype "output"))
      (node (ref "A24") (pin "F2") (pinfunction "P$2_F2") (pintype "bidirectional"))
      (node (ref "B23") (pin "J2") (pinfunction "P$1_J2") (pintype "passive"))
    )
    (net (code "639") (name "~{T_SINGLE_UNIT}") (class "Default")
      (node (ref "A24") (pin "K2") (pinfunction "P$2_K2") (pintype "bidirectional"))
      (node (ref "B21") (pin "T2") (pinfunction "IN_T2") (pintype "input"))
    )
    (net (code "640") (name "~{T_STOP}") (class "Default")
      (node (ref "A23") (pin "E1") (pinfunction "E_E1") (pintype "output"))
      (node (ref "A24") (pin "D2") (pinfunction "P$2_D2") (pintype "bidirectional"))
      (node (ref "B23") (pin "E2") (pinfunction "P$1_E2") (pintype "passive"))
    )
    (net (code "641") (name "~{T_TRK}") (class "Default")
      (node (ref "A18") (pin "V2") (pinfunction "V2_V2") (pintype "output"))
      (node (ref "B15") (pin "E1") (pinfunction "IN2_E1") (pintype "input"))
    )
    (net (code "642") (name "~{T_WRITE_OK}") (class "Default")
      (node (ref "A22") (pin "H2") (pinfunction "H2_H2") (pintype "input"))
      (node (ref "A24") (pin "L2") (pinfunction "P$2_L2") (pintype "bidirectional"))
      (node (ref "B23") (pin "L2") (pinfunction "P$1_L2") (pintype "passive"))
    )
    (net (code "643") (name "~{U+M_DY}") (class "Default")
      (node (ref "C12") (pin "A1") (pinfunction "IN1_A1") (pintype "input"))
      (node (ref "C12") (pin "R2") (pinfunction "IN3_R2") (pintype "input"))
      (node (ref "D14") (pin "E2") (pinfunction "F2_E2") (pintype "output"))
      (node (ref "D14") (pin "N1") (pinfunction "N1_N1") (pintype "input"))
    )
    (net (code "644") (name "~{USR_00}") (class "Default")
      (node (ref "B03") (pin "A1") (pinfunction "A_A1") (pintype "input"))
      (node (ref "B07") (pin "F1") (pinfunction "F1_F1") (pintype "output"))
    )
    (net (code "645") (name "~{USR_01}") (class "Default")
      (node (ref "B03") (pin "B1") (pinfunction "B_B1") (pintype "input"))
      (node (ref "B07") (pin "J2") (pinfunction "J2_J2") (pintype "output"))
    )
    (net (code "646") (name "~{USR_02}") (class "Default")
      (node (ref "B03") (pin "F1") (pinfunction "A_F1") (pintype "input"))
      (node (ref "B07") (pin "M1") (pinfunction "M1_M1") (pintype "output"))
    )
    (net (code "647") (name "~{UTS}") (class "Default")
      (node (ref "C12") (pin "L2") (pinfunction "IN3_L2") (pintype "input"))
      (node (ref "C14") (pin "P2") (pinfunction "1_P2") (pintype "output"))
      (node (ref "C15") (pin "P2") (pinfunction "IN1_P2") (pintype "input"))
      (node (ref "C16") (pin "A1") (pinfunction "IN1_A1") (pintype "input"))
      (node (ref "C16") (pin "B1") (pinfunction "IN2_B1") (pintype "input"))
      (node (ref "C16") (pin "C1") (pinfunction "IN3_C1") (pintype "input"))
      (node (ref "C16") (pin "D1") (pinfunction "IN4_D1") (pintype "input"))
      (node (ref "C16") (pin "F1") (pinfunction "IN1_F1") (pintype "input"))
      (node (ref "C16") (pin "H1") (pinfunction "IN2_H1") (pintype "input"))
      (node (ref "C16") (pin "J1") (pinfunction "IN3_J1") (pintype "input"))
      (node (ref "C16") (pin "K1") (pinfunction "IN4_K1") (pintype "input"))
    )
    (net (code "648") (name "~{W-INH}") (class "Default")
      (node (ref "A08") (pin "V2") (pinfunction "1_V2") (pintype "output"))
      (node (ref "B11") (pin "L1") (pinfunction "IN2_L1") (pintype "input"))
      (node (ref "B12") (pin "H1") (pinfunction "IN2_H1") (pintype "input"))
    )
    (net (code "649") (name "~{WB00}") (class "Default")
      (node (ref "A21") (pin "P2") (pinfunction "P2_P2") (pintype "input"))
      (node (ref "B18") (pin "P2") (pinfunction "P2_P2") (pintype "input"))
      (node (ref "C10") (pin "D1") (pinfunction "IN2B_D1") (pintype "input"))
      (node (ref "C14") (pin "E1") (pinfunction "1_E1") (pintype "output"))
    )
    (net (code "650") (name "~{WB01}") (class "Default")
      (node (ref "B20") (pin "P2") (pinfunction "P2_P2") (pintype "input"))
      (node (ref "C10") (pin "K1") (pinfunction "IN2B_K1") (pintype "input"))
      (node (ref "C14") (pin "H2") (pinfunction "1_H2") (pintype "output"))
    )
    (net (code "651") (name "~{WB02}") (class "Default")
      (node (ref "A20") (pin "P2") (pinfunction "P2_P2") (pintype "input"))
      (node (ref "C10") (pin "R1") (pinfunction "IN2B_R1") (pintype "input"))
      (node (ref "C14") (pin "L1") (pinfunction "1_L1") (pintype "output"))
    )
    (net (code "652") (name "~{WC0}") (class "Default")
      (node (ref "C06") (pin "N2") (pinfunction "OUT_N2") (pintype "output"))
      (node (ref "IC5") (pin "10") (pinfunction "PRE_10") (pintype "input"))
    )
    (net (code "653") (name "~{WC}") (class "Default")
      (node (ref "B12") (pin "F2") (pinfunction "IN3_F2") (pintype "input"))
      (node (ref "C12") (pin "T2") (pinfunction "IN1_T2") (pintype "input"))
      (node (ref "D11") (pin "M2") (pinfunction "D_M2") (pintype "input"))
      (node (ref "IC5") (pin "8") (pinfunction "~{Q}_8") (pintype "output"))
    )
    (net (code "654") (name "~{WRITE_ALL}") (class "Default")
      (node (ref "D07") (pin "M1") (pinfunction "~{O5}_M1") (pintype "output"))
    )
    (net (code "655") (name "~{WRITE_DATA}") (class "Default")
      (node (ref "B08") (pin "M2") (pinfunction "IN2_M2") (pintype "input"))
      (node (ref "D07") (pin "F1") (pinfunction "~{O4}_F1") (pintype "output"))
    )
    (net (code "656") (name "~{WRITE_OK}") (class "Default")
      (node (ref "A10") (pin "J1") (pinfunction "IN2_J1") (pintype "input"))
      (node (ref "C17") (pin "J2") (pinfunction "OUT_J2") (pintype "output"))
    )
    (net (code "657") (name "~{WRTM}") (class "Default")
      (node (ref "B08") (pin "H2") (pinfunction "IN1_H2") (pintype "input"))
      (node (ref "C10") (pin "M2") (pinfunction "IN2A_M2") (pintype "input"))
      (node (ref "D07") (pin "H1") (pinfunction "~{O6}_H1") (pintype "output"))
    )
    (net (code "658") (name "~{WR_EN}") (class "Default")
      (node (ref "B11") (pin "F1") (pinfunction "IN2_F1") (pintype "input"))
      (node (ref "C11") (pin "H2") (pinfunction "IN1_H2") (pintype "input"))
      (node (ref "C12") (pin "J2") (pinfunction "IN1_J2") (pintype "input"))
      (node (ref "C14") (pin "S1") (pinfunction "1_S1") (pintype "output"))
      (node (ref "C15") (pin "D2") (pinfunction "IN1_D2") (pintype "input"))
      (node (ref "C15") (pin "H2") (pinfunction "IN1_H2") (pintype "input"))
    )
    (net (code "659") (name "~{XSAD}") (class "Default")
      (node (ref "A11") (pin "K2") (pinfunction "IN_K2") (pintype "input"))
      (node (ref "D13") (pin "L2") (pinfunction "F2_L2") (pintype "output"))
    )
    (net (code "660") (name "~{XSTA}") (class "Default")
      (node (ref "B08") (pin "R2") (pinfunction "IN2_R2") (pintype "input"))
      (node (ref "D13") (pin "H2") (pinfunction "H2_H2") (pintype "input"))
      (node (ref "D13") (pin "J2") (pinfunction "J2_J2") (pintype "input"))
      (node (ref "D13") (pin "K2") (pinfunction "K2_K2") (pintype "input"))
      (node (ref "D14") (pin "K2") (pinfunction "U1_K2") (pintype "input"))
      (node (ref "D14") (pin "L2") (pinfunction "S1_L2") (pintype "input"))
      (node (ref "D16") (pin "M2") (pinfunction "H2_M2") (pintype "input"))
      (node (ref "D16") (pin "N2") (pinfunction "J2_N2") (pintype "input"))
      (node (ref "IC2") (pin "6") (pinfunction "O_6") (pintype "output"))
      (node (ref "IC3") (pin "1") (pinfunction "I_1") (pintype "input"))
    )
  )
)
